# AM625SIP_FatBoi.net
KiCad netlist of a schematic drawn in Altium Designer
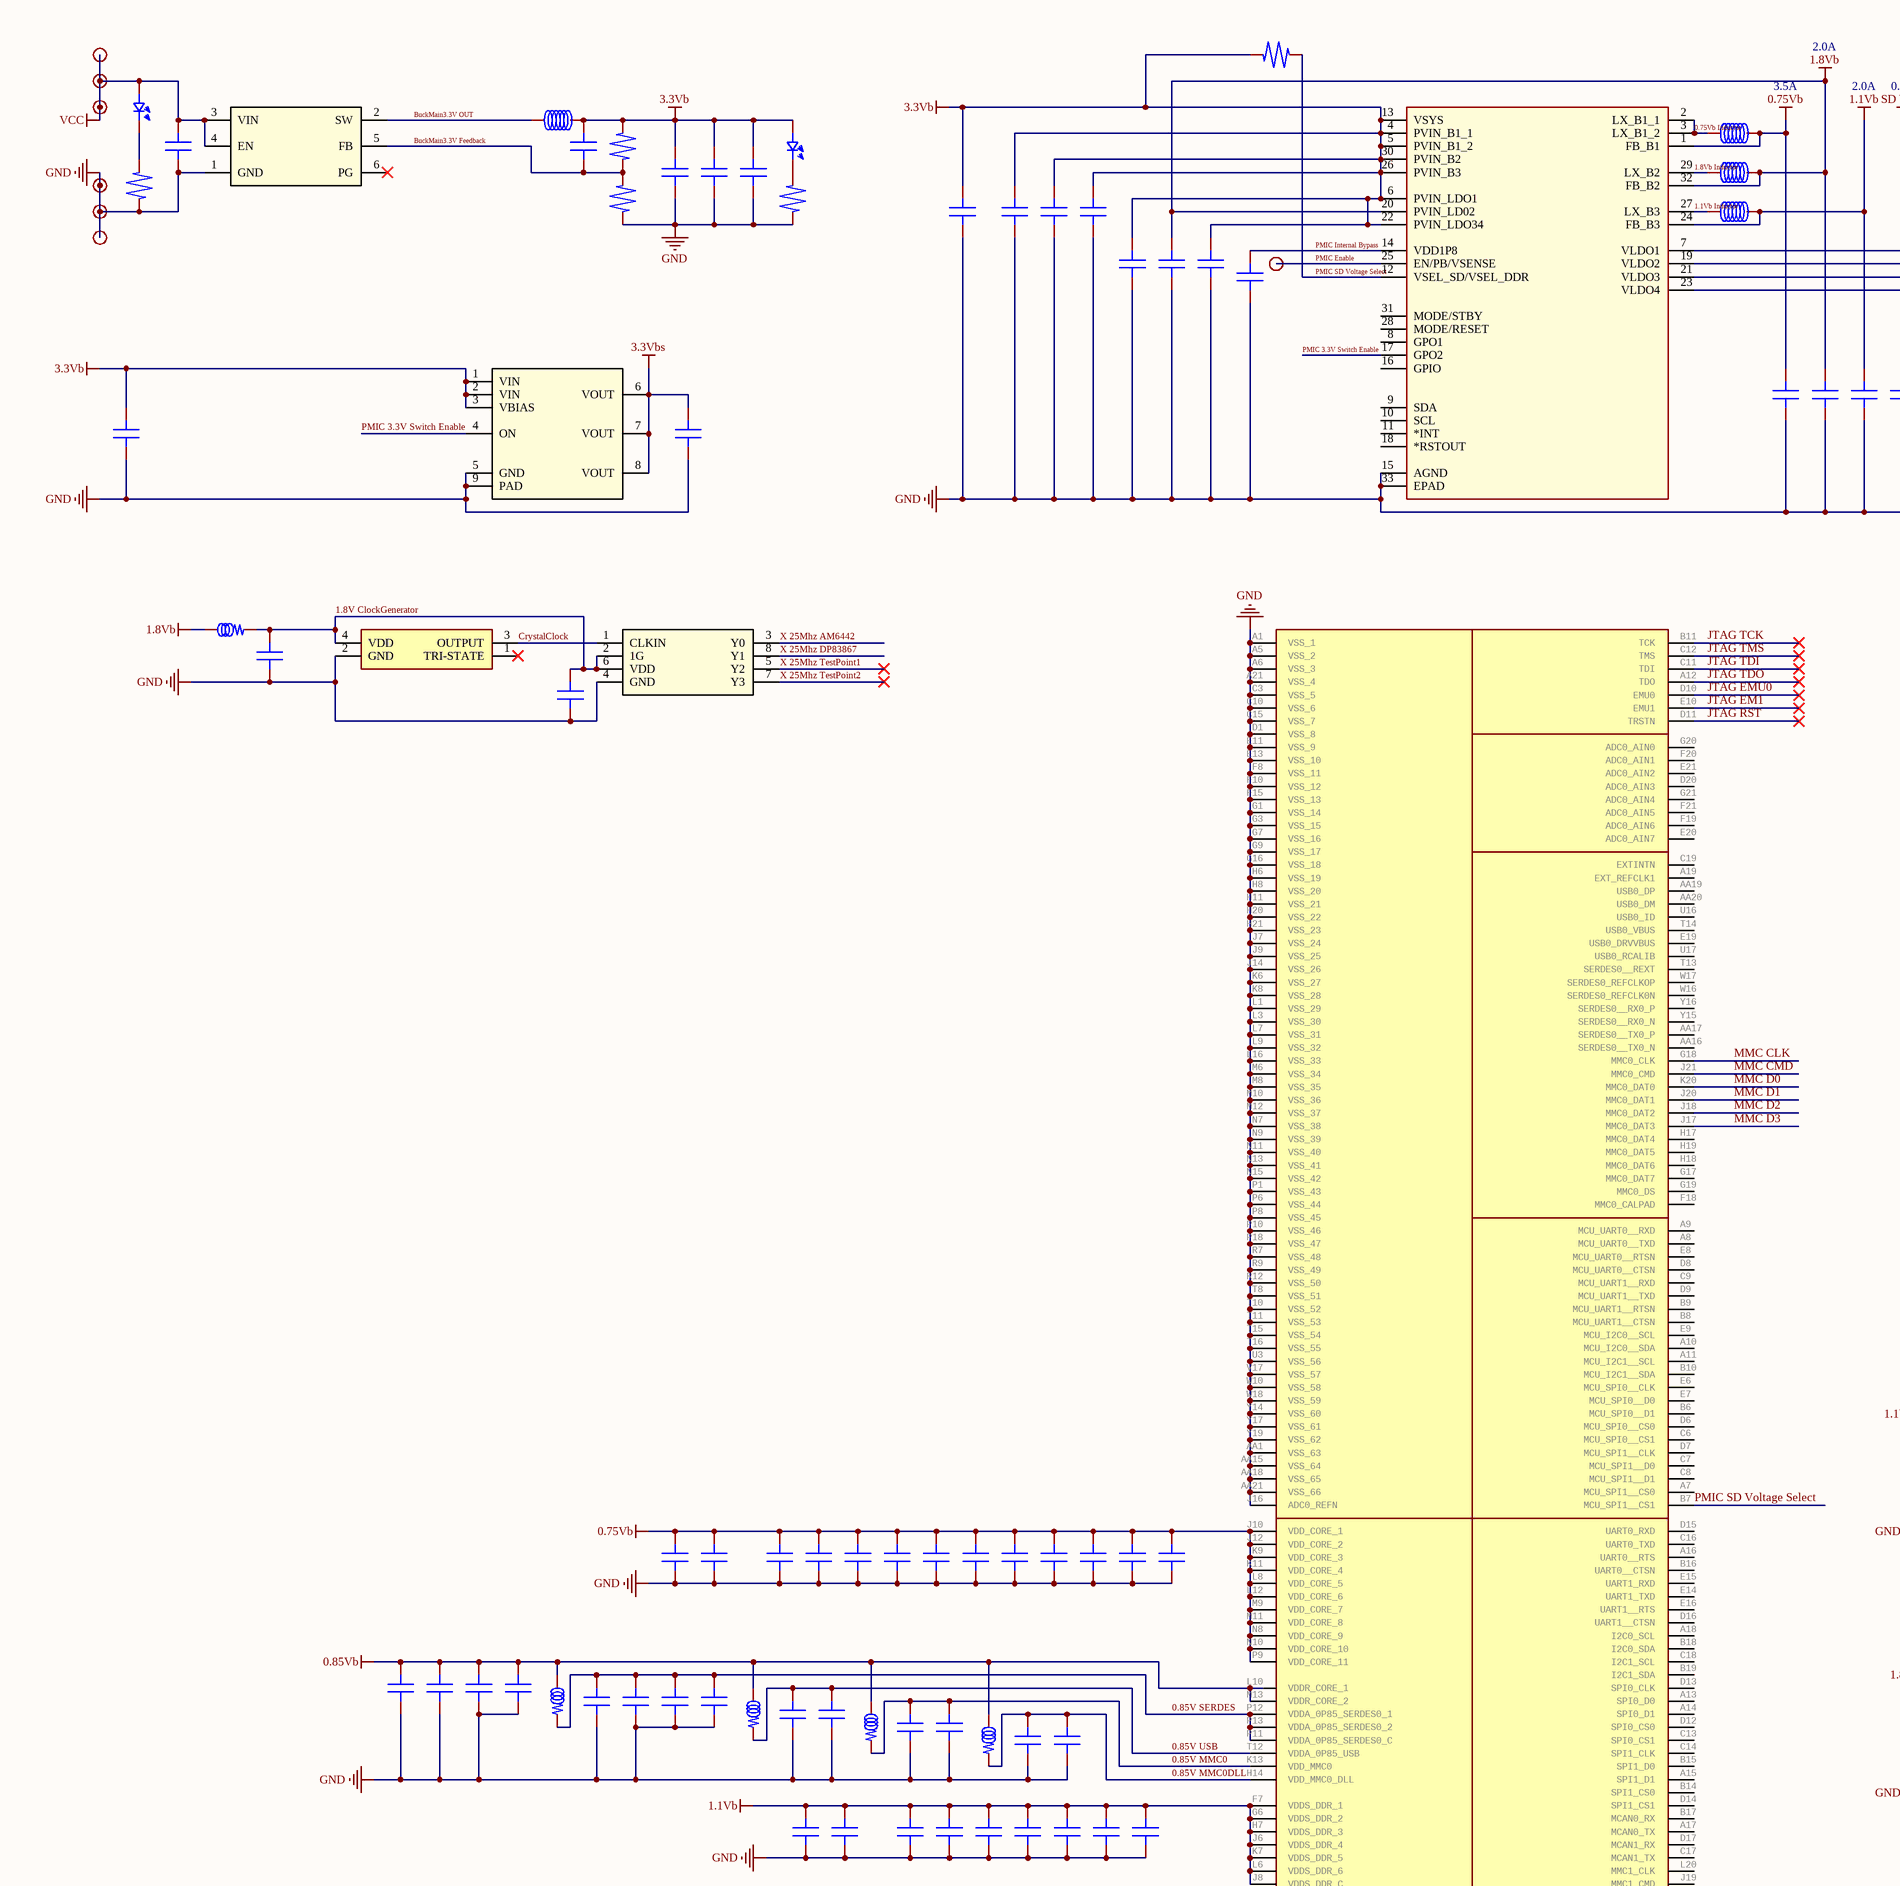
[diagram p0: AM625SIP FatBoi.SchDoc, top left]
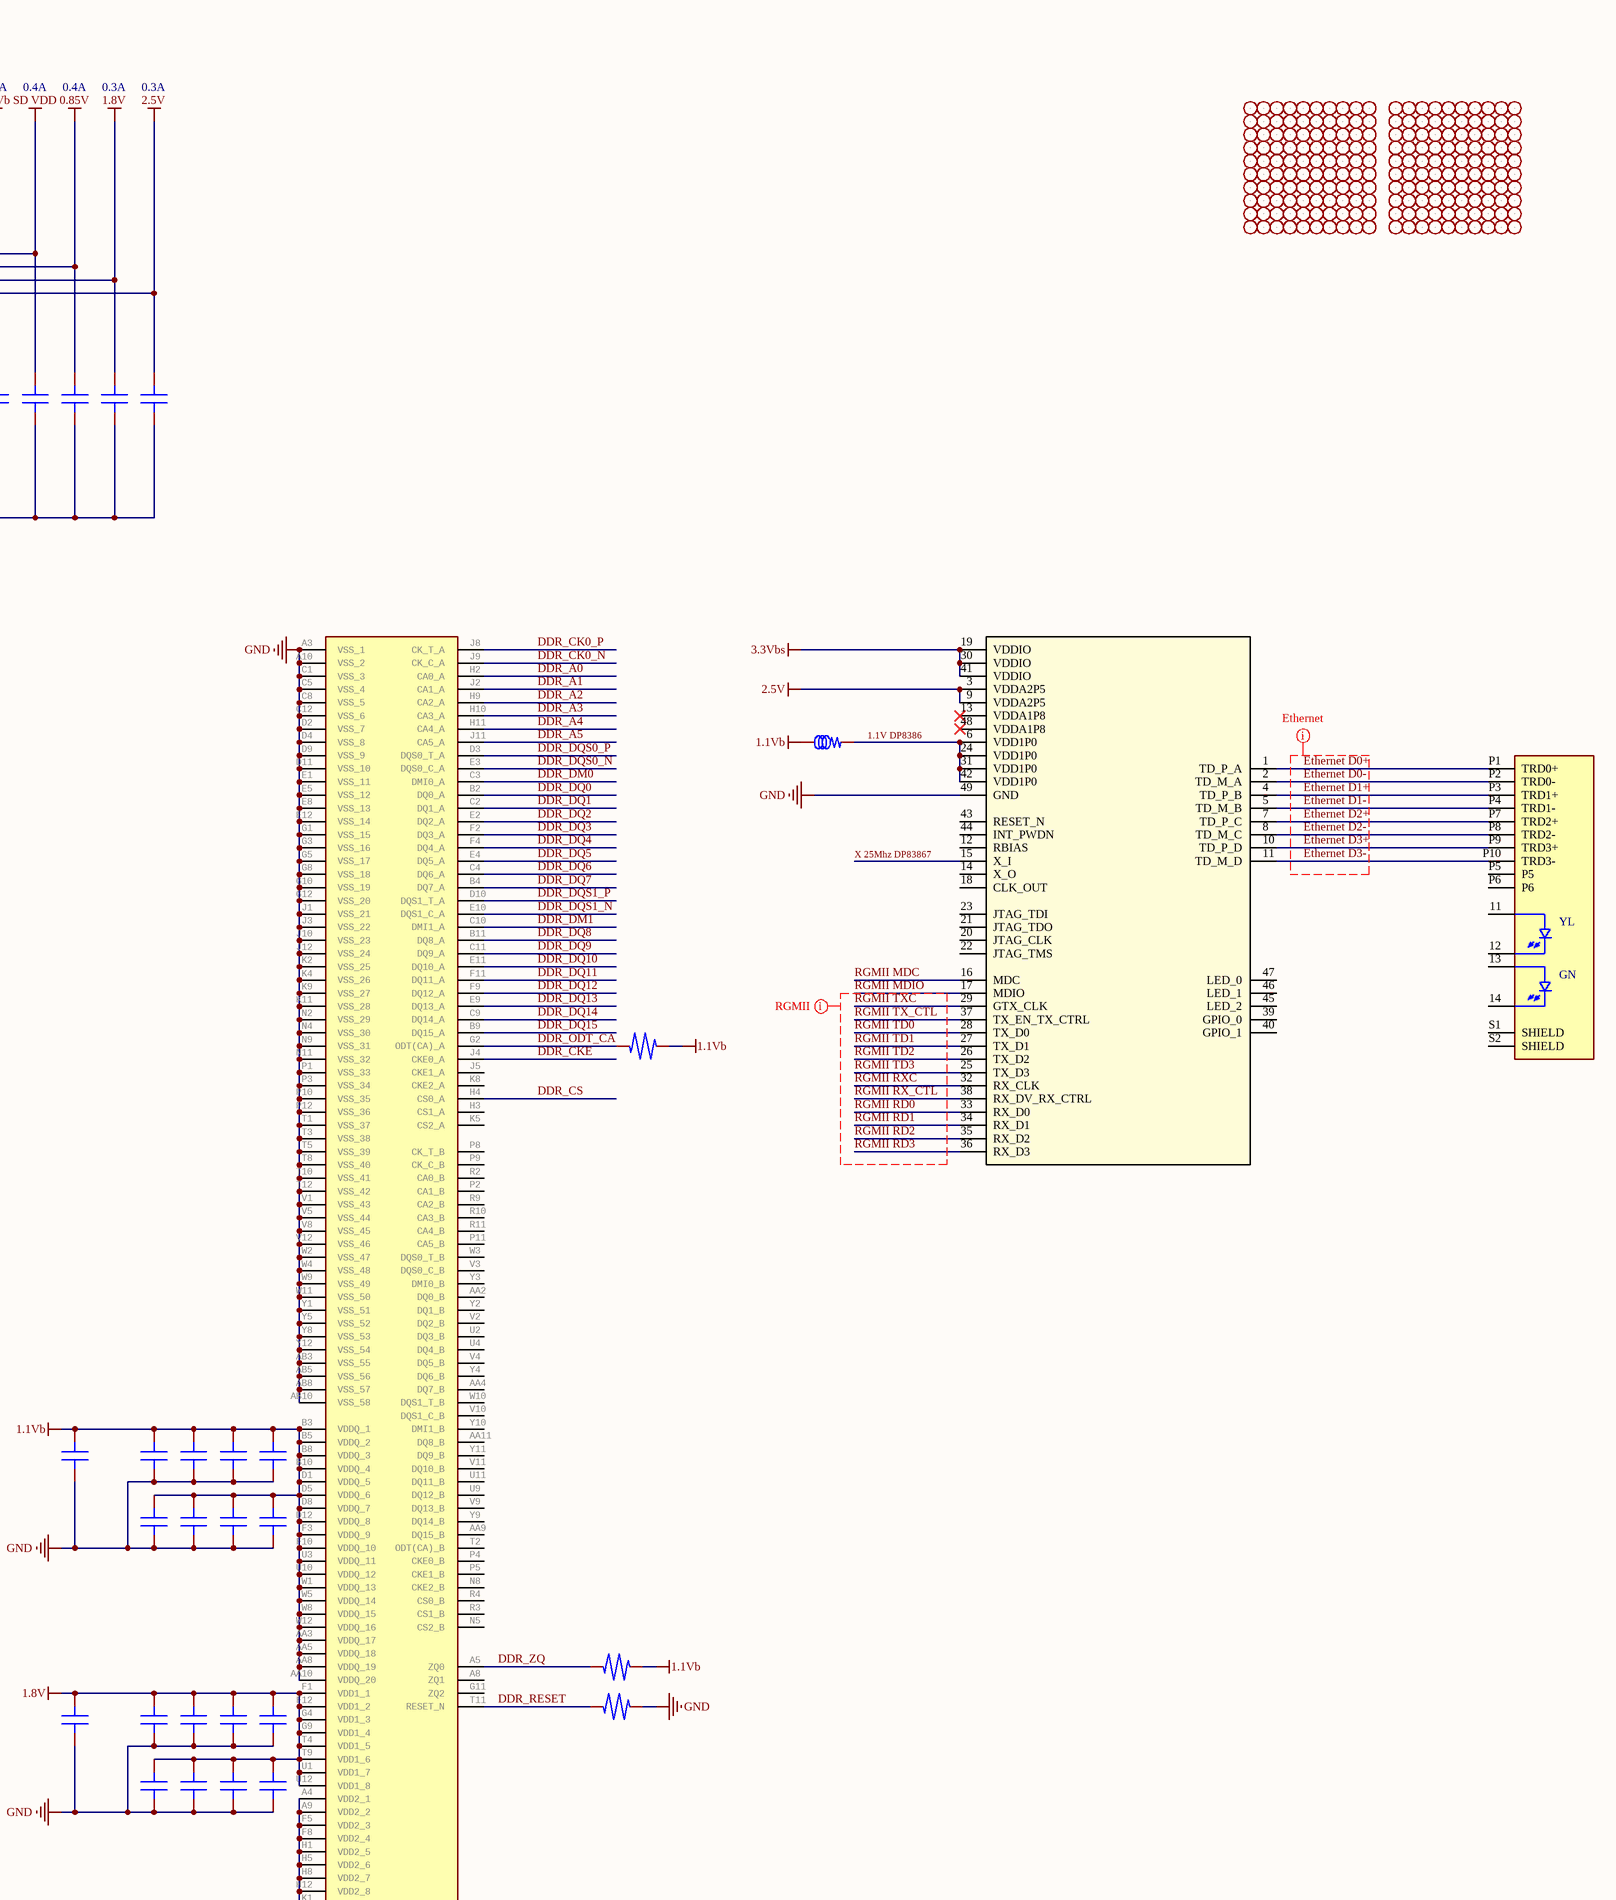
[diagram p1: AM625SIP FatBoi.SchDoc, top middle]
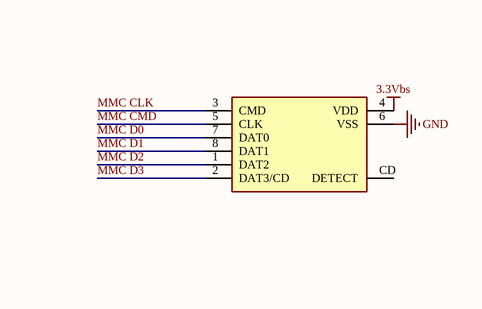
[diagram p2: AM625SIP FatBoi.SchDoc, top right]
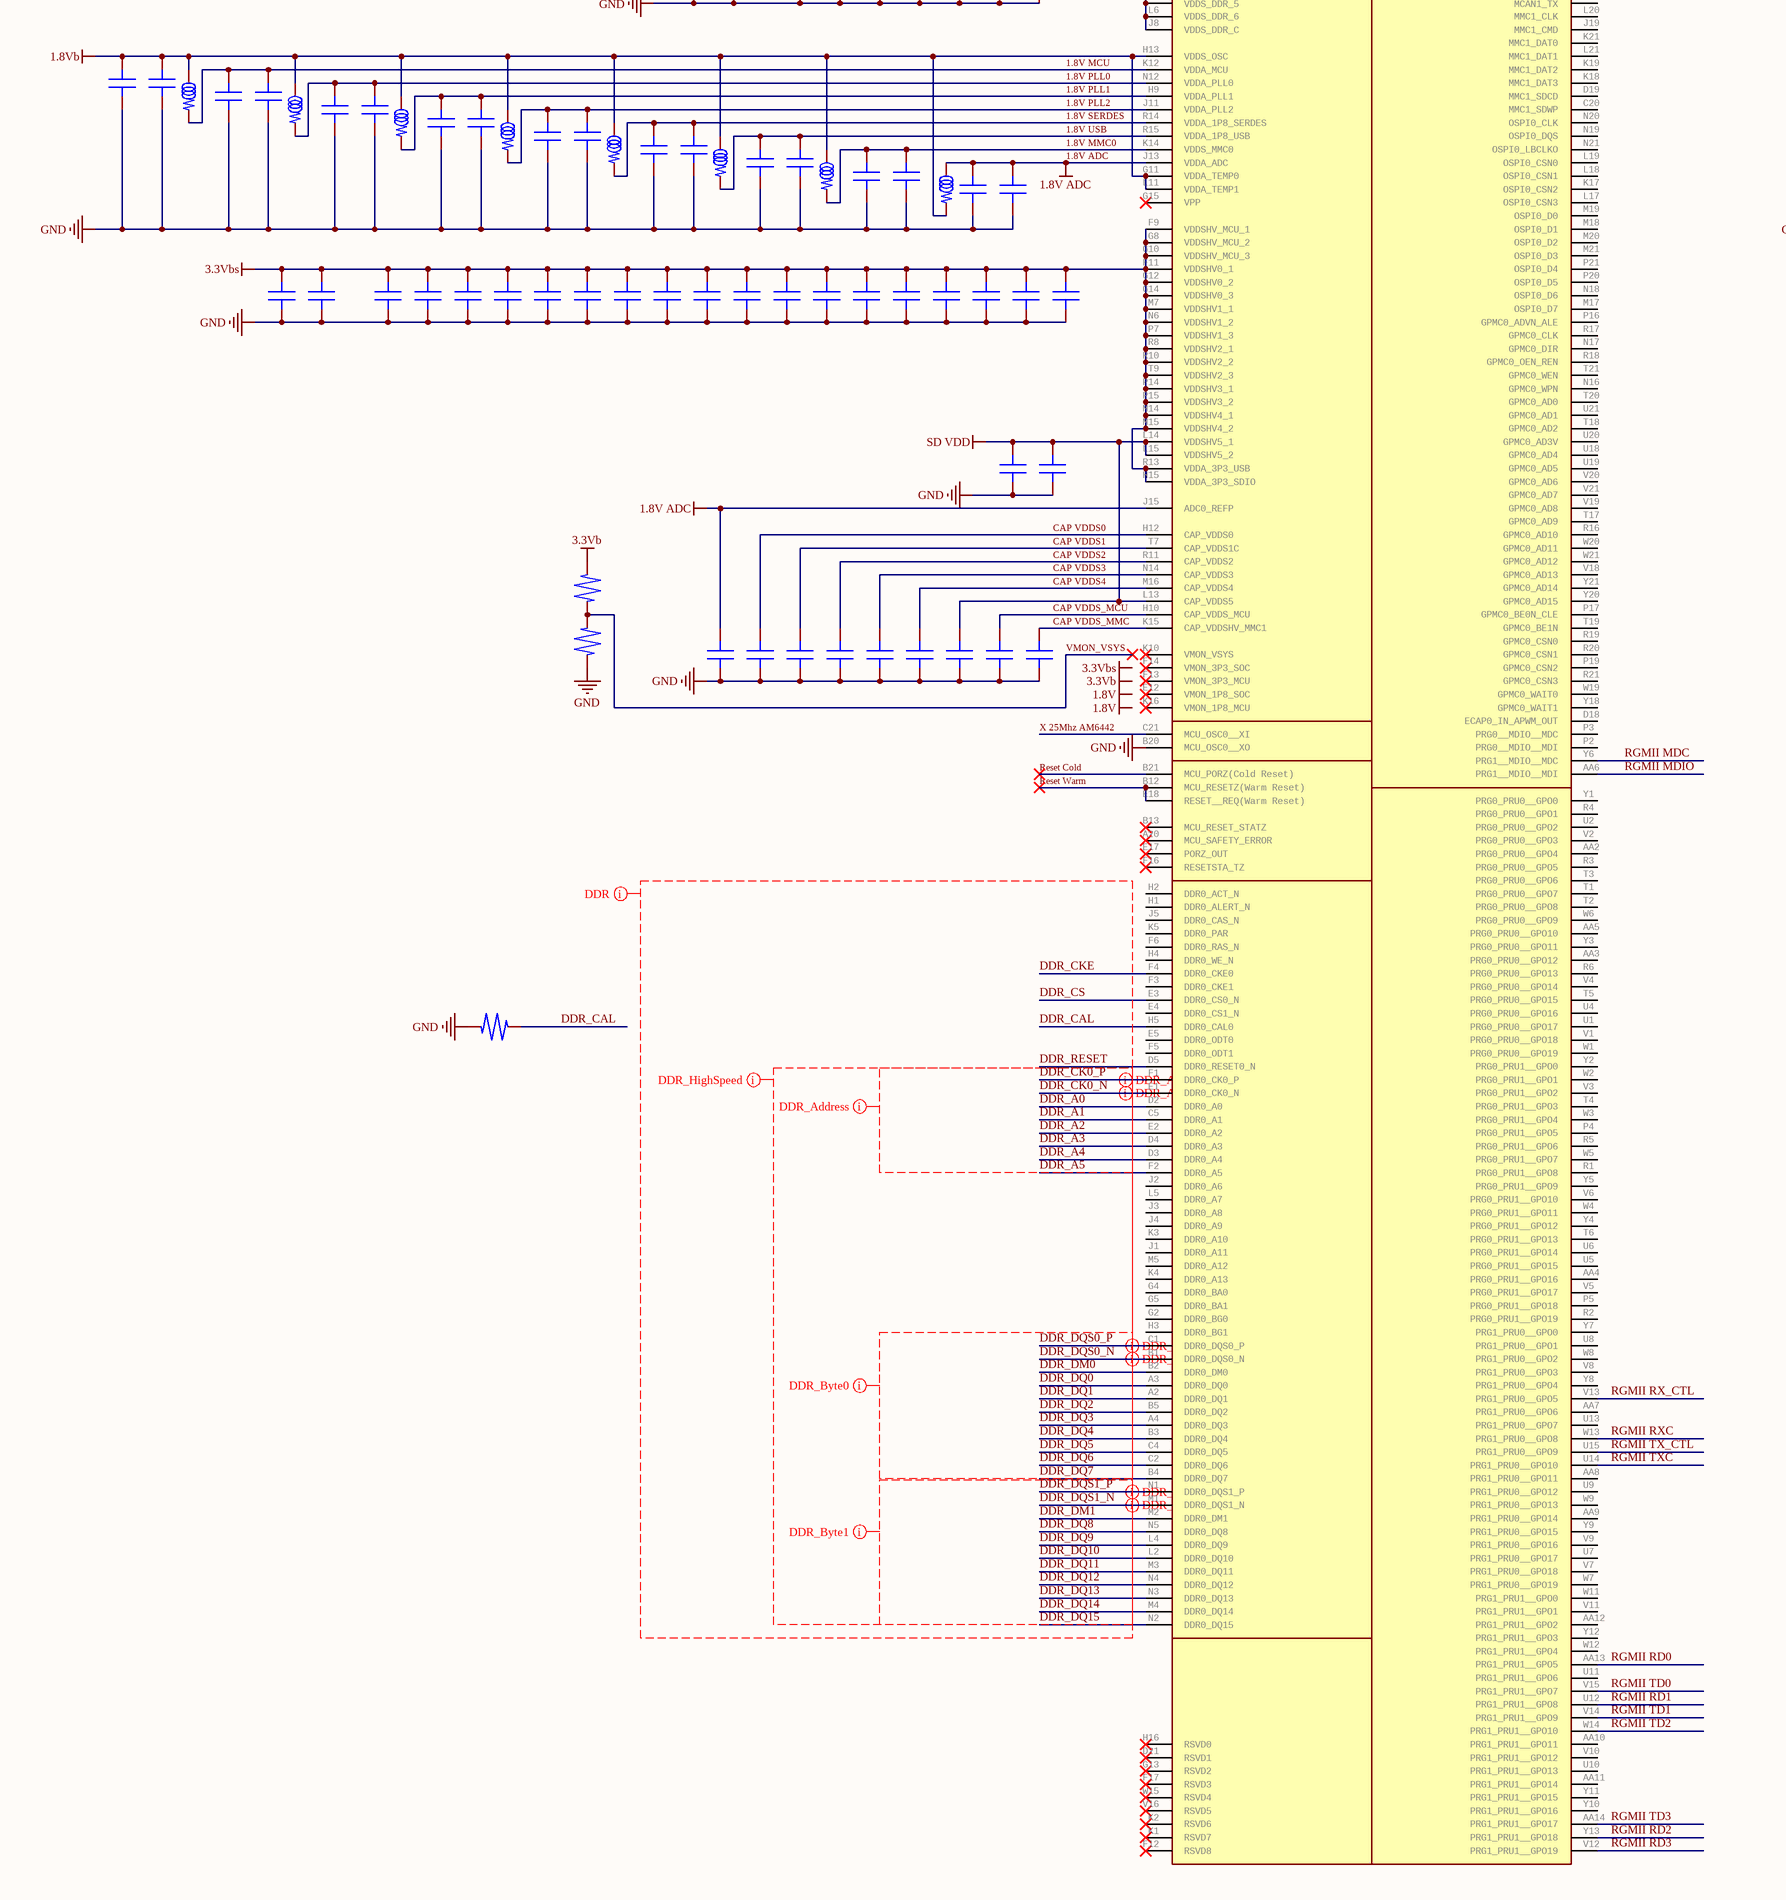
[diagram p3: AM625SIP FatBoi.SchDoc, bottom left]
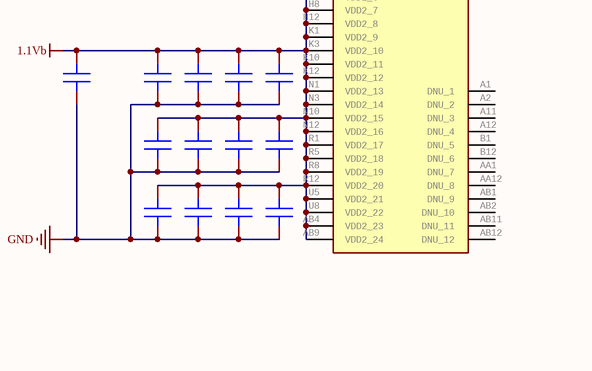
[diagram p4: AM625SIP FatBoi.SchDoc, bottom middle]

(export (version "E")
  (design (tool "Eeschema 10.0.6"))
  (components
    (comp (ref "AM6442")
      (value "ARM Cortex-A53, ARM Cortex-M5F, ARM Cortex-R5F Microprocessor IC Sitara 7 Core, 64-Bit 1GHz 441-FCBGA (17.2x17.2)   Source:  Datasheet")
      (footprint "AM6442")
      (fields
        (field (name "MANUFACTURER_PART_NUMBER") "AM6442BSDGHAALV")
        (field (name "LIBRARYNAME") "TOTUDU")
      )
      (libsource (lib "TOTUDU") (part "AM6442"))
    )
    (comp (ref "BergStrip 1")
      (value "BergStrip")
      (footprint "BergStrip 2.54mm")
      (libsource (lib "TOTUDU") (part "BergStrip"))
    )
    (comp (ref "BergStrip 2")
      (value "BergStrip")
      (footprint "BergStrip 2.54mm")
      (libsource (lib "TOTUDU") (part "BergStrip"))
    )
    (comp (ref "BergStrip 3")
      (value "BergStrip")
      (footprint "BergStrip 2.54mm")
      (libsource (lib "TOTUDU") (part "BergStrip"))
    )
    (comp (ref "BergStrip 4")
      (value "BergStrip")
      (footprint "BergStrip 2.54mm")
      (libsource (lib "TOTUDU") (part "BergStrip"))
    )
    (comp (ref "BergStrip 5")
      (value "BergStrip")
      (footprint "BergStrip 2.54mm")
      (libsource (lib "TOTUDU") (part "BergStrip"))
    )
    (comp (ref "BergStrip 5V_1")
      (value "BergStrip")
      (footprint "BergStrip 2.54mm")
      (libsource (lib "TOTUDU") (part "BergStrip"))
    )
    (comp (ref "BergStrip 5V_2")
      (value "BergStrip")
      (footprint "BergStrip 2.54mm")
      (libsource (lib "TOTUDU") (part "BergStrip"))
    )
    (comp (ref "BergStrip 5V_3")
      (value "BergStrip")
      (footprint "BergStrip 2.54mm")
      (libsource (lib "TOTUDU") (part "BergStrip"))
    )
    (comp (ref "BergStrip 6")
      (value "BergStrip")
      (footprint "BergStrip 2.54mm")
      (libsource (lib "TOTUDU") (part "BergStrip"))
    )
    (comp (ref "BergStrip 7")
      (value "BergStrip")
      (footprint "BergStrip 2.54mm")
      (libsource (lib "TOTUDU") (part "BergStrip"))
    )
    (comp (ref "BergStrip 8")
      (value "BergStrip")
      (footprint "BergStrip 2.54mm")
      (libsource (lib "TOTUDU") (part "BergStrip"))
    )
    (comp (ref "BergStrip 9")
      (value "BergStrip")
      (footprint "BergStrip 2.54mm")
      (libsource (lib "TOTUDU") (part "BergStrip"))
    )
    (comp (ref "BergStrip 10")
      (value "BergStrip")
      (footprint "BergStrip 2.54mm")
      (libsource (lib "TOTUDU") (part "BergStrip"))
    )
    (comp (ref "BergStrip 11")
      (value "BergStrip")
      (footprint "BergStrip 2.54mm")
      (libsource (lib "TOTUDU") (part "BergStrip"))
    )
    (comp (ref "BergStrip 12")
      (value "BergStrip")
      (footprint "BergStrip 2.54mm")
      (libsource (lib "TOTUDU") (part "BergStrip"))
    )
    (comp (ref "BergStrip 13")
      (value "BergStrip")
      (footprint "BergStrip 2.54mm")
      (libsource (lib "TOTUDU") (part "BergStrip"))
    )
    (comp (ref "BergStrip 14")
      (value "BergStrip")
      (footprint "BergStrip 2.54mm")
      (libsource (lib "TOTUDU") (part "BergStrip"))
    )
    (comp (ref "BergStrip 15")
      (value "BergStrip")
      (footprint "BergStrip 2.54mm")
      (libsource (lib "TOTUDU") (part "BergStrip"))
    )
    (comp (ref "BergStrip 16")
      (value "BergStrip")
      (footprint "BergStrip 2.54mm")
      (libsource (lib "TOTUDU") (part "BergStrip"))
    )
    (comp (ref "BergStrip 17")
      (value "BergStrip")
      (footprint "BergStrip 2.54mm")
      (libsource (lib "TOTUDU") (part "BergStrip"))
    )
    (comp (ref "BergStrip 18")
      (value "BergStrip")
      (footprint "BergStrip 2.54mm")
      (libsource (lib "TOTUDU") (part "BergStrip"))
    )
    (comp (ref "BergStrip 19")
      (value "BergStrip")
      (footprint "BergStrip 2.54mm")
      (libsource (lib "TOTUDU") (part "BergStrip"))
    )
    (comp (ref "BergStrip 20")
      (value "BergStrip")
      (footprint "BergStrip 2.54mm")
      (libsource (lib "TOTUDU") (part "BergStrip"))
    )
    (comp (ref "BergStrip 21")
      (value "BergStrip")
      (footprint "BergStrip 2.54mm")
      (libsource (lib "TOTUDU") (part "BergStrip"))
    )
    (comp (ref "BergStrip 22")
      (value "BergStrip")
      (footprint "BergStrip 2.54mm")
      (libsource (lib "TOTUDU") (part "BergStrip"))
    )
    (comp (ref "BergStrip 23")
      (value "BergStrip")
      (footprint "BergStrip 2.54mm")
      (libsource (lib "TOTUDU") (part "BergStrip"))
    )
    (comp (ref "BergStrip 24")
      (value "BergStrip")
      (footprint "BergStrip 2.54mm")
      (libsource (lib "TOTUDU") (part "BergStrip"))
    )
    (comp (ref "BergStrip 25")
      (value "BergStrip")
      (footprint "BergStrip 2.54mm")
      (libsource (lib "TOTUDU") (part "BergStrip"))
    )
    (comp (ref "BergStrip 26")
      (value "BergStrip")
      (footprint "BergStrip 2.54mm")
      (libsource (lib "TOTUDU") (part "BergStrip"))
    )
    (comp (ref "BergStrip 27")
      (value "BergStrip")
      (footprint "BergStrip 2.54mm")
      (libsource (lib "TOTUDU") (part "BergStrip"))
    )
    (comp (ref "BergStrip 28")
      (value "BergStrip")
      (footprint "BergStrip 2.54mm")
      (libsource (lib "TOTUDU") (part "BergStrip"))
    )
    (comp (ref "BergStrip 29")
      (value "BergStrip")
      (footprint "BergStrip 2.54mm")
      (libsource (lib "TOTUDU") (part "BergStrip"))
    )
    (comp (ref "BergStrip 30")
      (value "BergStrip")
      (footprint "BergStrip 2.54mm")
      (libsource (lib "TOTUDU") (part "BergStrip"))
    )
    (comp (ref "BergStrip 31")
      (value "BergStrip")
      (footprint "BergStrip 2.54mm")
      (libsource (lib "TOTUDU") (part "BergStrip"))
    )
    (comp (ref "BergStrip 32")
      (value "BergStrip")
      (footprint "BergStrip 2.54mm")
      (libsource (lib "TOTUDU") (part "BergStrip"))
    )
    (comp (ref "BergStrip 33")
      (value "BergStrip")
      (footprint "BergStrip 2.54mm")
      (libsource (lib "TOTUDU") (part "BergStrip"))
    )
    (comp (ref "BergStrip 34")
      (value "BergStrip")
      (footprint "BergStrip 2.54mm")
      (libsource (lib "TOTUDU") (part "BergStrip"))
    )
    (comp (ref "BergStrip 35")
      (value "BergStrip")
      (footprint "BergStrip 2.54mm")
      (libsource (lib "TOTUDU") (part "BergStrip"))
    )
    (comp (ref "BergStrip 36")
      (value "BergStrip")
      (footprint "BergStrip 2.54mm")
      (libsource (lib "TOTUDU") (part "BergStrip"))
    )
    (comp (ref "BergStrip 37")
      (value "BergStrip")
      (footprint "BergStrip 2.54mm")
      (libsource (lib "TOTUDU") (part "BergStrip"))
    )
    (comp (ref "BergStrip 38")
      (value "BergStrip")
      (footprint "BergStrip 2.54mm")
      (libsource (lib "TOTUDU") (part "BergStrip"))
    )
    (comp (ref "BergStrip 39")
      (value "BergStrip")
      (footprint "BergStrip 2.54mm")
      (libsource (lib "TOTUDU") (part "BergStrip"))
    )
    (comp (ref "BergStrip 40")
      (value "BergStrip")
      (footprint "BergStrip 2.54mm")
      (libsource (lib "TOTUDU") (part "BergStrip"))
    )
    (comp (ref "BergStrip 41")
      (value "BergStrip")
      (footprint "BergStrip 2.54mm")
      (libsource (lib "TOTUDU") (part "BergStrip"))
    )
    (comp (ref "BergStrip 42")
      (value "BergStrip")
      (footprint "BergStrip 2.54mm")
      (libsource (lib "TOTUDU") (part "BergStrip"))
    )
    (comp (ref "BergStrip 43")
      (value "BergStrip")
      (footprint "BergStrip 2.54mm")
      (libsource (lib "TOTUDU") (part "BergStrip"))
    )
    (comp (ref "BergStrip 44")
      (value "BergStrip")
      (footprint "BergStrip 2.54mm")
      (libsource (lib "TOTUDU") (part "BergStrip"))
    )
    (comp (ref "BergStrip 45")
      (value "BergStrip")
      (footprint "BergStrip 2.54mm")
      (libsource (lib "TOTUDU") (part "BergStrip"))
    )
    (comp (ref "BergStrip 46")
      (value "BergStrip")
      (footprint "BergStrip 2.54mm")
      (libsource (lib "TOTUDU") (part "BergStrip"))
    )
    (comp (ref "BergStrip 47")
      (value "BergStrip")
      (footprint "BergStrip 2.54mm")
      (libsource (lib "TOTUDU") (part "BergStrip"))
    )
    (comp (ref "BergStrip 48")
      (value "BergStrip")
      (footprint "BergStrip 2.54mm")
      (libsource (lib "TOTUDU") (part "BergStrip"))
    )
    (comp (ref "BergStrip 49")
      (value "BergStrip")
      (footprint "BergStrip 2.54mm")
      (libsource (lib "TOTUDU") (part "BergStrip"))
    )
    (comp (ref "BergStrip 50")
      (value "BergStrip")
      (footprint "BergStrip 2.54mm")
      (libsource (lib "TOTUDU") (part "BergStrip"))
    )
    (comp (ref "BergStrip 51")
      (value "BergStrip")
      (footprint "BergStrip 2.54mm")
      (libsource (lib "TOTUDU") (part "BergStrip"))
    )
    (comp (ref "BergStrip 52")
      (value "BergStrip")
      (footprint "BergStrip 2.54mm")
      (libsource (lib "TOTUDU") (part "BergStrip"))
    )
    (comp (ref "BergStrip 53")
      (value "BergStrip")
      (footprint "BergStrip 2.54mm")
      (libsource (lib "TOTUDU") (part "BergStrip"))
    )
    (comp (ref "BergStrip 54")
      (value "BergStrip")
      (footprint "BergStrip 2.54mm")
      (libsource (lib "TOTUDU") (part "BergStrip"))
    )
    (comp (ref "BergStrip 55")
      (value "BergStrip")
      (footprint "BergStrip 2.54mm")
      (libsource (lib "TOTUDU") (part "BergStrip"))
    )
    (comp (ref "BergStrip 56")
      (value "BergStrip")
      (footprint "BergStrip 2.54mm")
      (libsource (lib "TOTUDU") (part "BergStrip"))
    )
    (comp (ref "BergStrip 57")
      (value "BergStrip")
      (footprint "BergStrip 2.54mm")
      (libsource (lib "TOTUDU") (part "BergStrip"))
    )
    (comp (ref "BergStrip 58")
      (value "BergStrip")
      (footprint "BergStrip 2.54mm")
      (libsource (lib "TOTUDU") (part "BergStrip"))
    )
    (comp (ref "BergStrip 59")
      (value "BergStrip")
      (footprint "BergStrip 2.54mm")
      (libsource (lib "TOTUDU") (part "BergStrip"))
    )
    (comp (ref "BergStrip 60")
      (value "BergStrip")
      (footprint "BergStrip 2.54mm")
      (libsource (lib "TOTUDU") (part "BergStrip"))
    )
    (comp (ref "BergStrip 61")
      (value "BergStrip")
      (footprint "BergStrip 2.54mm")
      (libsource (lib "TOTUDU") (part "BergStrip"))
    )
    (comp (ref "BergStrip 62")
      (value "BergStrip")
      (footprint "BergStrip 2.54mm")
      (libsource (lib "TOTUDU") (part "BergStrip"))
    )
    (comp (ref "BergStrip 63")
      (value "BergStrip")
      (footprint "BergStrip 2.54mm")
      (libsource (lib "TOTUDU") (part "BergStrip"))
    )
    (comp (ref "BergStrip 64")
      (value "BergStrip")
      (footprint "BergStrip 2.54mm")
      (libsource (lib "TOTUDU") (part "BergStrip"))
    )
    (comp (ref "BergStrip 65")
      (value "BergStrip")
      (footprint "BergStrip 2.54mm")
      (libsource (lib "TOTUDU") (part "BergStrip"))
    )
    (comp (ref "BergStrip 66")
      (value "BergStrip")
      (footprint "BergStrip 2.54mm")
      (libsource (lib "TOTUDU") (part "BergStrip"))
    )
    (comp (ref "BergStrip 67")
      (value "BergStrip")
      (footprint "BergStrip 2.54mm")
      (libsource (lib "TOTUDU") (part "BergStrip"))
    )
    (comp (ref "BergStrip 68")
      (value "BergStrip")
      (footprint "BergStrip 2.54mm")
      (libsource (lib "TOTUDU") (part "BergStrip"))
    )
    (comp (ref "BergStrip 69")
      (value "BergStrip")
      (footprint "BergStrip 2.54mm")
      (libsource (lib "TOTUDU") (part "BergStrip"))
    )
    (comp (ref "BergStrip 70")
      (value "BergStrip")
      (footprint "BergStrip 2.54mm")
      (libsource (lib "TOTUDU") (part "BergStrip"))
    )
    (comp (ref "BergStrip 71")
      (value "BergStrip")
      (footprint "BergStrip 2.54mm")
      (libsource (lib "TOTUDU") (part "BergStrip"))
    )
    (comp (ref "BergStrip 72")
      (value "BergStrip")
      (footprint "BergStrip 2.54mm")
      (libsource (lib "TOTUDU") (part "BergStrip"))
    )
    (comp (ref "BergStrip 73")
      (value "BergStrip")
      (footprint "BergStrip 2.54mm")
      (libsource (lib "TOTUDU") (part "BergStrip"))
    )
    (comp (ref "BergStrip 74")
      (value "BergStrip")
      (footprint "BergStrip 2.54mm")
      (libsource (lib "TOTUDU") (part "BergStrip"))
    )
    (comp (ref "BergStrip 75")
      (value "BergStrip")
      (footprint "BergStrip 2.54mm")
      (libsource (lib "TOTUDU") (part "BergStrip"))
    )
    (comp (ref "BergStrip 76")
      (value "BergStrip")
      (footprint "BergStrip 2.54mm")
      (libsource (lib "TOTUDU") (part "BergStrip"))
    )
    (comp (ref "BergStrip 77")
      (value "BergStrip")
      (footprint "BergStrip 2.54mm")
      (libsource (lib "TOTUDU") (part "BergStrip"))
    )
    (comp (ref "BergStrip 78")
      (value "BergStrip")
      (footprint "BergStrip 2.54mm")
      (libsource (lib "TOTUDU") (part "BergStrip"))
    )
    (comp (ref "BergStrip 79")
      (value "BergStrip")
      (footprint "BergStrip 2.54mm")
      (libsource (lib "TOTUDU") (part "BergStrip"))
    )
    (comp (ref "BergStrip 80")
      (value "BergStrip")
      (footprint "BergStrip 2.54mm")
      (libsource (lib "TOTUDU") (part "BergStrip"))
    )
    (comp (ref "BergStrip 81")
      (value "BergStrip")
      (footprint "BergStrip 2.54mm")
      (libsource (lib "TOTUDU") (part "BergStrip"))
    )
    (comp (ref "BergStrip 82")
      (value "BergStrip")
      (footprint "BergStrip 2.54mm")
      (libsource (lib "TOTUDU") (part "BergStrip"))
    )
    (comp (ref "BergStrip 83")
      (value "BergStrip")
      (footprint "BergStrip 2.54mm")
      (libsource (lib "TOTUDU") (part "BergStrip"))
    )
    (comp (ref "BergStrip 84")
      (value "BergStrip")
      (footprint "BergStrip 2.54mm")
      (libsource (lib "TOTUDU") (part "BergStrip"))
    )
    (comp (ref "BergStrip 85")
      (value "BergStrip")
      (footprint "BergStrip 2.54mm")
      (libsource (lib "TOTUDU") (part "BergStrip"))
    )
    (comp (ref "BergStrip 86")
      (value "BergStrip")
      (footprint "BergStrip 2.54mm")
      (libsource (lib "TOTUDU") (part "BergStrip"))
    )
    (comp (ref "BergStrip 87")
      (value "BergStrip")
      (footprint "BergStrip 2.54mm")
      (libsource (lib "TOTUDU") (part "BergStrip"))
    )
    (comp (ref "BergStrip 88")
      (value "BergStrip")
      (footprint "BergStrip 2.54mm")
      (libsource (lib "TOTUDU") (part "BergStrip"))
    )
    (comp (ref "BergStrip 89")
      (value "BergStrip")
      (footprint "BergStrip 2.54mm")
      (libsource (lib "TOTUDU") (part "BergStrip"))
    )
    (comp (ref "BergStrip 90")
      (value "BergStrip")
      (footprint "BergStrip 2.54mm")
      (libsource (lib "TOTUDU") (part "BergStrip"))
    )
    (comp (ref "BergStrip 91")
      (value "BergStrip")
      (footprint "BergStrip 2.54mm")
      (libsource (lib "TOTUDU") (part "BergStrip"))
    )
    (comp (ref "BergStrip 92")
      (value "BergStrip")
      (footprint "BergStrip 2.54mm")
      (libsource (lib "TOTUDU") (part "BergStrip"))
    )
    (comp (ref "BergStrip 93")
      (value "BergStrip")
      (footprint "BergStrip 2.54mm")
      (libsource (lib "TOTUDU") (part "BergStrip"))
    )
    (comp (ref "BergStrip 94")
      (value "BergStrip")
      (footprint "BergStrip 2.54mm")
      (libsource (lib "TOTUDU") (part "BergStrip"))
    )
    (comp (ref "BergStrip 95")
      (value "BergStrip")
      (footprint "BergStrip 2.54mm")
      (libsource (lib "TOTUDU") (part "BergStrip"))
    )
    (comp (ref "BergStrip 96")
      (value "BergStrip")
      (footprint "BergStrip 2.54mm")
      (libsource (lib "TOTUDU") (part "BergStrip"))
    )
    (comp (ref "BergStrip 97")
      (value "BergStrip")
      (footprint "BergStrip 2.54mm")
      (libsource (lib "TOTUDU") (part "BergStrip"))
    )
    (comp (ref "BergStrip 98")
      (value "BergStrip")
      (footprint "BergStrip 2.54mm")
      (libsource (lib "TOTUDU") (part "BergStrip"))
    )
    (comp (ref "BergStrip 99")
      (value "BergStrip")
      (footprint "BergStrip 2.54mm")
      (libsource (lib "TOTUDU") (part "BergStrip"))
    )
    (comp (ref "BergStrip 100")
      (value "BergStrip")
      (footprint "BergStrip 2.54mm")
      (libsource (lib "TOTUDU") (part "BergStrip"))
    )
    (comp (ref "BergStrip 101")
      (value "BergStrip")
      (footprint "BergStrip 2.54mm")
      (libsource (lib "TOTUDU") (part "BergStrip"))
    )
    (comp (ref "BergStrip 102")
      (value "BergStrip")
      (footprint "BergStrip 2.54mm")
      (libsource (lib "TOTUDU") (part "BergStrip"))
    )
    (comp (ref "BergStrip 103")
      (value "BergStrip")
      (footprint "BergStrip 2.54mm")
      (libsource (lib "TOTUDU") (part "BergStrip"))
    )
    (comp (ref "BergStrip 104")
      (value "BergStrip")
      (footprint "BergStrip 2.54mm")
      (libsource (lib "TOTUDU") (part "BergStrip"))
    )
    (comp (ref "BergStrip 105")
      (value "BergStrip")
      (footprint "BergStrip 2.54mm")
      (libsource (lib "TOTUDU") (part "BergStrip"))
    )
    (comp (ref "BergStrip 106")
      (value "BergStrip")
      (footprint "BergStrip 2.54mm")
      (libsource (lib "TOTUDU") (part "BergStrip"))
    )
    (comp (ref "BergStrip 107")
      (value "BergStrip")
      (footprint "BergStrip 2.54mm")
      (libsource (lib "TOTUDU") (part "BergStrip"))
    )
    (comp (ref "BergStrip 108")
      (value "BergStrip")
      (footprint "BergStrip 2.54mm")
      (libsource (lib "TOTUDU") (part "BergStrip"))
    )
    (comp (ref "BergStrip 109")
      (value "BergStrip")
      (footprint "BergStrip 2.54mm")
      (libsource (lib "TOTUDU") (part "BergStrip"))
    )
    (comp (ref "BergStrip 110")
      (value "BergStrip")
      (footprint "BergStrip 2.54mm")
      (libsource (lib "TOTUDU") (part "BergStrip"))
    )
    (comp (ref "BergStrip 111")
      (value "BergStrip")
      (footprint "BergStrip 2.54mm")
      (libsource (lib "TOTUDU") (part "BergStrip"))
    )
    (comp (ref "BergStrip 112")
      (value "BergStrip")
      (footprint "BergStrip 2.54mm")
      (libsource (lib "TOTUDU") (part "BergStrip"))
    )
    (comp (ref "BergStrip 113")
      (value "BergStrip")
      (footprint "BergStrip 2.54mm")
      (libsource (lib "TOTUDU") (part "BergStrip"))
    )
    (comp (ref "BergStrip 114")
      (value "BergStrip")
      (footprint "BergStrip 2.54mm")
      (libsource (lib "TOTUDU") (part "BergStrip"))
    )
    (comp (ref "BergStrip 115")
      (value "BergStrip")
      (footprint "BergStrip 2.54mm")
      (libsource (lib "TOTUDU") (part "BergStrip"))
    )
    (comp (ref "BergStrip 116")
      (value "BergStrip")
      (footprint "BergStrip 2.54mm")
      (libsource (lib "TOTUDU") (part "BergStrip"))
    )
    (comp (ref "BergStrip 117")
      (value "BergStrip")
      (footprint "BergStrip 2.54mm")
      (libsource (lib "TOTUDU") (part "BergStrip"))
    )
    (comp (ref "BergStrip 118")
      (value "BergStrip")
      (footprint "BergStrip 2.54mm")
      (libsource (lib "TOTUDU") (part "BergStrip"))
    )
    (comp (ref "BergStrip 119")
      (value "BergStrip")
      (footprint "BergStrip 2.54mm")
      (libsource (lib "TOTUDU") (part "BergStrip"))
    )
    (comp (ref "BergStrip 120")
      (value "BergStrip")
      (footprint "BergStrip 2.54mm")
      (libsource (lib "TOTUDU") (part "BergStrip"))
    )
    (comp (ref "BergStrip 121")
      (value "BergStrip")
      (footprint "BergStrip 2.54mm")
      (libsource (lib "TOTUDU") (part "BergStrip"))
    )
    (comp (ref "BergStrip 122")
      (value "BergStrip")
      (footprint "BergStrip 2.54mm")
      (libsource (lib "TOTUDU") (part "BergStrip"))
    )
    (comp (ref "BergStrip 123")
      (value "BergStrip")
      (footprint "BergStrip 2.54mm")
      (libsource (lib "TOTUDU") (part "BergStrip"))
    )
    (comp (ref "BergStrip 124")
      (value "BergStrip")
      (footprint "BergStrip 2.54mm")
      (libsource (lib "TOTUDU") (part "BergStrip"))
    )
    (comp (ref "BergStrip 125")
      (value "BergStrip")
      (footprint "BergStrip 2.54mm")
      (libsource (lib "TOTUDU") (part "BergStrip"))
    )
    (comp (ref "BergStrip 126")
      (value "BergStrip")
      (footprint "BergStrip 2.54mm")
      (libsource (lib "TOTUDU") (part "BergStrip"))
    )
    (comp (ref "BergStrip 127")
      (value "BergStrip")
      (footprint "BergStrip 2.54mm")
      (libsource (lib "TOTUDU") (part "BergStrip"))
    )
    (comp (ref "BergStrip 128")
      (value "BergStrip")
      (footprint "BergStrip 2.54mm")
      (libsource (lib "TOTUDU") (part "BergStrip"))
    )
    (comp (ref "BergStrip 129")
      (value "BergStrip")
      (footprint "BergStrip 2.54mm")
      (libsource (lib "TOTUDU") (part "BergStrip"))
    )
    (comp (ref "BergStrip 130")
      (value "BergStrip")
      (footprint "BergStrip 2.54mm")
      (libsource (lib "TOTUDU") (part "BergStrip"))
    )
    (comp (ref "BergStrip 131")
      (value "BergStrip")
      (footprint "BergStrip 2.54mm")
      (libsource (lib "TOTUDU") (part "BergStrip"))
    )
    (comp (ref "BergStrip 132")
      (value "BergStrip")
      (footprint "BergStrip 2.54mm")
      (libsource (lib "TOTUDU") (part "BergStrip"))
    )
    (comp (ref "BergStrip 133")
      (value "BergStrip")
      (footprint "BergStrip 2.54mm")
      (libsource (lib "TOTUDU") (part "BergStrip"))
    )
    (comp (ref "BergStrip 134")
      (value "BergStrip")
      (footprint "BergStrip 2.54mm")
      (libsource (lib "TOTUDU") (part "BergStrip"))
    )
    (comp (ref "BergStrip 135")
      (value "BergStrip")
      (footprint "BergStrip 2.54mm")
      (libsource (lib "TOTUDU") (part "BergStrip"))
    )
    (comp (ref "BergStrip 136")
      (value "BergStrip")
      (footprint "BergStrip 2.54mm")
      (libsource (lib "TOTUDU") (part "BergStrip"))
    )
    (comp (ref "BergStrip 137")
      (value "BergStrip")
      (footprint "BergStrip 2.54mm")
      (libsource (lib "TOTUDU") (part "BergStrip"))
    )
    (comp (ref "BergStrip 138")
      (value "BergStrip")
      (footprint "BergStrip 2.54mm")
      (libsource (lib "TOTUDU") (part "BergStrip"))
    )
    (comp (ref "BergStrip 139")
      (value "BergStrip")
      (footprint "BergStrip 2.54mm")
      (libsource (lib "TOTUDU") (part "BergStrip"))
    )
    (comp (ref "BergStrip 140")
      (value "BergStrip")
      (footprint "BergStrip 2.54mm")
      (libsource (lib "TOTUDU") (part "BergStrip"))
    )
    (comp (ref "BergStrip 141")
      (value "BergStrip")
      (footprint "BergStrip 2.54mm")
      (libsource (lib "TOTUDU") (part "BergStrip"))
    )
    (comp (ref "BergStrip 142")
      (value "BergStrip")
      (footprint "BergStrip 2.54mm")
      (libsource (lib "TOTUDU") (part "BergStrip"))
    )
    (comp (ref "BergStrip 143")
      (value "BergStrip")
      (footprint "BergStrip 2.54mm")
      (libsource (lib "TOTUDU") (part "BergStrip"))
    )
    (comp (ref "BergStrip 144")
      (value "BergStrip")
      (footprint "BergStrip 2.54mm")
      (libsource (lib "TOTUDU") (part "BergStrip"))
    )
    (comp (ref "BergStrip 145")
      (value "BergStrip")
      (footprint "BergStrip 2.54mm")
      (libsource (lib "TOTUDU") (part "BergStrip"))
    )
    (comp (ref "BergStrip 146")
      (value "BergStrip")
      (footprint "BergStrip 2.54mm")
      (libsource (lib "TOTUDU") (part "BergStrip"))
    )
    (comp (ref "BergStrip 147")
      (value "BergStrip")
      (footprint "BergStrip 2.54mm")
      (libsource (lib "TOTUDU") (part "BergStrip"))
    )
    (comp (ref "BergStrip 148")
      (value "BergStrip")
      (footprint "BergStrip 2.54mm")
      (libsource (lib "TOTUDU") (part "BergStrip"))
    )
    (comp (ref "BergStrip 149")
      (value "BergStrip")
      (footprint "BergStrip 2.54mm")
      (libsource (lib "TOTUDU") (part "BergStrip"))
    )
    (comp (ref "BergStrip 150")
      (value "BergStrip")
      (footprint "BergStrip 2.54mm")
      (libsource (lib "TOTUDU") (part "BergStrip"))
    )
    (comp (ref "BergStrip 151")
      (value "BergStrip")
      (footprint "BergStrip 2.54mm")
      (libsource (lib "TOTUDU") (part "BergStrip"))
    )
    (comp (ref "BergStrip 152")
      (value "BergStrip")
      (footprint "BergStrip 2.54mm")
      (libsource (lib "TOTUDU") (part "BergStrip"))
    )
    (comp (ref "BergStrip 153")
      (value "BergStrip")
      (footprint "BergStrip 2.54mm")
      (libsource (lib "TOTUDU") (part "BergStrip"))
    )
    (comp (ref "BergStrip 154")
      (value "BergStrip")
      (footprint "BergStrip 2.54mm")
      (libsource (lib "TOTUDU") (part "BergStrip"))
    )
    (comp (ref "BergStrip 155")
      (value "BergStrip")
      (footprint "BergStrip 2.54mm")
      (libsource (lib "TOTUDU") (part "BergStrip"))
    )
    (comp (ref "BergStrip 156")
      (value "BergStrip")
      (footprint "BergStrip 2.54mm")
      (libsource (lib "TOTUDU") (part "BergStrip"))
    )
    (comp (ref "BergStrip 157")
      (value "BergStrip")
      (footprint "BergStrip 2.54mm")
      (libsource (lib "TOTUDU") (part "BergStrip"))
    )
    (comp (ref "BergStrip 158")
      (value "BergStrip")
      (footprint "BergStrip 2.54mm")
      (libsource (lib "TOTUDU") (part "BergStrip"))
    )
    (comp (ref "BergStrip 159")
      (value "BergStrip")
      (footprint "BergStrip 2.54mm")
      (libsource (lib "TOTUDU") (part "BergStrip"))
    )
    (comp (ref "BergStrip 160")
      (value "BergStrip")
      (footprint "BergStrip 2.54mm")
      (libsource (lib "TOTUDU") (part "BergStrip"))
    )
    (comp (ref "BergStrip 161")
      (value "BergStrip")
      (footprint "BergStrip 2.54mm")
      (libsource (lib "TOTUDU") (part "BergStrip"))
    )
    (comp (ref "BergStrip 162")
      (value "BergStrip")
      (footprint "BergStrip 2.54mm")
      (libsource (lib "TOTUDU") (part "BergStrip"))
    )
    (comp (ref "BergStrip 163")
      (value "BergStrip")
      (footprint "BergStrip 2.54mm")
      (libsource (lib "TOTUDU") (part "BergStrip"))
    )
    (comp (ref "BergStrip 164")
      (value "BergStrip")
      (footprint "BergStrip 2.54mm")
      (libsource (lib "TOTUDU") (part "BergStrip"))
    )
    (comp (ref "BergStrip 165")
      (value "BergStrip")
      (footprint "BergStrip 2.54mm")
      (libsource (lib "TOTUDU") (part "BergStrip"))
    )
    (comp (ref "BergStrip 166")
      (value "BergStrip")
      (footprint "BergStrip 2.54mm")
      (libsource (lib "TOTUDU") (part "BergStrip"))
    )
    (comp (ref "BergStrip 167")
      (value "BergStrip")
      (footprint "BergStrip 2.54mm")
      (libsource (lib "TOTUDU") (part "BergStrip"))
    )
    (comp (ref "BergStrip 168")
      (value "BergStrip")
      (footprint "BergStrip 2.54mm")
      (libsource (lib "TOTUDU") (part "BergStrip"))
    )
    (comp (ref "BergStrip 169")
      (value "BergStrip")
      (footprint "BergStrip 2.54mm")
      (libsource (lib "TOTUDU") (part "BergStrip"))
    )
    (comp (ref "BergStrip 170")
      (value "BergStrip")
      (footprint "BergStrip 2.54mm")
      (libsource (lib "TOTUDU") (part "BergStrip"))
    )
    (comp (ref "BergStrip 171")
      (value "BergStrip")
      (footprint "BergStrip 2.54mm")
      (libsource (lib "TOTUDU") (part "BergStrip"))
    )
    (comp (ref "BergStrip 172")
      (value "BergStrip")
      (footprint "BergStrip 2.54mm")
      (libsource (lib "TOTUDU") (part "BergStrip"))
    )
    (comp (ref "BergStrip 173")
      (value "BergStrip")
      (footprint "BergStrip 2.54mm")
      (libsource (lib "TOTUDU") (part "BergStrip"))
    )
    (comp (ref "BergStrip 174")
      (value "BergStrip")
      (footprint "BergStrip 2.54mm")
      (libsource (lib "TOTUDU") (part "BergStrip"))
    )
    (comp (ref "BergStrip 175")
      (value "BergStrip")
      (footprint "BergStrip 2.54mm")
      (libsource (lib "TOTUDU") (part "BergStrip"))
    )
    (comp (ref "BergStrip 176")
      (value "BergStrip")
      (footprint "BergStrip 2.54mm")
      (libsource (lib "TOTUDU") (part "BergStrip"))
    )
    (comp (ref "BergStrip 177")
      (value "BergStrip")
      (footprint "BergStrip 2.54mm")
      (libsource (lib "TOTUDU") (part "BergStrip"))
    )
    (comp (ref "BergStrip 178")
      (value "BergStrip")
      (footprint "BergStrip 2.54mm")
      (libsource (lib "TOTUDU") (part "BergStrip"))
    )
    (comp (ref "BergStrip 179")
      (value "BergStrip")
      (footprint "BergStrip 2.54mm")
      (libsource (lib "TOTUDU") (part "BergStrip"))
    )
    (comp (ref "BergStrip 180")
      (value "BergStrip")
      (footprint "BergStrip 2.54mm")
      (libsource (lib "TOTUDU") (part "BergStrip"))
    )
    (comp (ref "BergStrip 181")
      (value "BergStrip")
      (footprint "BergStrip 2.54mm")
      (libsource (lib "TOTUDU") (part "BergStrip"))
    )
    (comp (ref "BergStrip 182")
      (value "BergStrip")
      (footprint "BergStrip 2.54mm")
      (libsource (lib "TOTUDU") (part "BergStrip"))
    )
    (comp (ref "BergStrip 183")
      (value "BergStrip")
      (footprint "BergStrip 2.54mm")
      (libsource (lib "TOTUDU") (part "BergStrip"))
    )
    (comp (ref "BergStrip 184")
      (value "BergStrip")
      (footprint "BergStrip 2.54mm")
      (libsource (lib "TOTUDU") (part "BergStrip"))
    )
    (comp (ref "BergStrip 185")
      (value "BergStrip")
      (footprint "BergStrip 2.54mm")
      (libsource (lib "TOTUDU") (part "BergStrip"))
    )
    (comp (ref "BergStrip 186")
      (value "BergStrip")
      (footprint "BergStrip 2.54mm")
      (libsource (lib "TOTUDU") (part "BergStrip"))
    )
    (comp (ref "BergStrip 187")
      (value "BergStrip")
      (footprint "BergStrip 2.54mm")
      (libsource (lib "TOTUDU") (part "BergStrip"))
    )
    (comp (ref "BergStrip 188")
      (value "BergStrip")
      (footprint "BergStrip 2.54mm")
      (libsource (lib "TOTUDU") (part "BergStrip"))
    )
    (comp (ref "BergStrip 189")
      (value "BergStrip")
      (footprint "BergStrip 2.54mm")
      (libsource (lib "TOTUDU") (part "BergStrip"))
    )
    (comp (ref "BergStrip 190")
      (value "BergStrip")
      (footprint "BergStrip 2.54mm")
      (libsource (lib "TOTUDU") (part "BergStrip"))
    )
    (comp (ref "BergStrip 191")
      (value "BergStrip")
      (footprint "BergStrip 2.54mm")
      (libsource (lib "TOTUDU") (part "BergStrip"))
    )
    (comp (ref "BergStrip 192")
      (value "BergStrip")
      (footprint "BergStrip 2.54mm")
      (libsource (lib "TOTUDU") (part "BergStrip"))
    )
    (comp (ref "BergStrip 193")
      (value "BergStrip")
      (footprint "BergStrip 2.54mm")
      (libsource (lib "TOTUDU") (part "BergStrip"))
    )
    (comp (ref "BergStrip 194")
      (value "BergStrip")
      (footprint "BergStrip 2.54mm")
      (libsource (lib "TOTUDU") (part "BergStrip"))
    )
    (comp (ref "BergStrip 195")
      (value "BergStrip")
      (footprint "BergStrip 2.54mm")
      (libsource (lib "TOTUDU") (part "BergStrip"))
    )
    (comp (ref "BergStrip 196")
      (value "BergStrip")
      (footprint "BergStrip 2.54mm")
      (libsource (lib "TOTUDU") (part "BergStrip"))
    )
    (comp (ref "BergStrip 197")
      (value "BergStrip")
      (footprint "BergStrip 2.54mm")
      (libsource (lib "TOTUDU") (part "BergStrip"))
    )
    (comp (ref "BergStrip 198")
      (value "BergStrip")
      (footprint "BergStrip 2.54mm")
      (libsource (lib "TOTUDU") (part "BergStrip"))
    )
    (comp (ref "BergStrip 199")
      (value "BergStrip")
      (footprint "BergStrip 2.54mm")
      (libsource (lib "TOTUDU") (part "BergStrip"))
    )
    (comp (ref "BergStrip 200")
      (value "BergStrip")
      (footprint "BergStrip 2.54mm")
      (libsource (lib "TOTUDU") (part "BergStrip"))
    )
    (comp (ref "BergStrip GND_1")
      (value "BergStrip")
      (footprint "BergStrip 2.54mm")
      (libsource (lib "TOTUDU") (part "BergStrip"))
    )
    (comp (ref "BergStrip GND_2")
      (value "BergStrip")
      (footprint "BergStrip 2.54mm")
      (libsource (lib "TOTUDU") (part "BergStrip"))
    )
    (comp (ref "BergStrip GND_3")
      (value "BergStrip")
      (footprint "BergStrip 2.54mm")
      (libsource (lib "TOTUDU") (part "BergStrip"))
    )
    (comp (ref "BergStrip PMICEnable")
      (value "BergStrip")
      (footprint "BergStrip 2.54mm")
      (libsource (lib "TOTUDU") (part "BergStrip"))
    )
    (comp (ref "BuckMain")
      (value "Buck TPS62A06DRLR")
      (footprint "Buck TPS62A06DRLR")
      (libsource (lib "TOTUDU") (part "Buck TPS62A06DRLR"))
    )
    (comp (ref "C 0.75V 1uF")
      (value "1uF")
      (footprint "Capacitor 2012(0805)")
      (libsource (lib "TOTUDU") (part "Capacitor"))
    )
    (comp (ref "C 0.75V 47uF")
      (value "47uF")
      (footprint "Capacitor 2012(0805)")
      (libsource (lib "TOTUDU") (part "Capacitor"))
    )
    (comp (ref "C 0.75V Core1")
      (value "0.1uF")
      (footprint "Capacitor 1005(0402)")
      (libsource (lib "TOTUDU") (part "Capacitor"))
    )
    (comp (ref "C 0.75V Core2")
      (value "0.1uF")
      (footprint "Capacitor 1005(0402)")
      (libsource (lib "TOTUDU") (part "Capacitor"))
    )
    (comp (ref "C 0.75V Core3")
      (value "0.1uF")
      (footprint "Capacitor 1005(0402)")
      (libsource (lib "TOTUDU") (part "Capacitor"))
    )
    (comp (ref "C 0.75V Core4")
      (value "0.1uF")
      (footprint "Capacitor 1005(0402)")
      (libsource (lib "TOTUDU") (part "Capacitor"))
    )
    (comp (ref "C 0.75V Core5")
      (value "0.1uF")
      (footprint "Capacitor 1005(0402)")
      (libsource (lib "TOTUDU") (part "Capacitor"))
    )
    (comp (ref "C 0.75V Core6")
      (value "0.1uF")
      (footprint "Capacitor 1005(0402)")
      (libsource (lib "TOTUDU") (part "Capacitor"))
    )
    (comp (ref "C 0.75V Core7")
      (value "0.1uF")
      (footprint "Capacitor 1005(0402)")
      (libsource (lib "TOTUDU") (part "Capacitor"))
    )
    (comp (ref "C 0.75V Core8")
      (value "0.1uF")
      (footprint "Capacitor 1005(0402)")
      (libsource (lib "TOTUDU") (part "Capacitor"))
    )
    (comp (ref "C 0.75V Core9")
      (value "0.1uF")
      (footprint "Capacitor 1005(0402)")
      (libsource (lib "TOTUDU") (part "Capacitor"))
    )
    (comp (ref "C 0.75V Core10")
      (value "0.1uF")
      (footprint "Capacitor 1005(0402)")
      (libsource (lib "TOTUDU") (part "Capacitor"))
    )
    (comp (ref "C 0.75V Core11")
      (value "0.1uF")
      (footprint "Capacitor 1005(0402)")
      (libsource (lib "TOTUDU") (part "Capacitor"))
    )
    (comp (ref "C 0.85V 1uF")
      (value "1uF")
      (footprint "Capacitor 2012(0805)")
      (libsource (lib "TOTUDU") (part "Capacitor"))
    )
    (comp (ref "C 0.85V 4.7uF")
      (value "4.7uF")
      (footprint "Capacitor 2012(0805)")
      (libsource (lib "TOTUDU") (part "Capacitor"))
    )
    (comp (ref "C 0.85V Core1")
      (value "0.1uF")
      (footprint "Capacitor 1005(0402)")
      (libsource (lib "TOTUDU") (part "Capacitor"))
    )
    (comp (ref "C 0.85V Core2")
      (value "0.1uF")
      (footprint "Capacitor 1005(0402)")
      (libsource (lib "TOTUDU") (part "Capacitor"))
    )
    (comp (ref "C 0.85V MMC0")
      (value "0.01uF")
      (footprint "Capacitor 1005(0402)")
      (libsource (lib "TOTUDU") (part "Capacitor"))
    )
    (comp (ref "C 0.85V MMC0 0.1uF")
      (value "0.1uF")
      (footprint "Capacitor 2012(0805)")
      (libsource (lib "TOTUDU") (part "Capacitor"))
    )
    (comp (ref "C 0.85V MMC0DLL")
      (value "0.01uF")
      (footprint "Capacitor 1005(0402)")
      (libsource (lib "TOTUDU") (part "Capacitor"))
    )
    (comp (ref "C 0.85V MMC0DLL 0.1uF")
      (value "0.1uF")
      (footprint "Capacitor 2012(0805)")
      (libsource (lib "TOTUDU") (part "Capacitor"))
    )
    (comp (ref "C 0.85V SERDES 0.1uF")
      (value "0.1uF")
      (footprint "Capacitor 2012(0805)")
      (libsource (lib "TOTUDU") (part "Capacitor"))
    )
    (comp (ref "C 0.85V SERDES1")
      (value "0.01uF")
      (footprint "Capacitor 1005(0402)")
      (libsource (lib "TOTUDU") (part "Capacitor"))
    )
    (comp (ref "C 0.85V SERDES2")
      (value "0.01uF")
      (footprint "Capacitor 1005(0402)")
      (libsource (lib "TOTUDU") (part "Capacitor"))
    )
    (comp (ref "C 0.85V SERDES3")
      (value "0.01uF")
      (footprint "Capacitor 1005(0402)")
      (libsource (lib "TOTUDU") (part "Capacitor"))
    )
    (comp (ref "C 0.85V USB")
      (value "0.1uF")
      (footprint "Capacitor 1005(0402)")
      (libsource (lib "TOTUDU") (part "Capacitor"))
    )
    (comp (ref "C 0.85V USB 1uF")
      (value "1uF")
      (footprint "Capacitor 2012(0805)")
      (libsource (lib "TOTUDU") (part "Capacitor"))
    )
    (comp (ref "C 1.1V DDR 1uF")
      (value "1uF")
      (footprint "Capacitor 2012(0805)")
      (libsource (lib "TOTUDU") (part "Capacitor"))
    )
    (comp (ref "C 1.1V DDR 10uF")
      (value "10uF")
      (footprint "Capacitor 2012(0805)")
      (libsource (lib "TOTUDU") (part "Capacitor"))
    )
    (comp (ref "C 1.1V DDR VDD2 10uF")
      (value "10uF")
      (footprint "Capacitor 2012(0805)")
      (libsource (lib "TOTUDU") (part "Capacitor"))
    )
    (comp (ref "C 1.1V DDR VDDQ 10uF")
      (value "10uF")
      (footprint "Capacitor 2012(0805)")
      (libsource (lib "TOTUDU") (part "Capacitor"))
    )
    (comp (ref "C 1.1V DDR1")
      (value "0.1uF")
      (footprint "Capacitor 1005(0402)")
      (libsource (lib "TOTUDU") (part "Capacitor"))
    )
    (comp (ref "C 1.1V DDR2")
      (value "0.1uF")
      (footprint "Capacitor 1005(0402)")
      (libsource (lib "TOTUDU") (part "Capacitor"))
    )
    (comp (ref "C 1.1V DDR3")
      (value "0.1uF")
      (footprint "Capacitor 1005(0402)")
      (libsource (lib "TOTUDU") (part "Capacitor"))
    )
    (comp (ref "C 1.1V DDR4")
      (value "0.1uF")
      (footprint "Capacitor 1005(0402)")
      (libsource (lib "TOTUDU") (part "Capacitor"))
    )
    (comp (ref "C 1.1V DDR5")
      (value "0.1uF")
      (footprint "Capacitor 1005(0402)")
      (libsource (lib "TOTUDU") (part "Capacitor"))
    )
    (comp (ref "C 1.1V DDR6")
      (value "0.1uF")
      (footprint "Capacitor 1005(0402)")
      (libsource (lib "TOTUDU") (part "Capacitor"))
    )
    (comp (ref "C 1.1V DDR7")
      (value "0.1uF")
      (footprint "Capacitor 1005(0402)")
      (libsource (lib "TOTUDU") (part "Capacitor"))
    )
    (comp (ref "C 1.1V DDR8")
      (value "0.1uF")
      (footprint "Capacitor 1005(0402)")
      (libsource (lib "TOTUDU") (part "Capacitor"))
    )
    (comp (ref "C 1.1V DDR9")
      (value "0.1uF")
      (footprint "Capacitor 1005(0402)")
      (libsource (lib "TOTUDU") (part "Capacitor"))
    )
    (comp (ref "C 1.1V DDR10")
      (value "0.1uF")
      (footprint "Capacitor 1005(0402)")
      (libsource (lib "TOTUDU") (part "Capacitor"))
    )
    (comp (ref "C 1.1V DDR11")
      (value "0.1uF")
      (footprint "Capacitor 1005(0402)")
      (libsource (lib "TOTUDU") (part "Capacitor"))
    )
    (comp (ref "C 1.1V DDR12")
      (value "0.1uF")
      (footprint "Capacitor 1005(0402)")
      (libsource (lib "TOTUDU") (part "Capacitor"))
    )
    (comp (ref "C 1.1V DDR13")
      (value "0.1uF")
      (footprint "Capacitor 1005(0402)")
      (libsource (lib "TOTUDU") (part "Capacitor"))
    )
    (comp (ref "C 1.1V DDR14")
      (value "0.1uF")
      (footprint "Capacitor 1005(0402)")
      (libsource (lib "TOTUDU") (part "Capacitor"))
    )
    (comp (ref "C 1.1V DDR15")
      (value "0.1uF")
      (footprint "Capacitor 1005(0402)")
      (libsource (lib "TOTUDU") (part "Capacitor"))
    )
    (comp (ref "C 1.1V DDR16")
      (value "0.1uF")
      (footprint "Capacitor 1005(0402)")
      (libsource (lib "TOTUDU") (part "Capacitor"))
    )
    (comp (ref "C 1.1V DDR17")
      (value "0.1uF")
      (footprint "Capacitor 1005(0402)")
      (libsource (lib "TOTUDU") (part "Capacitor"))
    )
    (comp (ref "C 1.1V DDR18")
      (value "0.1uF")
      (footprint "Capacitor 1005(0402)")
      (libsource (lib "TOTUDU") (part "Capacitor"))
    )
    (comp (ref "C 1.1V DDR19")
      (value "0.1uF")
      (footprint "Capacitor 1005(0402)")
      (libsource (lib "TOTUDU") (part "Capacitor"))
    )
    (comp (ref "C 1.1V DDR20")
      (value "0.1uF")
      (footprint "Capacitor 1005(0402)")
      (libsource (lib "TOTUDU") (part "Capacitor"))
    )
    (comp (ref "C 1.1V DDR21")
      (value "0.1uF")
      (footprint "Capacitor 1005(0402)")
      (libsource (lib "TOTUDU") (part "Capacitor"))
    )
    (comp (ref "C 1.1V DDR22")
      (value "0.1uF")
      (footprint "Capacitor 1005(0402)")
      (libsource (lib "TOTUDU") (part "Capacitor"))
    )
    (comp (ref "C 1.1V DDR23")
      (value "0.1uF")
      (footprint "Capacitor 1005(0402)")
      (libsource (lib "TOTUDU") (part "Capacitor"))
    )
    (comp (ref "C 1.1V DDR24")
      (value "0.1uF")
      (footprint "Capacitor 1005(0402)")
      (libsource (lib "TOTUDU") (part "Capacitor"))
    )
    (comp (ref "C 1.1V DDR25")
      (value "0.1uF")
      (footprint "Capacitor 1005(0402)")
      (libsource (lib "TOTUDU") (part "Capacitor"))
    )
    (comp (ref "C 1.1V DDR26")
      (value "0.1uF")
      (footprint "Capacitor 1005(0402)")
      (libsource (lib "TOTUDU") (part "Capacitor"))
    )
    (comp (ref "C 1.1V DDR27")
      (value "0.1uF")
      (footprint "Capacitor 1005(0402)")
      (libsource (lib "TOTUDU") (part "Capacitor"))
    )
    (comp (ref "C 1.8V ADC")
      (value "0.1uF")
      (footprint "Capacitor 1005(0402)")
      (libsource (lib "TOTUDU") (part "Capacitor"))
    )
    (comp (ref "C 1.8V ADC 1uF")
      (value "1uF")
      (footprint "Capacitor 2012(0805)")
      (libsource (lib "TOTUDU") (part "Capacitor"))
    )
    (comp (ref "C 1.8V ADCREF")
      (value "1uF")
      (footprint "Capacitor 1005(0402)")
      (libsource (lib "TOTUDU") (part "Capacitor"))
    )
    (comp (ref "C 1.8V ClockBuffer")
      (value "1uF")
      (footprint "Capacitor 2012(0805)")
      (libsource (lib "TOTUDU") (part "Capacitor"))
    )
    (comp (ref "C 1.8V Crystal")
      (value "1uF")
      (footprint "Capacitor 2012(0805)")
      (libsource (lib "TOTUDU") (part "Capacitor"))
    )
    (comp (ref "C 1.8V DDR VDD1 10uF")
      (value "10uF")
      (footprint "Capacitor 2012(0805)")
      (libsource (lib "TOTUDU") (part "Capacitor"))
    )
    (comp (ref "C 1.8V DDR1")
      (value "0.1uF")
      (footprint "Capacitor 1005(0402)")
      (libsource (lib "TOTUDU") (part "Capacitor"))
    )
    (comp (ref "C 1.8V DDR2")
      (value "0.1uF")
      (footprint "Capacitor 1005(0402)")
      (libsource (lib "TOTUDU") (part "Capacitor"))
    )
    (comp (ref "C 1.8V DDR3")
      (value "0.1uF")
      (footprint "Capacitor 1005(0402)")
      (libsource (lib "TOTUDU") (part "Capacitor"))
    )
    (comp (ref "C 1.8V DDR4")
      (value "0.1uF")
      (footprint "Capacitor 1005(0402)")
      (libsource (lib "TOTUDU") (part "Capacitor"))
    )
    (comp (ref "C 1.8V DDR5")
      (value "0.1uF")
      (footprint "Capacitor 1005(0402)")
      (libsource (lib "TOTUDU") (part "Capacitor"))
    )
    (comp (ref "C 1.8V DDR6")
      (value "0.1uF")
      (footprint "Capacitor 1005(0402)")
      (libsource (lib "TOTUDU") (part "Capacitor"))
    )
    (comp (ref "C 1.8V DDR7")
      (value "0.1uF")
      (footprint "Capacitor 1005(0402)")
      (libsource (lib "TOTUDU") (part "Capacitor"))
    )
    (comp (ref "C 1.8V DDR8")
      (value "0.1uF")
      (footprint "Capacitor 1005(0402)")
      (libsource (lib "TOTUDU") (part "Capacitor"))
    )
    (comp (ref "C 1.8V MCU")
      (value "0.1uF")
      (footprint "Capacitor 1005(0402)")
      (libsource (lib "TOTUDU") (part "Capacitor"))
    )
    (comp (ref "C 1.8V MCU 1uF")
      (value "1uF")
      (footprint "Capacitor 2012(0805)")
      (libsource (lib "TOTUDU") (part "Capacitor"))
    )
    (comp (ref "C 1.8V MMC0")
      (value "0.1uF")
      (footprint "Capacitor 1005(0402)")
      (libsource (lib "TOTUDU") (part "Capacitor"))
    )
    (comp (ref "C 1.8V MMC0 1uF")
      (value "1uF")
      (footprint "Capacitor 2012(0805)")
      (libsource (lib "TOTUDU") (part "Capacitor"))
    )
    (comp (ref "C 1.8V OSC")
      (value "0.1uF")
      (footprint "Capacitor 1005(0402)")
      (libsource (lib "TOTUDU") (part "Capacitor"))
    )
    (comp (ref "C 1.8V OSC 1uF")
      (value "1uF")
      (footprint "Capacitor 2012(0805)")
      (libsource (lib "TOTUDU") (part "Capacitor"))
    )
    (comp (ref "C 1.8V PLL0")
      (value "0.1uF")
      (footprint "Capacitor 1005(0402)")
      (libsource (lib "TOTUDU") (part "Capacitor"))
    )
    (comp (ref "C 1.8V PLL0 1uF")
      (value "1uF")
      (footprint "Capacitor 2012(0805)")
      (libsource (lib "TOTUDU") (part "Capacitor"))
    )
    (comp (ref "C 1.8V PLL1")
      (value "0.1uF")
      (footprint "Capacitor 1005(0402)")
      (libsource (lib "TOTUDU") (part "Capacitor"))
    )
    (comp (ref "C 1.8V PLL1 1uF")
      (value "1uF")
      (footprint "Capacitor 2012(0805)")
      (libsource (lib "TOTUDU") (part "Capacitor"))
    )
    (comp (ref "C 1.8V PLL2")
      (value "0.1uF")
      (footprint "Capacitor 1005(0402)")
      (libsource (lib "TOTUDU") (part "Capacitor"))
    )
    (comp (ref "C 1.8V PLL2 1uF")
      (value "1uF")
      (footprint "Capacitor 2012(0805)")
      (libsource (lib "TOTUDU") (part "Capacitor"))
    )
    (comp (ref "C 1.8V SERDES")
      (value "0.1uF")
      (footprint "Capacitor 1005(0402)")
      (libsource (lib "TOTUDU") (part "Capacitor"))
    )
    (comp (ref "C 1.8V SERDES 1uF")
      (value "1uF")
      (footprint "Capacitor 2012(0805)")
      (libsource (lib "TOTUDU") (part "Capacitor"))
    )
    (comp (ref "C 1.8V USB")
      (value "0.1uF")
      (footprint "Capacitor 1005(0402)")
      (libsource (lib "TOTUDU") (part "Capacitor"))
    )
    (comp (ref "C 1.8V USB 1uF")
      (value "1uF")
      (footprint "Capacitor 2012(0805)")
      (libsource (lib "TOTUDU") (part "Capacitor"))
    )
    (comp (ref "C 3.3V 1uF")
      (value "1uF")
      (footprint "Capacitor 2012(0805)")
      (libsource (lib "TOTUDU") (part "Capacitor"))
    )
    (comp (ref "C 3.3V 4.7uF")
      (value "4.7uF")
      (footprint "Capacitor 2012(0805)")
      (libsource (lib "TOTUDU") (part "Capacitor"))
    )
    (comp (ref "C 3.3V MCU1")
      (value "0.1uF")
      (footprint "Capacitor 1005(0402)")
      (libsource (lib "TOTUDU") (part "Capacitor"))
    )
    (comp (ref "C 3.3V MCU2")
      (value "0.1uF")
      (footprint "Capacitor 1005(0402)")
      (libsource (lib "TOTUDU") (part "Capacitor"))
    )
    (comp (ref "C 3.3V MCU3")
      (value "0.1uF")
      (footprint "Capacitor 1005(0402)")
      (libsource (lib "TOTUDU") (part "Capacitor"))
    )
    (comp (ref "C 3.3V SDIO")
      (value "0.1uF")
      (footprint "Capacitor 1005(0402)")
      (libsource (lib "TOTUDU") (part "Capacitor"))
    )
    (comp (ref "C 3.3V SHV01")
      (value "0.1uF")
      (footprint "Capacitor 1005(0402)")
      (libsource (lib "TOTUDU") (part "Capacitor"))
    )
    (comp (ref "C 3.3V SHV02")
      (value "0.1uF")
      (footprint "Capacitor 1005(0402)")
      (libsource (lib "TOTUDU") (part "Capacitor"))
    )
    (comp (ref "C 3.3V SHV03")
      (value "0.1uF")
      (footprint "Capacitor 1005(0402)")
      (libsource (lib "TOTUDU") (part "Capacitor"))
    )
    (comp (ref "C 3.3V SHV11")
      (value "0.1uF")
      (footprint "Capacitor 1005(0402)")
      (libsource (lib "TOTUDU") (part "Capacitor"))
    )
    (comp (ref "C 3.3V SHV12")
      (value "0.1uF")
      (footprint "Capacitor 1005(0402)")
      (libsource (lib "TOTUDU") (part "Capacitor"))
    )
    (comp (ref "C 3.3V SHV13")
      (value "0.1uF")
      (footprint "Capacitor 1005(0402)")
      (libsource (lib "TOTUDU") (part "Capacitor"))
    )
    (comp (ref "C 3.3V SHV21")
      (value "0.1uF")
      (footprint "Capacitor 1005(0402)")
      (libsource (lib "TOTUDU") (part "Capacitor"))
    )
    (comp (ref "C 3.3V SHV22")
      (value "0.1uF")
      (footprint "Capacitor 1005(0402)")
      (libsource (lib "TOTUDU") (part "Capacitor"))
    )
    (comp (ref "C 3.3V SHV23")
      (value "0.1uF")
      (footprint "Capacitor 1005(0402)")
      (libsource (lib "TOTUDU") (part "Capacitor"))
    )
    (comp (ref "C 3.3V SHV31")
      (value "0.1uF")
      (footprint "Capacitor 1005(0402)")
      (libsource (lib "TOTUDU") (part "Capacitor"))
    )
    (comp (ref "C 3.3V SHV32")
      (value "0.1uF")
      (footprint "Capacitor 1005(0402)")
      (libsource (lib "TOTUDU") (part "Capacitor"))
    )
    (comp (ref "C 3.3V SHV41")
      (value "0.1uF")
      (footprint "Capacitor 1005(0402)")
      (libsource (lib "TOTUDU") (part "Capacitor"))
    )
    (comp (ref "C 3.3V SHV42")
      (value "0.1uF")
      (footprint "Capacitor 1005(0402)")
      (libsource (lib "TOTUDU") (part "Capacitor"))
    )
    (comp (ref "C 3.3V SHV51")
      (value "0.1uF")
      (footprint "Capacitor 1005(0402)")
      (libsource (lib "TOTUDU") (part "Capacitor"))
    )
    (comp (ref "C 3.3V SHV52")
      (value "0.1uF")
      (footprint "Capacitor 1005(0402)")
      (libsource (lib "TOTUDU") (part "Capacitor"))
    )
    (comp (ref "C 3.3V USB")
      (value "0.1uF")
      (footprint "Capacitor 1005(0402)")
      (libsource (lib "TOTUDU") (part "Capacitor"))
    )
    (comp (ref "C AM6442 CAP VDDS0")
      (value "1uF")
      (footprint "Capacitor 1005(0402)")
      (libsource (lib "TOTUDU") (part "Capacitor"))
    )
    (comp (ref "C AM6442 CAP VDDS1")
      (value "1uF")
      (footprint "Capacitor 1005(0402)")
      (libsource (lib "TOTUDU") (part "Capacitor"))
    )
    (comp (ref "C AM6442 CAP VDDS2")
      (value "1uF")
      (footprint "Capacitor 1005(0402)")
      (libsource (lib "TOTUDU") (part "Capacitor"))
    )
    (comp (ref "C AM6442 CAP VDDS3")
      (value "1uF")
      (footprint "Capacitor 1005(0402)")
      (libsource (lib "TOTUDU") (part "Capacitor"))
    )
    (comp (ref "C AM6442 CAP VDDS4")
      (value "1uF")
      (footprint "Capacitor 1005(0402)")
      (libsource (lib "TOTUDU") (part "Capacitor"))
    )
    (comp (ref "C AM6442 CAP VDDS5")
      (value "1uF")
      (footprint "Capacitor 1005(0402)")
      (libsource (lib "TOTUDU") (part "Capacitor"))
    )
    (comp (ref "C AM6442 CAP VDDS_MCU")
      (value "1uF")
      (footprint "Capacitor 1005(0402)")
      (libsource (lib "TOTUDU") (part "Capacitor"))
    )
    (comp (ref "C AM6442 CAP VDDS_MMC")
      (value "1uF")
      (footprint "Capacitor 1005(0402)")
      (libsource (lib "TOTUDU") (part "Capacitor"))
    )
    (comp (ref "C BuckMain Feedback")
      (value "120pF")
      (footprint "Capacitor 2012(0805)")
      (libsource (lib "TOTUDU") (part "Capacitor"))
    )
    (comp (ref "C BuckMain VIN")
      (value "22uF")
      (footprint "Capacitor 2012(0805)")
      (libsource (lib "TOTUDU") (part "Capacitor"))
    )
    (comp (ref "C BuckMain VOUT1")
      (value "22uF")
      (footprint "Capacitor 2012(0805)")
      (libsource (lib "TOTUDU") (part "Capacitor"))
    )
    (comp (ref "C BuckMain VOUT2")
      (value "22uF")
      (footprint "Capacitor 2012(0805)")
      (libsource (lib "TOTUDU") (part "Capacitor"))
    )
    (comp (ref "C BuckMain VOUT3")
      (value "22uF")
      (footprint "Capacitor 2012(0805)")
      (libsource (lib "TOTUDU") (part "Capacitor"))
    )
    (comp (ref "C PMIC 0.75V")
      (value "47uF")
      (footprint "Capacitor 2012(0805)")
      (libsource (lib "TOTUDU") (part "Capacitor"))
    )
    (comp (ref "C PMIC 0.85V")
      (value "2.2uF")
      (footprint "Capacitor 2012(0805)")
      (libsource (lib "TOTUDU") (part "Capacitor"))
    )
    (comp (ref "C PMIC 1.1V")
      (value "47uF")
      (footprint "Capacitor 2012(0805)")
      (libsource (lib "TOTUDU") (part "Capacitor"))
    )
    (comp (ref "C PMIC 1.8V")
      (value "47uF")
      (footprint "Capacitor 2012(0805)")
      (libsource (lib "TOTUDU") (part "Capacitor"))
    )
    (comp (ref "C PMIC 1.8V*")
      (value "2.2uF")
      (footprint "Capacitor 2012(0805)")
      (libsource (lib "TOTUDU") (part "Capacitor"))
    )
    (comp (ref "C PMIC 2.5V")
      (value "2.2uF")
      (footprint "Capacitor 2012(0805)")
      (libsource (lib "TOTUDU") (part "Capacitor"))
    )
    (comp (ref "C PMIC InternalBypass")
      (value "2.2uF")
      (footprint "Capacitor 2012(0805)")
      (libsource (lib "TOTUDU") (part "Capacitor"))
    )
    (comp (ref "C PMIC SD_VDD")
      (value "2.2uF")
      (footprint "Capacitor 2012(0805)")
      (libsource (lib "TOTUDU") (part "Capacitor"))
    )
    (comp (ref "C PMIC VIN B1")
      (value "4.7uF")
      (footprint "Capacitor 2012(0805)")
      (libsource (lib "TOTUDU") (part "Capacitor"))
    )
    (comp (ref "C PMIC VIN B2")
      (value "4.7uF")
      (footprint "Capacitor 2012(0805)")
      (libsource (lib "TOTUDU") (part "Capacitor"))
    )
    (comp (ref "C PMIC VIN B3")
      (value "4.7uF")
      (footprint "Capacitor 2012(0805)")
      (libsource (lib "TOTUDU") (part "Capacitor"))
    )
    (comp (ref "C PMIC VIN LDO1")
      (value "2.2uF")
      (footprint "Capacitor 2012(0805)")
      (libsource (lib "TOTUDU") (part "Capacitor"))
    )
    (comp (ref "C PMIC VIN LDO2")
      (value "2.2uF")
      (footprint "Capacitor 2012(0805)")
      (libsource (lib "TOTUDU") (part "Capacitor"))
    )
    (comp (ref "C PMIC VIN LDO34")
      (value "4.7uF")
      (footprint "Capacitor 2012(0805)")
      (libsource (lib "TOTUDU") (part "Capacitor"))
    )
    (comp (ref "C PMIC VSYS")
      (value "4.7uF")
      (footprint "Capacitor 2012(0805)")
      (libsource (lib "TOTUDU") (part "Capacitor"))
    )
    (comp (ref "C Switch3.3V VIN")
      (value "10uF")
      (footprint "Capacitor 2012(0805)")
      (libsource (lib "TOTUDU") (part "Capacitor"))
    )
    (comp (ref "C Switch3.3V VOUT")
      (value "1uF")
      (footprint "Capacitor 2012(0805)")
      (libsource (lib "TOTUDU") (part "Capacitor"))
    )
    (comp (ref "ClockBuffer")
      (value "Clock Buffer")
      (footprint "ClockBuffer LMK1C1104")
      (libsource (lib "TOTUDU") (part "Clock Buffer"))
    )
    (comp (ref "CONSD")
      (value "DM3AT-SF-PEJM5_40_")
      (footprint "MicroSD Connector MEM2085")
      (fields
        (field (name "MOUSER PART NUMBER") "798-DM3AT-SF-PEJM540")
        (field (name "MANUFACTURER_PART_NUMBER") "DM3AT-SF-PEJM5(40)")
      )
      (libsource (lib "TOTUDU") (part "Connector MicroSD"))
    )
    (comp (ref "DP83867IRRGZR")
      (value "DP83867IRRGZR")
      (footprint "DP83867IRRGZR")
      (fields
        (field (name "ALTERNATE_PARTNUMBER") "DP83867IRRGZT")
        (field (name "MANUFACTURER") "Texas Instruments")
      )
      (libsource (lib "TOTUDU") (part "DP83867IRRGZR"))
    )
    (comp (ref "F 0.85V MMC0")
      (value "Ferrite")
      (footprint "Ferrite 2012(0805)")
      (libsource (lib "TOTUDU") (part "Ferrite"))
    )
    (comp (ref "F 0.85V MMC0DLL")
      (value "Ferrite")
      (footprint "Ferrite 2012(0805)")
      (libsource (lib "TOTUDU") (part "Ferrite"))
    )
    (comp (ref "F 0.85V SERDES")
      (value "Ferrite")
      (footprint "Ferrite 2012(0805)")
      (libsource (lib "TOTUDU") (part "Ferrite"))
    )
    (comp (ref "F 0.85V USB")
      (value "Ferrite")
      (footprint "Ferrite 2012(0805)")
      (libsource (lib "TOTUDU") (part "Ferrite"))
    )
    (comp (ref "F 1.1VV DP8386")
      (value "Ferrite")
      (footprint "Ferrite 2012(0805)")
      (libsource (lib "TOTUDU") (part "Ferrite"))
    )
    (comp (ref "F 1.8V ADC")
      (value "Ferrite")
      (footprint "Ferrite 2012(0805)")
      (libsource (lib "TOTUDU") (part "Ferrite"))
    )
    (comp (ref "F 1.8V Crystal")
      (value "Ferrite")
      (footprint "Ferrite 2012(0805)")
      (libsource (lib "TOTUDU") (part "Ferrite"))
    )
    (comp (ref "F 1.8V MCU")
      (value "Ferrite")
      (footprint "Ferrite 2012(0805)")
      (libsource (lib "TOTUDU") (part "Ferrite"))
    )
    (comp (ref "F 1.8V MMC0")
      (value "Ferrite")
      (footprint "Ferrite 2012(0805)")
      (libsource (lib "TOTUDU") (part "Ferrite"))
    )
    (comp (ref "F 1.8V PLL0")
      (value "Ferrite")
      (footprint "Ferrite 2012(0805)")
      (libsource (lib "TOTUDU") (part "Ferrite"))
    )
    (comp (ref "F 1.8V PLL1")
      (value "Ferrite")
      (footprint "Ferrite 2012(0805)")
      (libsource (lib "TOTUDU") (part "Ferrite"))
    )
    (comp (ref "F 1.8V PLL2")
      (value "Ferrite")
      (footprint "Ferrite 2012(0805)")
      (libsource (lib "TOTUDU") (part "Ferrite"))
    )
    (comp (ref "F 1.8V SERDES")
      (value "Ferrite")
      (footprint "Ferrite 2012(0805)")
      (libsource (lib "TOTUDU") (part "Ferrite"))
    )
    (comp (ref "F 1.8V USB")
      (value "Ferrite")
      (footprint "Ferrite 2012(0805)")
      (libsource (lib "TOTUDU") (part "Ferrite"))
    )
    (comp (ref "L BuckMain")
      (value "0.22uH")
      (footprint "Inductor 5.2x5.2")
      (libsource (lib "TOTUDU") (part "Inductor"))
    )
    (comp (ref "L PMIC Buck1")
      (value "0.47uH")
      (footprint "Inductor 2016(0806)")
      (libsource (lib "TOTUDU") (part "Inductor"))
    )
    (comp (ref "L PMIC Buck2")
      (value "0.47uH")
      (footprint "Inductor 2016(0806)")
      (libsource (lib "TOTUDU") (part "Inductor"))
    )
    (comp (ref "L PMIC Buck3")
      (value "0.47uH")
      (footprint "Inductor 2016(0806)")
      (libsource (lib "TOTUDU") (part "Inductor"))
    )
    (comp (ref "LED 3.3Vb")
      (value "Ferrite")
      (footprint "LED 2012(0805)")
      (libsource (lib "TOTUDU") (part "LED"))
    )
    (comp (ref "LED VCC")
      (value "Ferrite")
      (footprint "LED 2012(0805)")
      (libsource (lib "TOTUDU") (part "LED"))
    )
    (comp (ref "LPDDR4")
      (value "Die Density: 16Gbits  Organization  x 16 bits: 128M words x 16 bits x 8 banks  2 pieces of 16Gb (x16) in one package (For 32Gb case)  Row Address: R0 ~ R16  Column Address: C0 ~ C9  Package  200-ball FBGA  Power supply  VDD1 = 1.8V (1.70V to 1.95V) ,  VDD2, VDDCA and VDDQ = 1.1V (1.06V to 1.17V)  Data rate:  3733Mbps max. Backward compatible  Eight internal banks per channel for concurrent operation  Burst lengths (BL): 16, 32 and on-the-fly - On the fly mode is enabled by   Source:  Datasheet")
      (footprint "LPDDR4")
      (fields
        (field (name "MANUFACTURER_PART_NUMBER") "D1611PM3BDGUI-U")
        (field (name "LIBRARYNAME") "TOTUDU")
      )
      (libsource (lib "TOTUDU") (part "LPDDR4 D1611PM3BDGUI-U"))
    )
    (comp (ref "MagJack0")
      (value "MagJack 8P9C")
      (footprint "MagJack 8P9C")
      (description "CRJ009-ML4-TH")
      (fields (field (name "MF") "{'manufacturer': u'CUI'}"))
      (libsource (lib "TOTUDU") (part "MagJack 8P9C"))
    )
    (comp (ref "PMIC")
      (value "PMIC TPS6522053")
      (footprint "PMIC TPS6522053")
      (libsource (lib "TOTUDU") (part "PMIC TPS6522053"))
    )
    (comp (ref "R 3.3Vb LED")
      (value "Resistor")
      (footprint "Resistor 2012(0805)")
      (libsource (lib "TOTUDU") (part "Resistor"))
    )
    (comp (ref "R BuckMain Divider1")
      (value "Resistor")
      (footprint "Resistor 2012(0805)")
      (libsource (lib "TOTUDU") (part "Resistor"))
    )
    (comp (ref "R BuckMain Divider3")
      (value "Resistor")
      (footprint "Resistor 2012(0805)")
      (libsource (lib "TOTUDU") (part "Resistor"))
    )
    (comp (ref "R DDR CAL")
      (value "Resistor")
      (footprint "Resistor 2012(0805)")
      (libsource (lib "TOTUDU") (part "Resistor"))
    )
    (comp (ref "R DDR ODTCA")
      (value "Resistor")
      (footprint "Resistor 2012(0805)")
      (libsource (lib "TOTUDU") (part "Resistor"))
    )
    (comp (ref "R DDR RESET")
      (value "Resistor")
      (footprint "Resistor 2012(0805)")
      (libsource (lib "TOTUDU") (part "Resistor"))
    )
    (comp (ref "R DDR ZQ")
      (value "Resistor")
      (footprint "Resistor 2012(0805)")
      (libsource (lib "TOTUDU") (part "Resistor"))
    )
    (comp (ref "R PMIC SDPullup")
      (value "Resistor")
      (footprint "Resistor 2012(0805)")
      (libsource (lib "TOTUDU") (part "Resistor"))
    )
    (comp (ref "R VCC LED")
      (value "Resistor")
      (footprint "Resistor 2012(0805)")
      (libsource (lib "TOTUDU") (part "Resistor"))
    )
    (comp (ref "R VMON 1")
      (value "Resistor")
      (footprint "Resistor 2012(0805)")
      (libsource (lib "TOTUDU") (part "Resistor"))
    )
    (comp (ref "R VMON 2")
      (value "Resistor")
      (footprint "Resistor 2012(0805)")
      (libsource (lib "TOTUDU") (part "Resistor"))
    )
    (comp (ref "Switch3.3V")
      (value "Switch TPS22959DNYR")
      (footprint "Switch TPS22959DNYR")
      (fields (field (name "PARTNUMBER") "TPS22959DNY") (field (name "MANUFACTURER") "Texas Instruments"))
      (libsource (lib "TOTUDU") (part "Switch TPS22959DNYR"))
    )
    (comp (ref "X")
      (value "Crystal 4pin")
      (footprint "Crystal 2.5x2mm")
      (fields
        (field (name "MOUSER PART NUMBER") "520-2520MV-250-CN-T")
        (field (name "MANUFACTURER_PART_NUMBER") "ECS-2520MV-250-CN-TR")
      )
      (libsource (lib "TOTUDU") (part "Crystal 4pin"))
    )
  )
  (nets
    (net (code "1") (name "/0.75Vb Inductor") (class "Default")
      (node (ref "L PMIC Buck1") (pin "1") (pinfunction "1_1") (pintype "passive"))
      (node (ref "PMIC") (pin "2") (pinfunction "LX_B1_1_2") (pintype "passive"))
      (node (ref "PMIC") (pin "3") (pinfunction "LX_B1_2_3") (pintype "passive"))
    )
    (net (code "2") (name "/0.85V MMC0") (class "Default")
      (node (ref "AM6442") (pin "K13") (pinfunction "VDD_MMC0_K13") (pintype "passive"))
      (node (ref "C 0.85V MMC0") (pin "2") (pinfunction "2_2") (pintype "passive"))
      (node (ref "C 0.85V MMC0 0.1uF") (pin "2") (pinfunction "2_2") (pintype "passive"))
      (node (ref "F 0.85V MMC0") (pin "2") (pinfunction "2_2") (pintype "passive"))
    )
    (net (code "3") (name "/0.85V MMC0DLL") (class "Default")
      (node (ref "AM6442") (pin "H14") (pinfunction "VDD_MMC0_DLL_H14") (pintype "passive"))
      (node (ref "C 0.85V MMC0DLL") (pin "2") (pinfunction "2_2") (pintype "passive"))
      (node (ref "C 0.85V MMC0DLL 0.1uF") (pin "2") (pinfunction "2_2") (pintype "passive"))
      (node (ref "F 0.85V MMC0DLL") (pin "2") (pinfunction "2_2") (pintype "passive"))
    )
    (net (code "4") (name "/0.85V SERDES") (class "Default")
      (node (ref "AM6442") (pin "P11") (pinfunction "VDDA_0P85_SERDES0_C_P11") (pintype "passive"))
      (node (ref "AM6442") (pin "P12") (pinfunction "VDDA_0P85_SERDES0_1_P12") (pintype "passive"))
      (node (ref "AM6442") (pin "P13") (pinfunction "VDDA_0P85_SERDES0_2_P13") (pintype "passive"))
      (node (ref "C 0.85V SERDES 0.1uF") (pin "2") (pinfunction "2_2") (pintype "passive"))
      (node (ref "C 0.85V SERDES1") (pin "2") (pinfunction "2_2") (pintype "passive"))
      (node (ref "C 0.85V SERDES2") (pin "2") (pinfunction "2_2") (pintype "passive"))
      (node (ref "C 0.85V SERDES3") (pin "2") (pinfunction "2_2") (pintype "passive"))
      (node (ref "F 0.85V SERDES") (pin "2") (pinfunction "2_2") (pintype "passive"))
    )
    (net (code "5") (name "/0.85V USB") (class "Default")
      (node (ref "AM6442") (pin "T12") (pinfunction "VDDA_0P85_USB_T12") (pintype "passive"))
      (node (ref "C 0.85V USB") (pin "2") (pinfunction "2_2") (pintype "passive"))
      (node (ref "C 0.85V USB 1uF") (pin "2") (pinfunction "2_2") (pintype "passive"))
      (node (ref "F 0.85V USB") (pin "2") (pinfunction "2_2") (pintype "passive"))
    )
    (net (code "6") (name "/1.1V DP8386") (class "Default")
      (node (ref "DP83867IRRGZR") (pin "24") (pinfunction "VDD1P0_24") (pintype "passive"))
      (node (ref "DP83867IRRGZR") (pin "31") (pinfunction "VDD1P0_31") (pintype "passive"))
      (node (ref "DP83867IRRGZR") (pin "42") (pinfunction "VDD1P0_42") (pintype "passive"))
      (node (ref "DP83867IRRGZR") (pin "6") (pinfunction "VDD1P0_6") (pintype "passive"))
      (node (ref "F 1.1VV DP8386") (pin "2") (pinfunction "2_2") (pintype "passive"))
    )
    (net (code "7") (name "/1.1Vb Inductor") (class "Default")
      (node (ref "L PMIC Buck3") (pin "1") (pinfunction "1_1") (pintype "passive"))
      (node (ref "PMIC") (pin "27") (pinfunction "LX_B3_27") (pintype "passive"))
    )
    (net (code "8") (name "/1.8V ClockGenerator") (class "Default")
      (node (ref "C 1.8V ClockBuffer") (pin "2") (pinfunction "2_2") (pintype "passive"))
      (node (ref "C 1.8V Crystal") (pin "2") (pinfunction "2_2") (pintype "passive"))
      (node (ref "ClockBuffer") (pin "2") (pinfunction "1G_2") (pintype "passive"))
      (node (ref "ClockBuffer") (pin "6") (pinfunction "VDD_6") (pintype "passive"))
      (node (ref "F 1.8V Crystal") (pin "2") (pinfunction "2_2") (pintype "passive"))
      (node (ref "X") (pin "4") (pinfunction "VDD_4") (pintype "passive"))
    )
    (net (code "9") (name "/1.8V MCU") (class "Default")
      (node (ref "AM6442") (pin "K12") (pinfunction "VDDA_MCU_K12") (pintype "passive"))
      (node (ref "C 1.8V MCU") (pin "2") (pinfunction "2_2") (pintype "passive"))
      (node (ref "C 1.8V MCU 1uF") (pin "2") (pinfunction "2_2") (pintype "passive"))
      (node (ref "F 1.8V MCU") (pin "2") (pinfunction "2_2") (pintype "passive"))
    )
    (net (code "10") (name "/1.8V MMC0") (class "Default")
      (node (ref "AM6442") (pin "K14") (pinfunction "VDDS_MMC0_K14") (pintype "passive"))
      (node (ref "C 1.8V MMC0") (pin "2") (pinfunction "2_2") (pintype "passive"))
      (node (ref "C 1.8V MMC0 1uF") (pin "2") (pinfunction "2_2") (pintype "passive"))
      (node (ref "F 1.8V MMC0") (pin "2") (pinfunction "2_2") (pintype "passive"))
    )
    (net (code "11") (name "/1.8V PLL0") (class "Default")
      (node (ref "AM6442") (pin "N12") (pinfunction "VDDA_PLL0_N12") (pintype "passive"))
      (node (ref "C 1.8V PLL0") (pin "2") (pinfunction "2_2") (pintype "passive"))
      (node (ref "C 1.8V PLL0 1uF") (pin "2") (pinfunction "2_2") (pintype "passive"))
      (node (ref "F 1.8V PLL0") (pin "2") (pinfunction "2_2") (pintype "passive"))
    )
    (net (code "12") (name "/1.8V PLL1") (class "Default")
      (node (ref "AM6442") (pin "H9") (pinfunction "VDDA_PLL1_H9") (pintype "passive"))
      (node (ref "C 1.8V PLL1") (pin "2") (pinfunction "2_2") (pintype "passive"))
      (node (ref "C 1.8V PLL1 1uF") (pin "2") (pinfunction "2_2") (pintype "passive"))
      (node (ref "F 1.8V PLL1") (pin "2") (pinfunction "2_2") (pintype "passive"))
    )
    (net (code "13") (name "/1.8V PLL2") (class "Default")
      (node (ref "AM6442") (pin "J11") (pinfunction "VDDA_PLL2_J11") (pintype "passive"))
      (node (ref "C 1.8V PLL2") (pin "2") (pinfunction "2_2") (pintype "passive"))
      (node (ref "C 1.8V PLL2 1uF") (pin "2") (pinfunction "2_2") (pintype "passive"))
      (node (ref "F 1.8V PLL2") (pin "2") (pinfunction "2_2") (pintype "passive"))
    )
    (net (code "14") (name "/1.8V SERDES") (class "Default")
      (node (ref "AM6442") (pin "R14") (pinfunction "VDDA_1P8_SERDES_R14") (pintype "passive"))
      (node (ref "C 1.8V SERDES") (pin "2") (pinfunction "2_2") (pintype "passive"))
      (node (ref "C 1.8V SERDES 1uF") (pin "2") (pinfunction "2_2") (pintype "passive"))
      (node (ref "F 1.8V SERDES") (pin "2") (pinfunction "2_2") (pintype "passive"))
    )
    (net (code "15") (name "/1.8V USB") (class "Default")
      (node (ref "AM6442") (pin "R15") (pinfunction "VDDA_1P8_USB_R15") (pintype "passive"))
      (node (ref "C 1.8V USB") (pin "2") (pinfunction "2_2") (pintype "passive"))
      (node (ref "C 1.8V USB 1uF") (pin "2") (pinfunction "2_2") (pintype "passive"))
      (node (ref "F 1.8V USB") (pin "2") (pinfunction "2_2") (pintype "passive"))
    )
    (net (code "16") (name "/1.8Vb Inductor") (class "Default")
      (node (ref "L PMIC Buck2") (pin "1") (pinfunction "1_1") (pintype "passive"))
      (node (ref "PMIC") (pin "29") (pinfunction "LX_B2_29") (pintype "passive"))
    )
    (net (code "17") (name "/BuckMain3.3V Feedback") (class "Default")
      (node (ref "BuckMain") (pin "5") (pinfunction "FB_5") (pintype "passive"))
      (node (ref "C BuckMain Feedback") (pin "2") (pinfunction "2_2") (pintype "passive"))
      (node (ref "R BuckMain Divider1") (pin "1") (pinfunction "1_1") (pintype "passive"))
      (node (ref "R BuckMain Divider3") (pin "1") (pinfunction "1_1") (pintype "passive"))
    )
    (net (code "18") (name "/BuckMain3.3V OUT") (class "Default")
      (node (ref "BuckMain") (pin "2") (pinfunction "SW_2") (pintype "passive"))
      (node (ref "L BuckMain") (pin "1") (pinfunction "1_1") (pintype "passive"))
    )
    (net (code "19") (name "/CAP VDDS0") (class "Default")
      (node (ref "AM6442") (pin "H12") (pinfunction "CAP_VDDS0_H12") (pintype "passive"))
      (node (ref "C AM6442 CAP VDDS0") (pin "1") (pinfunction "1_1") (pintype "passive"))
    )
    (net (code "20") (name "/CAP VDDS1") (class "Default")
      (node (ref "AM6442") (pin "T7") (pinfunction "CAP_VDDS1C_T7") (pintype "passive"))
      (node (ref "C AM6442 CAP VDDS1") (pin "1") (pinfunction "1_1") (pintype "passive"))
    )
    (net (code "21") (name "/CAP VDDS2") (class "Default")
      (node (ref "AM6442") (pin "R11") (pinfunction "CAP_VDDS2_R11") (pintype "passive"))
      (node (ref "C AM6442 CAP VDDS2") (pin "1") (pinfunction "1_1") (pintype "passive"))
    )
    (net (code "22") (name "/CAP VDDS3") (class "Default")
      (node (ref "AM6442") (pin "N14") (pinfunction "CAP_VDDS3_N14") (pintype "passive"))
      (node (ref "C AM6442 CAP VDDS3") (pin "1") (pinfunction "1_1") (pintype "passive"))
    )
    (net (code "23") (name "/CAP VDDS4") (class "Default")
      (node (ref "AM6442") (pin "M16") (pinfunction "CAP_VDDS4_M16") (pintype "passive"))
      (node (ref "C AM6442 CAP VDDS4") (pin "1") (pinfunction "1_1") (pintype "passive"))
    )
    (net (code "24") (name "/CAP VDDS_MCU") (class "Default")
      (node (ref "AM6442") (pin "H10") (pinfunction "CAP_VDDS_MCU_H10") (pintype "passive"))
      (node (ref "C AM6442 CAP VDDS_MCU") (pin "1") (pinfunction "1_1") (pintype "passive"))
    )
    (net (code "25") (name "/CAP VDDS_MMC") (class "Default")
      (node (ref "AM6442") (pin "K15") (pinfunction "CAP_VDDSHV_MMC1_K15") (pintype "passive"))
      (node (ref "C AM6442 CAP VDDS_MMC") (pin "1") (pinfunction "1_1") (pintype "passive"))
    )
    (net (code "26") (name "/CrystalClock") (class "Default")
      (node (ref "ClockBuffer") (pin "1") (pinfunction "CLKIN_1") (pintype "passive"))
      (node (ref "X") (pin "3") (pinfunction "OUTPUT_3") (pintype "passive"))
    )
    (net (code "27") (name "/DDR_A0") (class "Default")
      (node (ref "AM6442") (pin "D2") (pinfunction "DDR0_A0_D2") (pintype "passive"))
      (node (ref "LPDDR4") (pin "H2") (pinfunction "CA0_A_H2") (pintype "passive"))
    )
    (net (code "28") (name "/DDR_A1") (class "Default")
      (node (ref "AM6442") (pin "C5") (pinfunction "DDR0_A1_C5") (pintype "passive"))
      (node (ref "LPDDR4") (pin "J2") (pinfunction "CA1_A_J2") (pintype "passive"))
    )
    (net (code "29") (name "/DDR_A2") (class "Default")
      (node (ref "AM6442") (pin "E2") (pinfunction "DDR0_A2_E2") (pintype "passive"))
      (node (ref "LPDDR4") (pin "H9") (pinfunction "CA2_A_H9") (pintype "passive"))
    )
    (net (code "30") (name "/DDR_A3") (class "Default")
      (node (ref "AM6442") (pin "D4") (pinfunction "DDR0_A3_D4") (pintype "passive"))
      (node (ref "LPDDR4") (pin "H10") (pinfunction "CA3_A_H10") (pintype "passive"))
    )
    (net (code "31") (name "/DDR_A4") (class "Default")
      (node (ref "AM6442") (pin "D3") (pinfunction "DDR0_A4_D3") (pintype "passive"))
      (node (ref "LPDDR4") (pin "H11") (pinfunction "CA4_A_H11") (pintype "passive"))
    )
    (net (code "32") (name "/DDR_A5") (class "Default")
      (node (ref "AM6442") (pin "F2") (pinfunction "DDR0_A5_F2") (pintype "passive"))
      (node (ref "LPDDR4") (pin "J11") (pinfunction "CA5_A_J11") (pintype "passive"))
    )
    (net (code "33") (name "/DDR_CAL") (class "Default")
      (node (ref "AM6442") (pin "H5") (pinfunction "DDR0_CAL0_H5") (pintype "passive"))
      (node (ref "R DDR CAL") (pin "2") (pinfunction "2_2") (pintype "passive"))
    )
    (net (code "34") (name "/DDR_CK0_N") (class "Default")
      (node (ref "AM6442") (pin "E1") (pinfunction "DDR0_CK0_N_E1") (pintype "passive"))
      (node (ref "LPDDR4") (pin "J9") (pinfunction "CK_C_A_J9") (pintype "passive"))
    )
    (net (code "35") (name "/DDR_CK0_P") (class "Default")
      (node (ref "AM6442") (pin "F1") (pinfunction "DDR0_CK0_P_F1") (pintype "passive"))
      (node (ref "LPDDR4") (pin "J8") (pinfunction "CK_T_A_J8") (pintype "passive"))
    )
    (net (code "36") (name "/DDR_CKE") (class "Default")
      (node (ref "AM6442") (pin "F4") (pinfunction "DDR0_CKE0_F4") (pintype "passive"))
      (node (ref "LPDDR4") (pin "J4") (pinfunction "CKE0_A_J4") (pintype "passive"))
    )
    (net (code "37") (name "/DDR_CS") (class "Default")
      (node (ref "AM6442") (pin "E3") (pinfunction "DDR0_CS0_N_E3") (pintype "passive"))
      (node (ref "LPDDR4") (pin "H4") (pinfunction "CS0_A_H4") (pintype "passive"))
    )
    (net (code "38") (name "/DDR_DM0") (class "Default")
      (node (ref "AM6442") (pin "B2") (pinfunction "DDR0_DM0_B2") (pintype "passive"))
      (node (ref "LPDDR4") (pin "C3") (pinfunction "DMI0_A_C3") (pintype "passive"))
    )
    (net (code "39") (name "/DDR_DM1") (class "Default")
      (node (ref "AM6442") (pin "M2") (pinfunction "DDR0_DM1_M2") (pintype "passive"))
      (node (ref "LPDDR4") (pin "C10") (pinfunction "DMI1_A_C10") (pintype "passive"))
    )
    (net (code "40") (name "/DDR_DQ0") (class "Default")
      (node (ref "AM6442") (pin "A3") (pinfunction "DDR0_DQ0_A3") (pintype "passive"))
      (node (ref "LPDDR4") (pin "B2") (pinfunction "DQ0_A_B2") (pintype "passive"))
    )
    (net (code "41") (name "/DDR_DQ1") (class "Default")
      (node (ref "AM6442") (pin "A2") (pinfunction "DDR0_DQ1_A2") (pintype "passive"))
      (node (ref "LPDDR4") (pin "C2") (pinfunction "DQ1_A_C2") (pintype "passive"))
    )
    (net (code "42") (name "/DDR_DQ2") (class "Default")
      (node (ref "AM6442") (pin "B5") (pinfunction "DDR0_DQ2_B5") (pintype "passive"))
      (node (ref "LPDDR4") (pin "E2") (pinfunction "DQ2_A_E2") (pintype "passive"))
    )
    (net (code "43") (name "/DDR_DQ3") (class "Default")
      (node (ref "AM6442") (pin "A4") (pinfunction "DDR0_DQ3_A4") (pintype "passive"))
      (node (ref "LPDDR4") (pin "F2") (pinfunction "DQ3_A_F2") (pintype "passive"))
    )
    (net (code "44") (name "/DDR_DQ4") (class "Default")
      (node (ref "AM6442") (pin "B3") (pinfunction "DDR0_DQ4_B3") (pintype "passive"))
      (node (ref "LPDDR4") (pin "F4") (pinfunction "DQ4_A_F4") (pintype "passive"))
    )
    (net (code "45") (name "/DDR_DQ5") (class "Default")
      (node (ref "AM6442") (pin "C4") (pinfunction "DDR0_DQ5_C4") (pintype "passive"))
      (node (ref "LPDDR4") (pin "E4") (pinfunction "DQ5_A_E4") (pintype "passive"))
    )
    (net (code "46") (name "/DDR_DQ6") (class "Default")
      (node (ref "AM6442") (pin "C2") (pinfunction "DDR0_DQ6_C2") (pintype "passive"))
      (node (ref "LPDDR4") (pin "C4") (pinfunction "DQ6_A_C4") (pintype "passive"))
    )
    (net (code "47") (name "/DDR_DQ7") (class "Default")
      (node (ref "AM6442") (pin "B4") (pinfunction "DDR0_DQ7_B4") (pintype "passive"))
      (node (ref "LPDDR4") (pin "B4") (pinfunction "DQ7_A_B4") (pintype "passive"))
    )
    (net (code "48") (name "/DDR_DQ8") (class "Default")
      (node (ref "AM6442") (pin "N5") (pinfunction "DDR0_DQ8_N5") (pintype "passive"))
      (node (ref "LPDDR4") (pin "B11") (pinfunction "DQ8_A_B11") (pintype "passive"))
    )
    (net (code "49") (name "/DDR_DQ9") (class "Default")
      (node (ref "AM6442") (pin "L4") (pinfunction "DDR0_DQ9_L4") (pintype "passive"))
      (node (ref "LPDDR4") (pin "C11") (pinfunction "DQ9_A_C11") (pintype "passive"))
    )
    (net (code "50") (name "/DDR_DQ10") (class "Default")
      (node (ref "AM6442") (pin "L2") (pinfunction "DDR0_DQ10_L2") (pintype "passive"))
      (node (ref "LPDDR4") (pin "E11") (pinfunction "DQ10_A_E11") (pintype "passive"))
    )
    (net (code "51") (name "/DDR_DQ11") (class "Default")
      (node (ref "AM6442") (pin "M3") (pinfunction "DDR0_DQ11_M3") (pintype "passive"))
      (node (ref "LPDDR4") (pin "F11") (pinfunction "DQ11_A_F11") (pintype "passive"))
    )
    (net (code "52") (name "/DDR_DQ12") (class "Default")
      (node (ref "AM6442") (pin "N4") (pinfunction "DDR0_DQ12_N4") (pintype "passive"))
      (node (ref "LPDDR4") (pin "F9") (pinfunction "DQ12_A_F9") (pintype "passive"))
    )
    (net (code "53") (name "/DDR_DQ13") (class "Default")
      (node (ref "AM6442") (pin "N3") (pinfunction "DDR0_DQ13_N3") (pintype "passive"))
      (node (ref "LPDDR4") (pin "E9") (pinfunction "DQ13_A_E9") (pintype "passive"))
    )
    (net (code "54") (name "/DDR_DQ14") (class "Default")
      (node (ref "AM6442") (pin "M4") (pinfunction "DDR0_DQ14_M4") (pintype "passive"))
      (node (ref "LPDDR4") (pin "C9") (pinfunction "DQ14_A_C9") (pintype "passive"))
    )
    (net (code "55") (name "/DDR_DQ15") (class "Default")
      (node (ref "AM6442") (pin "N2") (pinfunction "DDR0_DQ15_N2") (pintype "passive"))
      (node (ref "LPDDR4") (pin "B9") (pinfunction "DQ15_A_B9") (pintype "passive"))
    )
    (net (code "56") (name "/DDR_DQS0_N") (class "Default")
      (node (ref "AM6442") (pin "B1") (pinfunction "DDR0_DQS0_N_B1") (pintype "passive"))
      (node (ref "LPDDR4") (pin "E3") (pinfunction "DQS0_C_A_E3") (pintype "passive"))
    )
    (net (code "57") (name "/DDR_DQS0_P") (class "Default")
      (node (ref "AM6442") (pin "C1") (pinfunction "DDR0_DQS0_P_C1") (pintype "passive"))
      (node (ref "LPDDR4") (pin "D3") (pinfunction "DQS0_T_A_D3") (pintype "passive"))
    )
    (net (code "58") (name "/DDR_DQS1_N") (class "Default")
      (node (ref "AM6442") (pin "M1") (pinfunction "DDR0_DQS1_N_M1") (pintype "passive"))
      (node (ref "LPDDR4") (pin "E10") (pinfunction "DQS1_C_A_E10") (pintype "passive"))
    )
    (net (code "59") (name "/DDR_DQS1_P") (class "Default")
      (node (ref "AM6442") (pin "N1") (pinfunction "DDR0_DQS1_P_N1") (pintype "passive"))
      (node (ref "LPDDR4") (pin "D10") (pinfunction "DQS1_T_A_D10") (pintype "passive"))
    )
    (net (code "60") (name "/DDR_ODT_CA") (class "Default")
      (node (ref "LPDDR4") (pin "G2") (pinfunction "ODT(CA)_A_G2") (pintype "passive"))
      (node (ref "R DDR ODTCA") (pin "1") (pinfunction "1_1") (pintype "passive"))
    )
    (net (code "61") (name "/DDR_RESET") (class "Default")
      (node (ref "AM6442") (pin "D5") (pinfunction "DDR0_RESET0_N_D5") (pintype "passive"))
      (node (ref "LPDDR4") (pin "T11") (pinfunction "RESET_N_T11") (pintype "passive"))
      (node (ref "R DDR RESET") (pin "1") (pinfunction "1_1") (pintype "passive"))
    )
    (net (code "62") (name "/DDR_ZQ") (class "Default")
      (node (ref "LPDDR4") (pin "A5") (pinfunction "ZQ0_A5") (pintype "passive"))
      (node (ref "R DDR ZQ") (pin "1") (pinfunction "1_1") (pintype "passive"))
    )
    (net (code "63") (name "/Ethernet D0+") (class "Default")
      (node (ref "DP83867IRRGZR") (pin "1") (pinfunction "TD_P_A_1") (pintype "passive"))
      (node (ref "MagJack0") (pin "P1") (pinfunction "TRD0+_P1") (pintype "passive"))
    )
    (net (code "64") (name "/Ethernet D0-") (class "Default")
      (node (ref "DP83867IRRGZR") (pin "2") (pinfunction "TD_M_A_2") (pintype "passive"))
      (node (ref "MagJack0") (pin "P2") (pinfunction "TRD0-_P2") (pintype "passive"))
    )
    (net (code "65") (name "/Ethernet D1+") (class "Default")
      (node (ref "DP83867IRRGZR") (pin "4") (pinfunction "TD_P_B_4") (pintype "passive"))
      (node (ref "MagJack0") (pin "P3") (pinfunction "TRD1+_P3") (pintype "passive"))
    )
    (net (code "66") (name "/Ethernet D1-") (class "Default")
      (node (ref "DP83867IRRGZR") (pin "5") (pinfunction "TD_M_B_5") (pintype "passive"))
      (node (ref "MagJack0") (pin "P4") (pinfunction "TRD1-_P4") (pintype "passive"))
    )
    (net (code "67") (name "/Ethernet D2+") (class "Default")
      (node (ref "DP83867IRRGZR") (pin "7") (pinfunction "TD_P_C_7") (pintype "passive"))
      (node (ref "MagJack0") (pin "P7") (pinfunction "TRD2+_P7") (pintype "passive"))
    )
    (net (code "68") (name "/Ethernet D2-") (class "Default")
      (node (ref "DP83867IRRGZR") (pin "8") (pinfunction "TD_M_C_8") (pintype "passive"))
      (node (ref "MagJack0") (pin "P8") (pinfunction "TRD2-_P8") (pintype "passive"))
    )
    (net (code "69") (name "/Ethernet D3+") (class "Default")
      (node (ref "DP83867IRRGZR") (pin "10") (pinfunction "TD_P_D_10") (pintype "passive"))
      (node (ref "MagJack0") (pin "P9") (pinfunction "TRD3+_P9") (pintype "passive"))
    )
    (net (code "70") (name "/Ethernet D3-") (class "Default")
      (node (ref "DP83867IRRGZR") (pin "11") (pinfunction "TD_M_D_11") (pintype "passive"))
      (node (ref "MagJack0") (pin "P10") (pinfunction "TRD3-_P10") (pintype "passive"))
    )
    (net (code "71") (name "/JTAG EM1") (class "Default")
      (node (ref "AM6442") (pin "E10") (pinfunction "EMU1_E10") (pintype "passive+no_connect"))
    )
    (net (code "72") (name "/JTAG EMU0") (class "Default")
      (node (ref "AM6442") (pin "D10") (pinfunction "EMU0_D10") (pintype "passive+no_connect"))
    )
    (net (code "73") (name "/JTAG RST") (class "Default")
      (node (ref "AM6442") (pin "D11") (pinfunction "TRSTN_D11") (pintype "passive+no_connect"))
    )
    (net (code "74") (name "/JTAG TCK") (class "Default")
      (node (ref "AM6442") (pin "B11") (pinfunction "TCK_B11") (pintype "passive+no_connect"))
    )
    (net (code "75") (name "/JTAG TDI") (class "Default")
      (node (ref "AM6442") (pin "C11") (pinfunction "TDI_C11") (pintype "passive+no_connect"))
    )
    (net (code "76") (name "/JTAG TDO") (class "Default")
      (node (ref "AM6442") (pin "A12") (pinfunction "TDO_A12") (pintype "passive+no_connect"))
    )
    (net (code "77") (name "/JTAG TMS") (class "Default")
      (node (ref "AM6442") (pin "C12") (pinfunction "TMS_C12") (pintype "passive+no_connect"))
    )
    (net (code "78") (name "/MMC CLK") (class "Default")
      (node (ref "AM6442") (pin "G18") (pinfunction "MMC0_CLK_G18") (pintype "passive"))
      (node (ref "CONSD") (pin "3") (pinfunction "CMD_3") (pintype "passive"))
    )
    (net (code "79") (name "/MMC CMD") (class "Default")
      (node (ref "AM6442") (pin "J21") (pinfunction "MMC0_CMD_J21") (pintype "passive"))
      (node (ref "CONSD") (pin "5") (pinfunction "CLK_5") (pintype "passive"))
    )
    (net (code "80") (name "/MMC D0") (class "Default")
      (node (ref "AM6442") (pin "K20") (pinfunction "MMC0_DAT0_K20") (pintype "passive"))
      (node (ref "CONSD") (pin "7") (pinfunction "DAT0_7") (pintype "passive"))
    )
    (net (code "81") (name "/MMC D1") (class "Default")
      (node (ref "AM6442") (pin "J20") (pinfunction "MMC0_DAT1_J20") (pintype "passive"))
      (node (ref "CONSD") (pin "8") (pinfunction "DAT1_8") (pintype "passive"))
    )
    (net (code "82") (name "/MMC D2") (class "Default")
      (node (ref "AM6442") (pin "J18") (pinfunction "MMC0_DAT2_J18") (pintype "passive"))
      (node (ref "CONSD") (pin "1") (pinfunction "DAT2_1") (pintype "passive"))
    )
    (net (code "83") (name "/MMC D3") (class "Default")
      (node (ref "AM6442") (pin "J17") (pinfunction "MMC0_DAT3_J17") (pintype "passive"))
      (node (ref "CONSD") (pin "2") (pinfunction "DAT3/CD_2") (pintype "passive"))
    )
    (net (code "84") (name "/PMIC 3.3V Switch Enable") (class "Default")
      (node (ref "PMIC") (pin "17") (pinfunction "GPO2_17") (pintype "passive"))
      (node (ref "Switch3.3V") (pin "4") (pinfunction "ON_4") (pintype "passive"))
    )
    (net (code "85") (name "/PMIC Enable") (class "Default")
      (node (ref "BergStrip PMICEnable") (pin "1") (pinfunction "Pin_1") (pintype "passive"))
      (node (ref "PMIC") (pin "25") (pinfunction "EN/PB/VSENSE_25") (pintype "passive"))
    )
    (net (code "86") (name "/PMIC Internal Bypass") (class "Default")
      (node (ref "C PMIC InternalBypass") (pin "2") (pinfunction "2_2") (pintype "passive"))
      (node (ref "PMIC") (pin "14") (pinfunction "VDD1P8_14") (pintype "passive"))
    )
    (net (code "87") (name "/PMIC SD Voltage Select") (class "Default")
      (node (ref "AM6442") (pin "B7") (pinfunction "MCU_SPI1__CS1_B7") (pintype "passive"))
      (node (ref "PMIC") (pin "12") (pinfunction "VSEL_SD/VSEL_DDR_12") (pintype "passive"))
      (node (ref "R PMIC SDPullup") (pin "1") (pinfunction "1_1") (pintype "passive"))
    )
    (net (code "88") (name "/RGMII MDC") (class "Default")
      (node (ref "AM6442") (pin "Y6") (pinfunction "PRG1__MDIO__MDC_Y6") (pintype "passive"))
      (node (ref "DP83867IRRGZR") (pin "16") (pinfunction "MDC_16") (pintype "passive"))
    )
    (net (code "89") (name "/RGMII MDIO") (class "Default")
      (node (ref "AM6442") (pin "AA6") (pinfunction "PRG1__MDIO__MDI_AA6") (pintype "passive"))
      (node (ref "DP83867IRRGZR") (pin "17") (pinfunction "MDIO_17") (pintype "passive"))
    )
    (net (code "90") (name "/RGMII RD0") (class "Default")
      (node (ref "AM6442") (pin "AA13") (pinfunction "PRG1_PRU1__GPO5_AA13") (pintype "passive"))
      (node (ref "DP83867IRRGZR") (pin "33") (pinfunction "RX_D0_33") (pintype "passive"))
    )
    (net (code "91") (name "/RGMII RD1") (class "Default")
      (node (ref "AM6442") (pin "U12") (pinfunction "PRG1_PRU1__GPO8_U12") (pintype "passive"))
      (node (ref "DP83867IRRGZR") (pin "34") (pinfunction "RX_D1_34") (pintype "passive"))
    )
    (net (code "92") (name "/RGMII RD2") (class "Default")
      (node (ref "AM6442") (pin "Y13") (pinfunction "PRG1_PRU1__GPO18_Y13") (pintype "passive"))
      (node (ref "DP83867IRRGZR") (pin "35") (pinfunction "RX_D2_35") (pintype "passive"))
    )
    (net (code "93") (name "/RGMII RD3") (class "Default")
      (node (ref "AM6442") (pin "V12") (pinfunction "PRG1_PRU1__GPO19_V12") (pintype "passive"))
      (node (ref "DP83867IRRGZR") (pin "36") (pinfunction "RX_D3_36") (pintype "passive"))
    )
    (net (code "94") (name "/RGMII RXC") (class "Default")
      (node (ref "AM6442") (pin "W13") (pinfunction "PRG1_PRU0__GPO8_W13") (pintype "passive"))
      (node (ref "DP83867IRRGZR") (pin "32") (pinfunction "RX_CLK_32") (pintype "passive"))
    )
    (net (code "95") (name "/RGMII RX_CTL") (class "Default")
      (node (ref "AM6442") (pin "V13") (pinfunction "PRG1_PRU0__GPO5_V13") (pintype "passive"))
      (node (ref "DP83867IRRGZR") (pin "38") (pinfunction "RX_DV_RX_CTRL_38") (pintype "passive"))
    )
    (net (code "96") (name "/RGMII TD0") (class "Default")
      (node (ref "AM6442") (pin "V15") (pinfunction "PRG1_PRU1__GPO7_V15") (pintype "passive"))
      (node (ref "DP83867IRRGZR") (pin "28") (pinfunction "TX_D0_28") (pintype "passive"))
    )
    (net (code "97") (name "/RGMII TD1") (class "Default")
      (node (ref "AM6442") (pin "V14") (pinfunction "PRG1_PRU1__GPO9_V14") (pintype "passive"))
      (node (ref "DP83867IRRGZR") (pin "27") (pinfunction "TX_D1_27") (pintype "passive"))
    )
    (net (code "98") (name "/RGMII TD2") (class "Default")
      (node (ref "AM6442") (pin "W14") (pinfunction "PRG1_PRU1__GPO10_W14") (pintype "passive"))
      (node (ref "DP83867IRRGZR") (pin "26") (pinfunction "TX_D2_26") (pintype "passive"))
    )
    (net (code "99") (name "/RGMII TD3") (class "Default")
      (node (ref "AM6442") (pin "AA14") (pinfunction "PRG1_PRU1__GPO17_AA14") (pintype "passive"))
      (node (ref "DP83867IRRGZR") (pin "25") (pinfunction "TX_D3_25") (pintype "passive"))
    )
    (net (code "100") (name "/RGMII TXC") (class "Default")
      (node (ref "AM6442") (pin "U14") (pinfunction "PRG1_PRU0__GPO10_U14") (pintype "passive"))
      (node (ref "DP83867IRRGZR") (pin "29") (pinfunction "GTX_CLK_29") (pintype "passive"))
    )
    (net (code "101") (name "/RGMII TX_CTL") (class "Default")
      (node (ref "AM6442") (pin "U15") (pinfunction "PRG1_PRU0__GPO9_U15") (pintype "passive"))
      (node (ref "DP83867IRRGZR") (pin "37") (pinfunction "TX_EN_TX_CTRL_37") (pintype "passive"))
    )
    (net (code "102") (name "/Reset Cold") (class "Default")
      (node (ref "AM6442") (pin "B21") (pinfunction "MCU_PORZ(Cold_Reset)_B21") (pintype "passive+no_connect"))
    )
    (net (code "103") (name "/Reset Warm") (class "Default")
      (node (ref "AM6442") (pin "B12") (pinfunction "MCU_RESETZ(Warm_Reset)_B12") (pintype "passive"))
      (node (ref "AM6442") (pin "E18") (pinfunction "RESET__REQ(Warm_Reset)_E18") (pintype "passive"))
    )
    (net (code "104") (name "/VMON_VSYS") (class "Default")
      (node (ref "R VMON 1") (pin "1") (pinfunction "1_1") (pintype "passive"))
      (node (ref "R VMON 2") (pin "2") (pinfunction "2_2") (pintype "passive"))
    )
    (net (code "105") (name "/X 25Mhz AM6442") (class "Default")
      (node (ref "AM6442") (pin "C21") (pinfunction "MCU_OSC0__XI_C21") (pintype "passive"))
      (node (ref "ClockBuffer") (pin "3") (pinfunction "Y0_3") (pintype "passive"))
    )
    (net (code "106") (name "/X 25Mhz DP83867") (class "Default")
      (node (ref "ClockBuffer") (pin "8") (pinfunction "Y1_8") (pintype "passive"))
      (node (ref "DP83867IRRGZR") (pin "15") (pinfunction "X_I_15") (pintype "passive"))
    )
    (net (code "107") (name "/X 25Mhz TestPoint1") (class "Default")
      (node (ref "ClockBuffer") (pin "5") (pinfunction "Y2_5") (pintype "passive+no_connect"))
    )
    (net (code "108") (name "/X 25Mhz TestPoint2") (class "Default")
      (node (ref "ClockBuffer") (pin "7") (pinfunction "Y3_7") (pintype "passive+no_connect"))
    )
    (net (code "109") (name "0.75Vb") (class "Default")
      (node (ref "AM6442") (pin "J10") (pinfunction "VDD_CORE_1_J10") (pintype "passive"))
      (node (ref "AM6442") (pin "J12") (pinfunction "VDD_CORE_2_J12") (pintype "passive"))
      (node (ref "AM6442") (pin "K11") (pinfunction "VDD_CORE_4_K11") (pintype "passive"))
      (node (ref "AM6442") (pin "K9") (pinfunction "VDD_CORE_3_K9") (pintype "passive"))
      (node (ref "AM6442") (pin "L12") (pinfunction "VDD_CORE_6_L12") (pintype "passive"))
      (node (ref "AM6442") (pin "L8") (pinfunction "VDD_CORE_5_L8") (pintype "passive"))
      (node (ref "AM6442") (pin "M11") (pinfunction "VDD_CORE_8_M11") (pintype "passive"))
      (node (ref "AM6442") (pin "M9") (pinfunction "VDD_CORE_7_M9") (pintype "passive"))
      (node (ref "AM6442") (pin "N10") (pinfunction "VDD_CORE_10_N10") (pintype "passive"))
      (node (ref "AM6442") (pin "N8") (pinfunction "VDD_CORE_9_N8") (pintype "passive"))
      (node (ref "AM6442") (pin "P9") (pinfunction "VDD_CORE_11_P9") (pintype "passive"))
      (node (ref "C 0.75V 1uF") (pin "1") (pinfunction "1_1") (pintype "passive"))
      (node (ref "C 0.75V 47uF") (pin "1") (pinfunction "1_1") (pintype "passive"))
      (node (ref "C 0.75V Core1") (pin "1") (pinfunction "1_1") (pintype "passive"))
      (node (ref "C 0.75V Core10") (pin "1") (pinfunction "1_1") (pintype "passive"))
      (node (ref "C 0.75V Core11") (pin "1") (pinfunction "1_1") (pintype "passive"))
      (node (ref "C 0.75V Core2") (pin "1") (pinfunction "1_1") (pintype "passive"))
      (node (ref "C 0.75V Core3") (pin "1") (pinfunction "1_1") (pintype "passive"))
      (node (ref "C 0.75V Core4") (pin "1") (pinfunction "1_1") (pintype "passive"))
      (node (ref "C 0.75V Core5") (pin "1") (pinfunction "1_1") (pintype "passive"))
      (node (ref "C 0.75V Core6") (pin "1") (pinfunction "1_1") (pintype "passive"))
      (node (ref "C 0.75V Core7") (pin "1") (pinfunction "1_1") (pintype "passive"))
      (node (ref "C 0.75V Core8") (pin "1") (pinfunction "1_1") (pintype "passive"))
      (node (ref "C 0.75V Core9") (pin "1") (pinfunction "1_1") (pintype "passive"))
      (node (ref "C PMIC 0.75V") (pin "2") (pinfunction "2_2") (pintype "passive"))
      (node (ref "L PMIC Buck1") (pin "2") (pinfunction "2_2") (pintype "passive"))
      (node (ref "PMIC") (pin "1") (pinfunction "FB_B1_1") (pintype "passive"))
    )
    (net (code "110") (name "0.85V") (class "Default")
      (node (ref "C PMIC 0.85V") (pin "2") (pinfunction "2_2") (pintype "passive"))
      (node (ref "PMIC") (pin "19") (pinfunction "VLDO2_19") (pintype "passive"))
    )
    (net (code "111") (name "0.85Vb") (class "Default")
      (node (ref "AM6442") (pin "L10") (pinfunction "VDDR_CORE_1_L10") (pintype "passive"))
      (node (ref "AM6442") (pin "M13") (pinfunction "VDDR_CORE_2_M13") (pintype "passive"))
      (node (ref "C 0.85V 1uF") (pin "1") (pinfunction "1_1") (pintype "passive"))
      (node (ref "C 0.85V 4.7uF") (pin "1") (pinfunction "1_1") (pintype "passive"))
      (node (ref "C 0.85V Core1") (pin "2") (pinfunction "2_2") (pintype "passive"))
      (node (ref "C 0.85V Core2") (pin "2") (pinfunction "2_2") (pintype "passive"))
      (node (ref "F 0.85V MMC0") (pin "1") (pinfunction "1_1") (pintype "passive"))
      (node (ref "F 0.85V MMC0DLL") (pin "1") (pinfunction "1_1") (pintype "passive"))
      (node (ref "F 0.85V SERDES") (pin "1") (pinfunction "1_1") (pintype "passive"))
      (node (ref "F 0.85V USB") (pin "1") (pinfunction "1_1") (pintype "passive"))
    )
    (net (code "112") (name "1.1Vb") (class "Default")
      (node (ref "AM6442") (pin "F7") (pinfunction "VDDS_DDR_1_F7") (pintype "passive"))
      (node (ref "AM6442") (pin "G6") (pinfunction "VDDS_DDR_2_G6") (pintype "passive"))
      (node (ref "AM6442") (pin "H7") (pinfunction "VDDS_DDR_3_H7") (pintype "passive"))
      (node (ref "AM6442") (pin "J6") (pinfunction "VDDS_DDR_4_J6") (pintype "passive"))
      (node (ref "AM6442") (pin "J8") (pinfunction "VDDS_DDR_C_J8") (pintype "passive"))
      (node (ref "AM6442") (pin "K7") (pinfunction "VDDS_DDR_5_K7") (pintype "passive"))
      (node (ref "AM6442") (pin "L6") (pinfunction "VDDS_DDR_6_L6") (pintype "passive"))
      (node (ref "C 1.1V DDR 10uF") (pin "1") (pinfunction "1_1") (pintype "passive"))
      (node (ref "C 1.1V DDR 1uF") (pin "1") (pinfunction "1_1") (pintype "passive"))
      (node (ref "C 1.1V DDR VDD2 10uF") (pin "1") (pinfunction "1_1") (pintype "passive"))
      (node (ref "C 1.1V DDR VDDQ 10uF") (pin "1") (pinfunction "1_1") (pintype "passive"))
      (node (ref "C 1.1V DDR1") (pin "1") (pinfunction "1_1") (pintype "passive"))
      (node (ref "C 1.1V DDR10") (pin "1") (pinfunction "1_1") (pintype "passive"))
      (node (ref "C 1.1V DDR11") (pin "1") (pinfunction "1_1") (pintype "passive"))
      (node (ref "C 1.1V DDR12") (pin "1") (pinfunction "1_1") (pintype "passive"))
      (node (ref "C 1.1V DDR13") (pin "1") (pinfunction "1_1") (pintype "passive"))
      (node (ref "C 1.1V DDR14") (pin "1") (pinfunction "1_1") (pintype "passive"))
      (node (ref "C 1.1V DDR15") (pin "1") (pinfunction "1_1") (pintype "passive"))
      (node (ref "C 1.1V DDR16") (pin "1") (pinfunction "1_1") (pintype "passive"))
      (node (ref "C 1.1V DDR17") (pin "1") (pinfunction "1_1") (pintype "passive"))
      (node (ref "C 1.1V DDR18") (pin "1") (pinfunction "1_1") (pintype "passive"))
      (node (ref "C 1.1V DDR19") (pin "1") (pinfunction "1_1") (pintype "passive"))
      (node (ref "C 1.1V DDR2") (pin "1") (pinfunction "1_1") (pintype "passive"))
      (node (ref "C 1.1V DDR20") (pin "1") (pinfunction "1_1") (pintype "passive"))
      (node (ref "C 1.1V DDR21") (pin "1") (pinfunction "1_1") (pintype "passive"))
      (node (ref "C 1.1V DDR22") (pin "1") (pinfunction "1_1") (pintype "passive"))
      (node (ref "C 1.1V DDR23") (pin "1") (pinfunction "1_1") (pintype "passive"))
      (node (ref "C 1.1V DDR24") (pin "1") (pinfunction "1_1") (pintype "passive"))
      (node (ref "C 1.1V DDR25") (pin "1") (pinfunction "1_1") (pintype "passive"))
      (node (ref "C 1.1V DDR26") (pin "1") (pinfunction "1_1") (pintype "passive"))
      (node (ref "C 1.1V DDR27") (pin "1") (pinfunction "1_1") (pintype "passive"))
      (node (ref "C 1.1V DDR3") (pin "1") (pinfunction "1_1") (pintype "passive"))
      (node (ref "C 1.1V DDR4") (pin "1") (pinfunction "1_1") (pintype "passive"))
      (node (ref "C 1.1V DDR5") (pin "1") (pinfunction "1_1") (pintype "passive"))
      (node (ref "C 1.1V DDR6") (pin "1") (pinfunction "1_1") (pintype "passive"))
      (node (ref "C 1.1V DDR7") (pin "1") (pinfunction "1_1") (pintype "passive"))
      (node (ref "C 1.1V DDR8") (pin "1") (pinfunction "1_1") (pintype "passive"))
      (node (ref "C 1.1V DDR9") (pin "1") (pinfunction "1_1") (pintype "passive"))
      (node (ref "C PMIC 1.1V") (pin "2") (pinfunction "2_2") (pintype "passive"))
      (node (ref "F 1.1VV DP8386") (pin "1") (pinfunction "1_1") (pintype "passive"))
      (node (ref "L PMIC Buck3") (pin "2") (pinfunction "2_2") (pintype "passive"))
      (node (ref "LPDDR4") (pin "A4") (pinfunction "VDD2_1_A4") (pintype "passive"))
      (node (ref "LPDDR4") (pin "A9") (pinfunction "VDD2_2_A9") (pintype "passive"))
      (node (ref "LPDDR4") (pin "AA10") (pinfunction "VDDQ_20_AA10") (pintype "passive"))
      (node (ref "LPDDR4") (pin "AA3") (pinfunction "VDDQ_17_AA3") (pintype "passive"))
      (node (ref "LPDDR4") (pin "AA5") (pinfunction "VDDQ_18_AA5") (pintype "passive"))
      (node (ref "LPDDR4") (pin "AA8") (pinfunction "VDDQ_19_AA8") (pintype "passive"))
      (node (ref "LPDDR4") (pin "AB4") (pinfunction "VDD2_23_AB4") (pintype "passive"))
      (node (ref "LPDDR4") (pin "AB9") (pinfunction "VDD2_24_AB9") (pintype "passive"))
      (node (ref "LPDDR4") (pin "B10") (pinfunction "VDDQ_4_B10") (pintype "passive"))
      (node (ref "LPDDR4") (pin "B3") (pinfunction "VDDQ_1_B3") (pintype "passive"))
      (node (ref "LPDDR4") (pin "B5") (pinfunction "VDDQ_2_B5") (pintype "passive"))
      (node (ref "LPDDR4") (pin "B8") (pinfunction "VDDQ_3_B8") (pintype "passive"))
      (node (ref "LPDDR4") (pin "D1") (pinfunction "VDDQ_5_D1") (pintype "passive"))
      (node (ref "LPDDR4") (pin "D12") (pinfunction "VDDQ_8_D12") (pintype "passive"))
      (node (ref "LPDDR4") (pin "D5") (pinfunction "VDDQ_6_D5") (pintype "passive"))
      (node (ref "LPDDR4") (pin "D8") (pinfunction "VDDQ_7_D8") (pintype "passive"))
      (node (ref "LPDDR4") (pin "F10") (pinfunction "VDDQ_10_F10") (pintype "passive"))
      (node (ref "LPDDR4") (pin "F3") (pinfunction "VDDQ_9_F3") (pintype "passive"))
      (node (ref "LPDDR4") (pin "F5") (pinfunction "VDD2_3_F5") (pintype "passive"))
      (node (ref "LPDDR4") (pin "F8") (pinfunction "VDD2_4_F8") (pintype "passive"))
      (node (ref "LPDDR4") (pin "H1") (pinfunction "VDD2_5_H1") (pintype "passive"))
      (node (ref "LPDDR4") (pin "H12") (pinfunction "VDD2_8_H12") (pintype "passive"))
      (node (ref "LPDDR4") (pin "H5") (pinfunction "VDD2_6_H5") (pintype "passive"))
      (node (ref "LPDDR4") (pin "H8") (pinfunction "VDD2_7_H8") (pintype "passive"))
      (node (ref "LPDDR4") (pin "K1") (pinfunction "VDD2_9_K1") (pintype "passive"))
      (node (ref "LPDDR4") (pin "K10") (pinfunction "VDD2_11_K10") (pintype "passive"))
      (node (ref "LPDDR4") (pin "K12") (pinfunction "VDD2_12_K12") (pintype "passive"))
      (node (ref "LPDDR4") (pin "K3") (pinfunction "VDD2_10_K3") (pintype "passive"))
      (node (ref "LPDDR4") (pin "N1") (pinfunction "VDD2_13_N1") (pintype "passive"))
      (node (ref "LPDDR4") (pin "N10") (pinfunction "VDD2_15_N10") (pintype "passive"))
      (node (ref "LPDDR4") (pin "N12") (pinfunction "VDD2_16_N12") (pintype "passive"))
      (node (ref "LPDDR4") (pin "N3") (pinfunction "VDD2_14_N3") (pintype "passive"))
      (node (ref "LPDDR4") (pin "R1") (pinfunction "VDD2_17_R1") (pintype "passive"))
      (node (ref "LPDDR4") (pin "R12") (pinfunction "VDD2_20_R12") (pintype "passive"))
      (node (ref "LPDDR4") (pin "R5") (pinfunction "VDD2_18_R5") (pintype "passive"))
      (node (ref "LPDDR4") (pin "R8") (pinfunction "VDD2_19_R8") (pintype "passive"))
      (node (ref "LPDDR4") (pin "U10") (pinfunction "VDDQ_12_U10") (pintype "passive"))
      (node (ref "LPDDR4") (pin "U3") (pinfunction "VDDQ_11_U3") (pintype "passive"))
      (node (ref "LPDDR4") (pin "U5") (pinfunction "VDD2_21_U5") (pintype "passive"))
      (node (ref "LPDDR4") (pin "U8") (pinfunction "VDD2_22_U8") (pintype "passive"))
      (node (ref "LPDDR4") (pin "W1") (pinfunction "VDDQ_13_W1") (pintype "passive"))
      (node (ref "LPDDR4") (pin "W12") (pinfunction "VDDQ_16_W12") (pintype "passive"))
      (node (ref "LPDDR4") (pin "W5") (pinfunction "VDDQ_14_W5") (pintype "passive"))
      (node (ref "LPDDR4") (pin "W8") (pinfunction "VDDQ_15_W8") (pintype "passive"))
      (node (ref "PMIC") (pin "24") (pinfunction "FB_B3_24") (pintype "passive"))
      (node (ref "R DDR ODTCA") (pin "2") (pinfunction "2_2") (pintype "passive"))
      (node (ref "R DDR ZQ") (pin "2") (pinfunction "2_2") (pintype "passive"))
    )
    (net (code "113") (name "1.8V") (class "Default")
      (node (ref "C 1.8V DDR VDD1 10uF") (pin "1") (pinfunction "1_1") (pintype "passive"))
      (node (ref "C 1.8V DDR1") (pin "1") (pinfunction "1_1") (pintype "passive"))
      (node (ref "C 1.8V DDR2") (pin "1") (pinfunction "1_1") (pintype "passive"))
      (node (ref "C 1.8V DDR3") (pin "1") (pinfunction "1_1") (pintype "passive"))
      (node (ref "C 1.8V DDR4") (pin "1") (pinfunction "1_1") (pintype "passive"))
      (node (ref "C 1.8V DDR5") (pin "1") (pinfunction "1_1") (pintype "passive"))
      (node (ref "C 1.8V DDR6") (pin "1") (pinfunction "1_1") (pintype "passive"))
      (node (ref "C 1.8V DDR7") (pin "1") (pinfunction "1_1") (pintype "passive"))
      (node (ref "C 1.8V DDR8") (pin "1") (pinfunction "1_1") (pintype "passive"))
      (node (ref "C PMIC 1.8V*") (pin "2") (pinfunction "2_2") (pintype "passive"))
      (node (ref "LPDDR4") (pin "F1") (pinfunction "VDD1_1_F1") (pintype "passive"))
      (node (ref "LPDDR4") (pin "F12") (pinfunction "VDD1_2_F12") (pintype "passive"))
      (node (ref "LPDDR4") (pin "G4") (pinfunction "VDD1_3_G4") (pintype "passive"))
      (node (ref "LPDDR4") (pin "G9") (pinfunction "VDD1_4_G9") (pintype "passive"))
      (node (ref "LPDDR4") (pin "T4") (pinfunction "VDD1_5_T4") (pintype "passive"))
      (node (ref "LPDDR4") (pin "T9") (pinfunction "VDD1_6_T9") (pintype "passive"))
      (node (ref "LPDDR4") (pin "U1") (pinfunction "VDD1_7_U1") (pintype "passive"))
      (node (ref "LPDDR4") (pin "U12") (pinfunction "VDD1_8_U12") (pintype "passive"))
      (node (ref "PMIC") (pin "21") (pinfunction "VLDO3_21") (pintype "passive"))
    )
    (net (code "114") (name "1.8V ADC") (class "Default")
      (node (ref "AM6442") (pin "J13") (pinfunction "VDDA_ADC_J13") (pintype "passive"))
      (node (ref "AM6442") (pin "J15") (pinfunction "ADC0_REFP_J15") (pintype "passive"))
      (node (ref "C 1.8V ADC") (pin "2") (pinfunction "2_2") (pintype "passive"))
      (node (ref "C 1.8V ADC 1uF") (pin "2") (pinfunction "2_2") (pintype "passive"))
      (node (ref "C 1.8V ADCREF") (pin "2") (pinfunction "2_2") (pintype "passive"))
      (node (ref "F 1.8V ADC") (pin "1") (pinfunction "1_1") (pintype "passive"))
    )
    (net (code "115") (name "1.8Vb") (class "Default")
      (node (ref "AM6442") (pin "G11") (pinfunction "VDDA_TEMP0_G11") (pintype "passive"))
      (node (ref "AM6442") (pin "H13") (pinfunction "VDDS_OSC_H13") (pintype "passive"))
      (node (ref "AM6442") (pin "L11") (pinfunction "VDDA_TEMP1_L11") (pintype "passive"))
      (node (ref "C 1.8V OSC") (pin "2") (pinfunction "2_2") (pintype "passive"))
      (node (ref "C 1.8V OSC 1uF") (pin "2") (pinfunction "2_2") (pintype "passive"))
      (node (ref "C PMIC 1.8V") (pin "2") (pinfunction "2_2") (pintype "passive"))
      (node (ref "C PMIC VIN LDO2") (pin "2") (pinfunction "2_2") (pintype "passive"))
      (node (ref "F 1.8V ADC") (pin "2") (pinfunction "2_2") (pintype "passive"))
      (node (ref "F 1.8V Crystal") (pin "1") (pinfunction "1_1") (pintype "passive"))
      (node (ref "F 1.8V MCU") (pin "1") (pinfunction "1_1") (pintype "passive"))
      (node (ref "F 1.8V MMC0") (pin "1") (pinfunction "1_1") (pintype "passive"))
      (node (ref "F 1.8V PLL0") (pin "1") (pinfunction "1_1") (pintype "passive"))
      (node (ref "F 1.8V PLL1") (pin "1") (pinfunction "1_1") (pintype "passive"))
      (node (ref "F 1.8V PLL2") (pin "1") (pinfunction "1_1") (pintype "passive"))
      (node (ref "F 1.8V SERDES") (pin "1") (pinfunction "1_1") (pintype "passive"))
      (node (ref "F 1.8V USB") (pin "1") (pinfunction "1_1") (pintype "passive"))
      (node (ref "L PMIC Buck2") (pin "2") (pinfunction "2_2") (pintype "passive"))
      (node (ref "PMIC") (pin "20") (pinfunction "PVIN_LD02_20") (pintype "passive"))
      (node (ref "PMIC") (pin "32") (pinfunction "FB_B2_32") (pintype "passive"))
    )
    (net (code "116") (name "2.5V") (class "Default")
      (node (ref "C PMIC 2.5V") (pin "2") (pinfunction "2_2") (pintype "passive"))
      (node (ref "DP83867IRRGZR") (pin "3") (pinfunction "VDDA2P5_3") (pintype "passive"))
      (node (ref "DP83867IRRGZR") (pin "9") (pinfunction "VDDA2P5_9") (pintype "passive"))
      (node (ref "PMIC") (pin "23") (pinfunction "VLDO4_23") (pintype "passive"))
    )
    (net (code "117") (name "3.3Vb") (class "Default")
      (node (ref "C BuckMain Feedback") (pin "1") (pinfunction "1_1") (pintype "passive"))
      (node (ref "C BuckMain VOUT1") (pin "2") (pinfunction "2_2") (pintype "passive"))
      (node (ref "C BuckMain VOUT2") (pin "2") (pinfunction "2_2") (pintype "passive"))
      (node (ref "C BuckMain VOUT3") (pin "2") (pinfunction "2_2") (pintype "passive"))
      (node (ref "C PMIC VIN B1") (pin "2") (pinfunction "2_2") (pintype "passive"))
      (node (ref "C PMIC VIN B2") (pin "2") (pinfunction "2_2") (pintype "passive"))
      (node (ref "C PMIC VIN B3") (pin "2") (pinfunction "2_2") (pintype "passive"))
      (node (ref "C PMIC VIN LDO1") (pin "2") (pinfunction "2_2") (pintype "passive"))
      (node (ref "C PMIC VIN LDO34") (pin "2") (pinfunction "2_2") (pintype "passive"))
      (node (ref "C PMIC VSYS") (pin "2") (pinfunction "2_2") (pintype "passive"))
      (node (ref "C Switch3.3V VIN") (pin "2") (pinfunction "2_2") (pintype "passive"))
      (node (ref "L BuckMain") (pin "2") (pinfunction "2_2") (pintype "passive"))
      (node (ref "LED 3.3Vb") (pin "1") (pinfunction "1_1") (pintype "passive"))
      (node (ref "PMIC") (pin "13") (pinfunction "VSYS_13") (pintype "passive"))
      (node (ref "PMIC") (pin "22") (pinfunction "PVIN_LDO34_22") (pintype "passive"))
      (node (ref "PMIC") (pin "26") (pinfunction "PVIN_B3_26") (pintype "passive"))
      (node (ref "PMIC") (pin "30") (pinfunction "PVIN_B2_30") (pintype "passive"))
      (node (ref "PMIC") (pin "4") (pinfunction "PVIN_B1_1_4") (pintype "passive"))
      (node (ref "PMIC") (pin "5") (pinfunction "PVIN_B1_2_5") (pintype "passive"))
      (node (ref "PMIC") (pin "6") (pinfunction "PVIN_LDO1_6") (pintype "passive"))
      (node (ref "R BuckMain Divider1") (pin "2") (pinfunction "2_2") (pintype "passive"))
      (node (ref "R PMIC SDPullup") (pin "2") (pinfunction "2_2") (pintype "passive"))
      (node (ref "R VMON 1") (pin "2") (pinfunction "2_2") (pintype "passive"))
      (node (ref "Switch3.3V") (pin "1") (pinfunction "VIN_1") (pintype "power_in"))
      (node (ref "Switch3.3V") (pin "2") (pinfunction "VIN_2") (pintype "power_in"))
      (node (ref "Switch3.3V") (pin "3") (pinfunction "VBIAS_3") (pintype "power_in"))
    )
    (net (code "118") (name "3.3Vbs") (class "Default")
      (node (ref "AM6442") (pin "F11") (pinfunction "VDDSHV0_1_F11") (pintype "passive"))
      (node (ref "AM6442") (pin "F9") (pinfunction "VDDSHV_MCU_1_F9") (pintype "passive"))
      (node (ref "AM6442") (pin "G10") (pinfunction "VDDSHV_MCU_3_G10") (pintype "passive"))
      (node (ref "AM6442") (pin "G12") (pinfunction "VDDSHV0_2_G12") (pintype "passive"))
      (node (ref "AM6442") (pin "G14") (pinfunction "VDDSHV0_3_G14") (pintype "passive"))
      (node (ref "AM6442") (pin "G8") (pinfunction "VDDSHV_MCU_2_G8") (pintype "passive"))
      (node (ref "AM6442") (pin "H15") (pinfunction "VDDA_3P3_SDIO_H15") (pintype "passive"))
      (node (ref "AM6442") (pin "M14") (pinfunction "VDDSHV4_1_M14") (pintype "passive"))
      (node (ref "AM6442") (pin "M15") (pinfunction "VDDSHV4_2_M15") (pintype "passive"))
      (node (ref "AM6442") (pin "M7") (pinfunction "VDDSHV1_1_M7") (pintype "passive"))
      (node (ref "AM6442") (pin "N6") (pinfunction "VDDSHV1_2_N6") (pintype "passive"))
      (node (ref "AM6442") (pin "P14") (pinfunction "VDDSHV3_1_P14") (pintype "passive"))
      (node (ref "AM6442") (pin "P15") (pinfunction "VDDSHV3_2_P15") (pintype "passive"))
      (node (ref "AM6442") (pin "P7") (pinfunction "VDDSHV1_3_P7") (pintype "passive"))
      (node (ref "AM6442") (pin "R10") (pinfunction "VDDSHV2_2_R10") (pintype "passive"))
      (node (ref "AM6442") (pin "R13") (pinfunction "VDDA_3P3_USB_R13") (pintype "passive"))
      (node (ref "AM6442") (pin "R8") (pinfunction "VDDSHV2_1_R8") (pintype "passive"))
      (node (ref "AM6442") (pin "T9") (pinfunction "VDDSHV2_3_T9") (pintype "passive"))
      (node (ref "C 3.3V 1uF") (pin "1") (pinfunction "1_1") (pintype "passive"))
      (node (ref "C 3.3V 4.7uF") (pin "1") (pinfunction "1_1") (pintype "passive"))
      (node (ref "C 3.3V MCU1") (pin "1") (pinfunction "1_1") (pintype "passive"))
      (node (ref "C 3.3V MCU2") (pin "1") (pinfunction "1_1") (pintype "passive"))
      (node (ref "C 3.3V MCU3") (pin "1") (pinfunction "1_1") (pintype "passive"))
      (node (ref "C 3.3V SDIO") (pin "1") (pinfunction "1_1") (pintype "passive"))
      (node (ref "C 3.3V SHV01") (pin "1") (pinfunction "1_1") (pintype "passive"))
      (node (ref "C 3.3V SHV02") (pin "1") (pinfunction "1_1") (pintype "passive"))
      (node (ref "C 3.3V SHV03") (pin "1") (pinfunction "1_1") (pintype "passive"))
      (node (ref "C 3.3V SHV11") (pin "1") (pinfunction "1_1") (pintype "passive"))
      (node (ref "C 3.3V SHV12") (pin "1") (pinfunction "1_1") (pintype "passive"))
      (node (ref "C 3.3V SHV13") (pin "1") (pinfunction "1_1") (pintype "passive"))
      (node (ref "C 3.3V SHV21") (pin "1") (pinfunction "1_1") (pintype "passive"))
      (node (ref "C 3.3V SHV22") (pin "1") (pinfunction "1_1") (pintype "passive"))
      (node (ref "C 3.3V SHV23") (pin "1") (pinfunction "1_1") (pintype "passive"))
      (node (ref "C 3.3V SHV31") (pin "1") (pinfunction "1_1") (pintype "passive"))
      (node (ref "C 3.3V SHV32") (pin "1") (pinfunction "1_1") (pintype "passive"))
      (node (ref "C 3.3V SHV41") (pin "1") (pinfunction "1_1") (pintype "passive"))
      (node (ref "C 3.3V SHV42") (pin "1") (pinfunction "1_1") (pintype "passive"))
      (node (ref "C 3.3V USB") (pin "1") (pinfunction "1_1") (pintype "passive"))
      (node (ref "C Switch3.3V VOUT") (pin "2") (pinfunction "2_2") (pintype "passive"))
      (node (ref "CONSD") (pin "4") (pinfunction "VDD_4") (pintype "passive"))
      (node (ref "DP83867IRRGZR") (pin "19") (pinfunction "VDDIO_19") (pintype "passive"))
      (node (ref "DP83867IRRGZR") (pin "30") (pinfunction "VDDIO_30") (pintype "passive"))
      (node (ref "DP83867IRRGZR") (pin "41") (pinfunction "VDDIO_41") (pintype "passive"))
      (node (ref "Switch3.3V") (pin "6") (pinfunction "VOUT_6") (pintype "power_in"))
      (node (ref "Switch3.3V") (pin "7") (pinfunction "VOUT_7") (pintype "power_in"))
      (node (ref "Switch3.3V") (pin "8") (pinfunction "VOUT_8") (pintype "power_in"))
    )
    (net (code "119") (name "GND") (class "Default")
      (node (ref "AM6442") (pin "A1") (pinfunction "VSS_1_A1") (pintype "passive"))
      (node (ref "AM6442") (pin "A21") (pinfunction "VSS_4_A21") (pintype "passive"))
      (node (ref "AM6442") (pin "A5") (pinfunction "VSS_2_A5") (pintype "passive"))
      (node (ref "AM6442") (pin "A6") (pinfunction "VSS_3_A6") (pintype "passive"))
      (node (ref "AM6442") (pin "AA1") (pinfunction "VSS_63_AA1") (pintype "passive"))
      (node (ref "AM6442") (pin "AA15") (pinfunction "VSS_64_AA15") (pintype "passive"))
      (node (ref "AM6442") (pin "AA18") (pinfunction "VSS_65_AA18") (pintype "passive"))
      (node (ref "AM6442") (pin "AA21") (pinfunction "VSS_66_AA21") (pintype "passive"))
      (node (ref "AM6442") (pin "B20") (pinfunction "MCU_OSC0__XO_B20") (pintype "passive"))
      (node (ref "AM6442") (pin "C10") (pinfunction "VSS_6_C10") (pintype "passive"))
      (node (ref "AM6442") (pin "C15") (pinfunction "VSS_7_C15") (pintype "passive"))
      (node (ref "AM6442") (pin "C3") (pinfunction "VSS_5_C3") (pintype "passive"))
      (node (ref "AM6442") (pin "D1") (pinfunction "VSS_8_D1") (pintype "passive"))
      (node (ref "AM6442") (pin "E11") (pinfunction "VSS_9_E11") (pintype "passive"))
      (node (ref "AM6442") (pin "E13") (pinfunction "VSS_10_E13") (pintype "passive"))
      (node (ref "AM6442") (pin "F10") (pinfunction "VSS_12_F10") (pintype "passive"))
      (node (ref "AM6442") (pin "F15") (pinfunction "VSS_13_F15") (pintype "passive"))
      (node (ref "AM6442") (pin "F8") (pinfunction "VSS_11_F8") (pintype "passive"))
      (node (ref "AM6442") (pin "G1") (pinfunction "VSS_14_G1") (pintype "passive"))
      (node (ref "AM6442") (pin "G16") (pinfunction "VSS_18_G16") (pintype "passive"))
      (node (ref "AM6442") (pin "G3") (pinfunction "VSS_15_G3") (pintype "passive"))
      (node (ref "AM6442") (pin "G7") (pinfunction "VSS_16_G7") (pintype "passive"))
      (node (ref "AM6442") (pin "G9") (pinfunction "VSS_17_G9") (pintype "passive"))
      (node (ref "AM6442") (pin "H11") (pinfunction "VSS_21_H11") (pintype "passive"))
      (node (ref "AM6442") (pin "H20") (pinfunction "VSS_22_H20") (pintype "passive"))
      (node (ref "AM6442") (pin "H21") (pinfunction "VSS_23_H21") (pintype "passive"))
      (node (ref "AM6442") (pin "H6") (pinfunction "VSS_19_H6") (pintype "passive"))
      (node (ref "AM6442") (pin "H8") (pinfunction "VSS_20_H8") (pintype "passive"))
      (node (ref "AM6442") (pin "J14") (pinfunction "VSS_26_J14") (pintype "passive"))
      (node (ref "AM6442") (pin "J16") (pinfunction "ADC0_REFN_J16") (pintype "passive"))
      (node (ref "AM6442") (pin "J7") (pinfunction "VSS_24_J7") (pintype "passive"))
      (node (ref "AM6442") (pin "J9") (pinfunction "VSS_25_J9") (pintype "passive"))
      (node (ref "AM6442") (pin "K6") (pinfunction "VSS_27_K6") (pintype "passive"))
      (node (ref "AM6442") (pin "K8") (pinfunction "VSS_28_K8") (pintype "passive"))
      (node (ref "AM6442") (pin "L1") (pinfunction "VSS_29_L1") (pintype "passive"))
      (node (ref "AM6442") (pin "L16") (pinfunction "VSS_33_L16") (pintype "passive"))
      (node (ref "AM6442") (pin "L3") (pinfunction "VSS_30_L3") (pintype "passive"))
      (node (ref "AM6442") (pin "L7") (pinfunction "VSS_31_L7") (pintype "passive"))
      (node (ref "AM6442") (pin "L9") (pinfunction "VSS_32_L9") (pintype "passive"))
      (node (ref "AM6442") (pin "M10") (pinfunction "VSS_36_M10") (pintype "passive"))
      (node (ref "AM6442") (pin "M12") (pinfunction "VSS_37_M12") (pintype "passive"))
      (node (ref "AM6442") (pin "M6") (pinfunction "VSS_34_M6") (pintype "passive"))
      (node (ref "AM6442") (pin "M8") (pinfunction "VSS_35_M8") (pintype "passive"))
      (node (ref "AM6442") (pin "N11") (pinfunction "VSS_40_N11") (pintype "passive"))
      (node (ref "AM6442") (pin "N13") (pinfunction "VSS_41_N13") (pintype "passive"))
      (node (ref "AM6442") (pin "N15") (pinfunction "VSS_42_N15") (pintype "passive"))
      (node (ref "AM6442") (pin "N7") (pinfunction "VSS_38_N7") (pintype "passive"))
      (node (ref "AM6442") (pin "N9") (pinfunction "VSS_39_N9") (pintype "passive"))
      (node (ref "AM6442") (pin "P1") (pinfunction "VSS_43_P1") (pintype "passive"))
      (node (ref "AM6442") (pin "P10") (pinfunction "VSS_46_P10") (pintype "passive"))
      (node (ref "AM6442") (pin "P18") (pinfunction "VSS_47_P18") (pintype "passive"))
      (node (ref "AM6442") (pin "P6") (pinfunction "VSS_44_P6") (pintype "passive"))
      (node (ref "AM6442") (pin "P8") (pinfunction "VSS_45_P8") (pintype "passive"))
      (node (ref "AM6442") (pin "R12") (pinfunction "VSS_50_R12") (pintype "passive"))
      (node (ref "AM6442") (pin "R7") (pinfunction "VSS_48_R7") (pintype "passive"))
      (node (ref "AM6442") (pin "R9") (pinfunction "VSS_49_R9") (pintype "passive"))
      (node (ref "AM6442") (pin "T10") (pinfunction "VSS_52_T10") (pintype "passive"))
      (node (ref "AM6442") (pin "T11") (pinfunction "VSS_53_T11") (pintype "passive"))
      (node (ref "AM6442") (pin "T15") (pinfunction "VSS_54_T15") (pintype "passive"))
      (node (ref "AM6442") (pin "T16") (pinfunction "VSS_55_T16") (pintype "passive"))
      (node (ref "AM6442") (pin "T8") (pinfunction "VSS_51_T8") (pintype "passive"))
      (node (ref "AM6442") (pin "U3") (pinfunction "VSS_56_U3") (pintype "passive"))
      (node (ref "AM6442") (pin "V17") (pinfunction "VSS_57_V17") (pintype "passive"))
      (node (ref "AM6442") (pin "W10") (pinfunction "VSS_58_W10") (pintype "passive"))
      (node (ref "AM6442") (pin "W18") (pinfunction "VSS_59_W18") (pintype "passive"))
      (node (ref "AM6442") (pin "Y14") (pinfunction "VSS_60_Y14") (pintype "passive"))
      (node (ref "AM6442") (pin "Y17") (pinfunction "VSS_61_Y17") (pintype "passive"))
      (node (ref "AM6442") (pin "Y19") (pinfunction "VSS_62_Y19") (pintype "passive"))
      (node (ref "BergStrip GND_1") (pin "1") (pinfunction "Pin_1") (pintype "passive"))
      (node (ref "BergStrip GND_2") (pin "1") (pinfunction "Pin_1") (pintype "passive"))
      (node (ref "BergStrip GND_3") (pin "1") (pinfunction "Pin_1") (pintype "passive"))
      (node (ref "BuckMain") (pin "1") (pinfunction "GND_1") (pintype "passive"))
      (node (ref "C 0.75V 1uF") (pin "2") (pinfunction "2_2") (pintype "passive"))
      (node (ref "C 0.75V 47uF") (pin "2") (pinfunction "2_2") (pintype "passive"))
      (node (ref "C 0.75V Core1") (pin "2") (pinfunction "2_2") (pintype "passive"))
      (node (ref "C 0.75V Core10") (pin "2") (pinfunction "2_2") (pintype "passive"))
      (node (ref "C 0.75V Core11") (pin "2") (pinfunction "2_2") (pintype "passive"))
      (node (ref "C 0.75V Core2") (pin "2") (pinfunction "2_2") (pintype "passive"))
      (node (ref "C 0.75V Core3") (pin "2") (pinfunction "2_2") (pintype "passive"))
      (node (ref "C 0.75V Core4") (pin "2") (pinfunction "2_2") (pintype "passive"))
      (node (ref "C 0.75V Core5") (pin "2") (pinfunction "2_2") (pintype "passive"))
      (node (ref "C 0.75V Core6") (pin "2") (pinfunction "2_2") (pintype "passive"))
      (node (ref "C 0.75V Core7") (pin "2") (pinfunction "2_2") (pintype "passive"))
      (node (ref "C 0.75V Core8") (pin "2") (pinfunction "2_2") (pintype "passive"))
      (node (ref "C 0.75V Core9") (pin "2") (pinfunction "2_2") (pintype "passive"))
      (node (ref "C 0.85V 1uF") (pin "2") (pinfunction "2_2") (pintype "passive"))
      (node (ref "C 0.85V 4.7uF") (pin "2") (pinfunction "2_2") (pintype "passive"))
      (node (ref "C 0.85V Core1") (pin "1") (pinfunction "1_1") (pintype "passive"))
      (node (ref "C 0.85V Core2") (pin "1") (pinfunction "1_1") (pintype "passive"))
      (node (ref "C 0.85V MMC0") (pin "1") (pinfunction "1_1") (pintype "passive"))
      (node (ref "C 0.85V MMC0 0.1uF") (pin "1") (pinfunction "1_1") (pintype "passive"))
      (node (ref "C 0.85V MMC0DLL") (pin "1") (pinfunction "1_1") (pintype "passive"))
      (node (ref "C 0.85V MMC0DLL 0.1uF") (pin "1") (pinfunction "1_1") (pintype "passive"))
      (node (ref "C 0.85V SERDES 0.1uF") (pin "1") (pinfunction "1_1") (pintype "passive"))
      (node (ref "C 0.85V SERDES1") (pin "1") (pinfunction "1_1") (pintype "passive"))
      (node (ref "C 0.85V SERDES2") (pin "1") (pinfunction "1_1") (pintype "passive"))
      (node (ref "C 0.85V SERDES3") (pin "1") (pinfunction "1_1") (pintype "passive"))
      (node (ref "C 0.85V USB") (pin "1") (pinfunction "1_1") (pintype "passive"))
      (node (ref "C 0.85V USB 1uF") (pin "1") (pinfunction "1_1") (pintype "passive"))
      (node (ref "C 1.1V DDR 10uF") (pin "2") (pinfunction "2_2") (pintype "passive"))
      (node (ref "C 1.1V DDR 1uF") (pin "2") (pinfunction "2_2") (pintype "passive"))
      (node (ref "C 1.1V DDR VDD2 10uF") (pin "2") (pinfunction "2_2") (pintype "passive"))
      (node (ref "C 1.1V DDR VDDQ 10uF") (pin "2") (pinfunction "2_2") (pintype "passive"))
      (node (ref "C 1.1V DDR1") (pin "2") (pinfunction "2_2") (pintype "passive"))
      (node (ref "C 1.1V DDR10") (pin "2") (pinfunction "2_2") (pintype "passive"))
      (node (ref "C 1.1V DDR11") (pin "2") (pinfunction "2_2") (pintype "passive"))
      (node (ref "C 1.1V DDR12") (pin "2") (pinfunction "2_2") (pintype "passive"))
      (node (ref "C 1.1V DDR13") (pin "2") (pinfunction "2_2") (pintype "passive"))
      (node (ref "C 1.1V DDR14") (pin "2") (pinfunction "2_2") (pintype "passive"))
      (node (ref "C 1.1V DDR15") (pin "2") (pinfunction "2_2") (pintype "passive"))
      (node (ref "C 1.1V DDR16") (pin "2") (pinfunction "2_2") (pintype "passive"))
      (node (ref "C 1.1V DDR17") (pin "2") (pinfunction "2_2") (pintype "passive"))
      (node (ref "C 1.1V DDR18") (pin "2") (pinfunction "2_2") (pintype "passive"))
      (node (ref "C 1.1V DDR19") (pin "2") (pinfunction "2_2") (pintype "passive"))
      (node (ref "C 1.1V DDR2") (pin "2") (pinfunction "2_2") (pintype "passive"))
      (node (ref "C 1.1V DDR20") (pin "2") (pinfunction "2_2") (pintype "passive"))
      (node (ref "C 1.1V DDR21") (pin "2") (pinfunction "2_2") (pintype "passive"))
      (node (ref "C 1.1V DDR22") (pin "2") (pinfunction "2_2") (pintype "passive"))
      (node (ref "C 1.1V DDR23") (pin "2") (pinfunction "2_2") (pintype "passive"))
      (node (ref "C 1.1V DDR24") (pin "2") (pinfunction "2_2") (pintype "passive"))
      (node (ref "C 1.1V DDR25") (pin "2") (pinfunction "2_2") (pintype "passive"))
      (node (ref "C 1.1V DDR26") (pin "2") (pinfunction "2_2") (pintype "passive"))
      (node (ref "C 1.1V DDR27") (pin "2") (pinfunction "2_2") (pintype "passive"))
      (node (ref "C 1.1V DDR3") (pin "2") (pinfunction "2_2") (pintype "passive"))
      (node (ref "C 1.1V DDR4") (pin "2") (pinfunction "2_2") (pintype "passive"))
      (node (ref "C 1.1V DDR5") (pin "2") (pinfunction "2_2") (pintype "passive"))
      (node (ref "C 1.1V DDR6") (pin "2") (pinfunction "2_2") (pintype "passive"))
      (node (ref "C 1.1V DDR7") (pin "2") (pinfunction "2_2") (pintype "passive"))
      (node (ref "C 1.1V DDR8") (pin "2") (pinfunction "2_2") (pintype "passive"))
      (node (ref "C 1.1V DDR9") (pin "2") (pinfunction "2_2") (pintype "passive"))
      (node (ref "C 1.8V ADC") (pin "1") (pinfunction "1_1") (pintype "passive"))
      (node (ref "C 1.8V ADC 1uF") (pin "1") (pinfunction "1_1") (pintype "passive"))
      (node (ref "C 1.8V ADCREF") (pin "1") (pinfunction "1_1") (pintype "passive"))
      (node (ref "C 1.8V ClockBuffer") (pin "1") (pinfunction "1_1") (pintype "passive"))
      (node (ref "C 1.8V Crystal") (pin "1") (pinfunction "1_1") (pintype "passive"))
      (node (ref "C 1.8V DDR VDD1 10uF") (pin "2") (pinfunction "2_2") (pintype "passive"))
      (node (ref "C 1.8V DDR1") (pin "2") (pinfunction "2_2") (pintype "passive"))
      (node (ref "C 1.8V DDR2") (pin "2") (pinfunction "2_2") (pintype "passive"))
      (node (ref "C 1.8V DDR3") (pin "2") (pinfunction "2_2") (pintype "passive"))
      (node (ref "C 1.8V DDR4") (pin "2") (pinfunction "2_2") (pintype "passive"))
      (node (ref "C 1.8V DDR5") (pin "2") (pinfunction "2_2") (pintype "passive"))
      (node (ref "C 1.8V DDR6") (pin "2") (pinfunction "2_2") (pintype "passive"))
      (node (ref "C 1.8V DDR7") (pin "2") (pinfunction "2_2") (pintype "passive"))
      (node (ref "C 1.8V DDR8") (pin "2") (pinfunction "2_2") (pintype "passive"))
      (node (ref "C 1.8V MCU") (pin "1") (pinfunction "1_1") (pintype "passive"))
      (node (ref "C 1.8V MCU 1uF") (pin "1") (pinfunction "1_1") (pintype "passive"))
      (node (ref "C 1.8V MMC0") (pin "1") (pinfunction "1_1") (pintype "passive"))
      (node (ref "C 1.8V MMC0 1uF") (pin "1") (pinfunction "1_1") (pintype "passive"))
      (node (ref "C 1.8V OSC") (pin "1") (pinfunction "1_1") (pintype "passive"))
      (node (ref "C 1.8V OSC 1uF") (pin "1") (pinfunction "1_1") (pintype "passive"))
      (node (ref "C 1.8V PLL0") (pin "1") (pinfunction "1_1") (pintype "passive"))
      (node (ref "C 1.8V PLL0 1uF") (pin "1") (pinfunction "1_1") (pintype "passive"))
      (node (ref "C 1.8V PLL1") (pin "1") (pinfunction "1_1") (pintype "passive"))
      (node (ref "C 1.8V PLL1 1uF") (pin "1") (pinfunction "1_1") (pintype "passive"))
      (node (ref "C 1.8V PLL2") (pin "1") (pinfunction "1_1") (pintype "passive"))
      (node (ref "C 1.8V PLL2 1uF") (pin "1") (pinfunction "1_1") (pintype "passive"))
      (node (ref "C 1.8V SERDES") (pin "1") (pinfunction "1_1") (pintype "passive"))
      (node (ref "C 1.8V SERDES 1uF") (pin "1") (pinfunction "1_1") (pintype "passive"))
      (node (ref "C 1.8V USB") (pin "1") (pinfunction "1_1") (pintype "passive"))
      (node (ref "C 1.8V USB 1uF") (pin "1") (pinfunction "1_1") (pintype "passive"))
      (node (ref "C 3.3V 1uF") (pin "2") (pinfunction "2_2") (pintype "passive"))
      (node (ref "C 3.3V 4.7uF") (pin "2") (pinfunction "2_2") (pintype "passive"))
      (node (ref "C 3.3V MCU1") (pin "2") (pinfunction "2_2") (pintype "passive"))
      (node (ref "C 3.3V MCU2") (pin "2") (pinfunction "2_2") (pintype "passive"))
      (node (ref "C 3.3V MCU3") (pin "2") (pinfunction "2_2") (pintype "passive"))
      (node (ref "C 3.3V SDIO") (pin "2") (pinfunction "2_2") (pintype "passive"))
      (node (ref "C 3.3V SHV01") (pin "2") (pinfunction "2_2") (pintype "passive"))
      (node (ref "C 3.3V SHV02") (pin "2") (pinfunction "2_2") (pintype "passive"))
      (node (ref "C 3.3V SHV03") (pin "2") (pinfunction "2_2") (pintype "passive"))
      (node (ref "C 3.3V SHV11") (pin "2") (pinfunction "2_2") (pintype "passive"))
      (node (ref "C 3.3V SHV12") (pin "2") (pinfunction "2_2") (pintype "passive"))
      (node (ref "C 3.3V SHV13") (pin "2") (pinfunction "2_2") (pintype "passive"))
      (node (ref "C 3.3V SHV21") (pin "2") (pinfunction "2_2") (pintype "passive"))
      (node (ref "C 3.3V SHV22") (pin "2") (pinfunction "2_2") (pintype "passive"))
      (node (ref "C 3.3V SHV23") (pin "2") (pinfunction "2_2") (pintype "passive"))
      (node (ref "C 3.3V SHV31") (pin "2") (pinfunction "2_2") (pintype "passive"))
      (node (ref "C 3.3V SHV32") (pin "2") (pinfunction "2_2") (pintype "passive"))
      (node (ref "C 3.3V SHV41") (pin "2") (pinfunction "2_2") (pintype "passive"))
      (node (ref "C 3.3V SHV42") (pin "2") (pinfunction "2_2") (pintype "passive"))
      (node (ref "C 3.3V SHV51") (pin "2") (pinfunction "2_2") (pintype "passive"))
      (node (ref "C 3.3V SHV52") (pin "2") (pinfunction "2_2") (pintype "passive"))
      (node (ref "C 3.3V USB") (pin "2") (pinfunction "2_2") (pintype "passive"))
      (node (ref "C AM6442 CAP VDDS0") (pin "2") (pinfunction "2_2") (pintype "passive"))
      (node (ref "C AM6442 CAP VDDS1") (pin "2") (pinfunction "2_2") (pintype "passive"))
      (node (ref "C AM6442 CAP VDDS2") (pin "2") (pinfunction "2_2") (pintype "passive"))
      (node (ref "C AM6442 CAP VDDS3") (pin "2") (pinfunction "2_2") (pintype "passive"))
      (node (ref "C AM6442 CAP VDDS4") (pin "2") (pinfunction "2_2") (pintype "passive"))
      (node (ref "C AM6442 CAP VDDS5") (pin "2") (pinfunction "2_2") (pintype "passive"))
      (node (ref "C AM6442 CAP VDDS_MCU") (pin "2") (pinfunction "2_2") (pintype "passive"))
      (node (ref "C AM6442 CAP VDDS_MMC") (pin "2") (pinfunction "2_2") (pintype "passive"))
      (node (ref "C BuckMain VIN") (pin "1") (pinfunction "1_1") (pintype "passive"))
      (node (ref "C BuckMain VOUT1") (pin "1") (pinfunction "1_1") (pintype "passive"))
      (node (ref "C BuckMain VOUT2") (pin "1") (pinfunction "1_1") (pintype "passive"))
      (node (ref "C BuckMain VOUT3") (pin "1") (pinfunction "1_1") (pintype "passive"))
      (node (ref "C PMIC 0.75V") (pin "1") (pinfunction "1_1") (pintype "passive"))
      (node (ref "C PMIC 0.85V") (pin "1") (pinfunction "1_1") (pintype "passive"))
      (node (ref "C PMIC 1.1V") (pin "1") (pinfunction "1_1") (pintype "passive"))
      (node (ref "C PMIC 1.8V") (pin "1") (pinfunction "1_1") (pintype "passive"))
      (node (ref "C PMIC 1.8V*") (pin "1") (pinfunction "1_1") (pintype "passive"))
      (node (ref "C PMIC 2.5V") (pin "1") (pinfunction "1_1") (pintype "passive"))
      (node (ref "C PMIC InternalBypass") (pin "1") (pinfunction "1_1") (pintype "passive"))
      (node (ref "C PMIC SD_VDD") (pin "1") (pinfunction "1_1") (pintype "passive"))
      (node (ref "C PMIC VIN B1") (pin "1") (pinfunction "1_1") (pintype "passive"))
      (node (ref "C PMIC VIN B2") (pin "1") (pinfunction "1_1") (pintype "passive"))
      (node (ref "C PMIC VIN B3") (pin "1") (pinfunction "1_1") (pintype "passive"))
      (node (ref "C PMIC VIN LDO1") (pin "1") (pinfunction "1_1") (pintype "passive"))
      (node (ref "C PMIC VIN LDO2") (pin "1") (pinfunction "1_1") (pintype "passive"))
      (node (ref "C PMIC VIN LDO34") (pin "1") (pinfunction "1_1") (pintype "passive"))
      (node (ref "C PMIC VSYS") (pin "1") (pinfunction "1_1") (pintype "passive"))
      (node (ref "C Switch3.3V VIN") (pin "1") (pinfunction "1_1") (pintype "passive"))
      (node (ref "C Switch3.3V VOUT") (pin "1") (pinfunction "1_1") (pintype "passive"))
      (node (ref "CONSD") (pin "6") (pinfunction "VSS_6") (pintype "passive"))
      (node (ref "ClockBuffer") (pin "4") (pinfunction "GND_4") (pintype "passive"))
      (node (ref "DP83867IRRGZR") (pin "49") (pinfunction "GND_49") (pintype "passive"))
      (node (ref "LPDDR4") (pin "A10") (pinfunction "VSS_2_A10") (pintype "passive"))
      (node (ref "LPDDR4") (pin "A3") (pinfunction "VSS_1_A3") (pintype "passive"))
      (node (ref "LPDDR4") (pin "AB10") (pinfunction "VSS_58_AB10") (pintype "passive"))
      (node (ref "LPDDR4") (pin "AB3") (pinfunction "VSS_55_AB3") (pintype "passive"))
      (node (ref "LPDDR4") (pin "AB5") (pinfunction "VSS_56_AB5") (pintype "passive"))
      (node (ref "LPDDR4") (pin "AB8") (pinfunction "VSS_57_AB8") (pintype "passive"))
      (node (ref "LPDDR4") (pin "C1") (pinfunction "VSS_3_C1") (pintype "passive"))
      (node (ref "LPDDR4") (pin "C12") (pinfunction "VSS_6_C12") (pintype "passive"))
      (node (ref "LPDDR4") (pin "C5") (pinfunction "VSS_4_C5") (pintype "passive"))
      (node (ref "LPDDR4") (pin "C8") (pinfunction "VSS_5_C8") (pintype "passive"))
      (node (ref "LPDDR4") (pin "D11") (pinfunction "VSS_10_D11") (pintype "passive"))
      (node (ref "LPDDR4") (pin "D2") (pinfunction "VSS_7_D2") (pintype "passive"))
      (node (ref "LPDDR4") (pin "D4") (pinfunction "VSS_8_D4") (pintype "passive"))
      (node (ref "LPDDR4") (pin "D9") (pinfunction "VSS_9_D9") (pintype "passive"))
      (node (ref "LPDDR4") (pin "E1") (pinfunction "VSS_11_E1") (pintype "passive"))
      (node (ref "LPDDR4") (pin "E12") (pinfunction "VSS_14_E12") (pintype "passive"))
      (node (ref "LPDDR4") (pin "E5") (pinfunction "VSS_12_E5") (pintype "passive"))
      (node (ref "LPDDR4") (pin "E8") (pinfunction "VSS_13_E8") (pintype "passive"))
      (node (ref "LPDDR4") (pin "G1") (pinfunction "VSS_15_G1") (pintype "passive"))
      (node (ref "LPDDR4") (pin "G10") (pinfunction "VSS_19_G10") (pintype "passive"))
      (node (ref "LPDDR4") (pin "G12") (pinfunction "VSS_20_G12") (pintype "passive"))
      (node (ref "LPDDR4") (pin "G3") (pinfunction "VSS_16_G3") (pintype "passive"))
      (node (ref "LPDDR4") (pin "G5") (pinfunction "VSS_17_G5") (pintype "passive"))
      (node (ref "LPDDR4") (pin "G8") (pinfunction "VSS_18_G8") (pintype "passive"))
      (node (ref "LPDDR4") (pin "J1") (pinfunction "VSS_21_J1") (pintype "passive"))
      (node (ref "LPDDR4") (pin "J10") (pinfunction "VSS_23_J10") (pintype "passive"))
      (node (ref "LPDDR4") (pin "J12") (pinfunction "VSS_24_J12") (pintype "passive"))
      (node (ref "LPDDR4") (pin "J3") (pinfunction "VSS_22_J3") (pintype "passive"))
      (node (ref "LPDDR4") (pin "K11") (pinfunction "VSS_28_K11") (pintype "passive"))
      (node (ref "LPDDR4") (pin "K2") (pinfunction "VSS_25_K2") (pintype "passive"))
      (node (ref "LPDDR4") (pin "K4") (pinfunction "VSS_26_K4") (pintype "passive"))
      (node (ref "LPDDR4") (pin "K9") (pinfunction "VSS_27_K9") (pintype "passive"))
      (node (ref "LPDDR4") (pin "N11") (pinfunction "VSS_32_N11") (pintype "passive"))
      (node (ref "LPDDR4") (pin "N2") (pinfunction "VSS_29_N2") (pintype "passive"))
      (node (ref "LPDDR4") (pin "N4") (pinfunction "VSS_30_N4") (pintype "passive"))
      (node (ref "LPDDR4") (pin "N9") (pinfunction "VSS_31_N9") (pintype "passive"))
      (node (ref "LPDDR4") (pin "P1") (pinfunction "VSS_33_P1") (pintype "passive"))
      (node (ref "LPDDR4") (pin "P10") (pinfunction "VSS_35_P10") (pintype "passive"))
      (node (ref "LPDDR4") (pin "P12") (pinfunction "VSS_36_P12") (pintype "passive"))
      (node (ref "LPDDR4") (pin "P3") (pinfunction "VSS_34_P3") (pintype "passive"))
      (node (ref "LPDDR4") (pin "T1") (pinfunction "VSS_37_T1") (pintype "passive"))
      (node (ref "LPDDR4") (pin "T10") (pinfunction "VSS_41_T10") (pintype "passive"))
      (node (ref "LPDDR4") (pin "T12") (pinfunction "VSS_42_T12") (pintype "passive"))
      (node (ref "LPDDR4") (pin "T3") (pinfunction "VSS_38_T3") (pintype "passive"))
      (node (ref "LPDDR4") (pin "T5") (pinfunction "VSS_39_T5") (pintype "passive"))
      (node (ref "LPDDR4") (pin "T8") (pinfunction "VSS_40_T8") (pintype "passive"))
      (node (ref "LPDDR4") (pin "V1") (pinfunction "VSS_43_V1") (pintype "passive"))
      (node (ref "LPDDR4") (pin "V12") (pinfunction "VSS_46_V12") (pintype "passive"))
      (node (ref "LPDDR4") (pin "V5") (pinfunction "VSS_44_V5") (pintype "passive"))
      (node (ref "LPDDR4") (pin "V8") (pinfunction "VSS_45_V8") (pintype "passive"))
      (node (ref "LPDDR4") (pin "W11") (pinfunction "VSS_50_W11") (pintype "passive"))
      (node (ref "LPDDR4") (pin "W2") (pinfunction "VSS_47_W2") (pintype "passive"))
      (node (ref "LPDDR4") (pin "W4") (pinfunction "VSS_48_W4") (pintype "passive"))
      (node (ref "LPDDR4") (pin "W9") (pinfunction "VSS_49_W9") (pintype "passive"))
      (node (ref "LPDDR4") (pin "Y1") (pinfunction "VSS_51_Y1") (pintype "passive"))
      (node (ref "LPDDR4") (pin "Y12") (pinfunction "VSS_54_Y12") (pintype "passive"))
      (node (ref "LPDDR4") (pin "Y5") (pinfunction "VSS_52_Y5") (pintype "passive"))
      (node (ref "LPDDR4") (pin "Y8") (pinfunction "VSS_53_Y8") (pintype "passive"))
      (node (ref "PMIC") (pin "15") (pinfunction "AGND_15") (pintype "passive"))
      (node (ref "PMIC") (pin "33") (pinfunction "EPAD_33") (pintype "passive"))
      (node (ref "R 3.3Vb LED") (pin "1") (pinfunction "1_1") (pintype "passive"))
      (node (ref "R BuckMain Divider3") (pin "2") (pinfunction "2_2") (pintype "passive"))
      (node (ref "R DDR CAL") (pin "1") (pinfunction "1_1") (pintype "passive"))
      (node (ref "R DDR RESET") (pin "2") (pinfunction "2_2") (pintype "passive"))
      (node (ref "R VCC LED") (pin "1") (pinfunction "1_1") (pintype "passive"))
      (node (ref "R VMON 2") (pin "1") (pinfunction "1_1") (pintype "passive"))
      (node (ref "Switch3.3V") (pin "5") (pinfunction "GND_5") (pintype "power_in"))
      (node (ref "Switch3.3V") (pin "9") (pinfunction "PAD_9") (pintype "power_in"))
      (node (ref "X") (pin "2") (pinfunction "GND_2") (pintype "passive"))
    )
    (net (code "120") (name "Net-(LED 3.3Vb-Pad2)") (class "Default")
      (node (ref "LED 3.3Vb") (pin "2") (pinfunction "2_2") (pintype "passive"))
      (node (ref "R 3.3Vb LED") (pin "2") (pinfunction "2_2") (pintype "passive"))
    )
    (net (code "121") (name "Net-(LED VCC-Pad2)") (class "Default")
      (node (ref "LED VCC") (pin "2") (pinfunction "2_2") (pintype "passive"))
      (node (ref "R VCC LED") (pin "2") (pinfunction "2_2") (pintype "passive"))
    )
    (net (code "122") (name "SD VDD") (class "Default")
      (node (ref "AM6442") (pin "L13") (pinfunction "CAP_VDDS5_L13") (pintype "passive"))
      (node (ref "AM6442") (pin "L14") (pinfunction "VDDSHV5_1_L14") (pintype "passive"))
      (node (ref "AM6442") (pin "L15") (pinfunction "VDDSHV5_2_L15") (pintype "passive"))
      (node (ref "C 3.3V SHV51") (pin "1") (pinfunction "1_1") (pintype "passive"))
      (node (ref "C 3.3V SHV52") (pin "1") (pinfunction "1_1") (pintype "passive"))
      (node (ref "C AM6442 CAP VDDS5") (pin "1") (pinfunction "1_1") (pintype "passive"))
      (node (ref "C PMIC SD_VDD") (pin "2") (pinfunction "2_2") (pintype "passive"))
      (node (ref "PMIC") (pin "7") (pinfunction "VLDO1_7") (pintype "passive"))
    )
    (net (code "123") (name "VCC") (class "Default")
      (node (ref "BergStrip 5V_1") (pin "1") (pinfunction "Pin_1") (pintype "passive"))
      (node (ref "BergStrip 5V_2") (pin "1") (pinfunction "Pin_1") (pintype "passive"))
      (node (ref "BergStrip 5V_3") (pin "1") (pinfunction "Pin_1") (pintype "passive"))
      (node (ref "BuckMain") (pin "3") (pinfunction "VIN_3") (pintype "passive"))
      (node (ref "BuckMain") (pin "4") (pinfunction "EN_4") (pintype "passive"))
      (node (ref "C BuckMain VIN") (pin "2") (pinfunction "2_2") (pintype "passive"))
      (node (ref "LED VCC") (pin "1") (pinfunction "1_1") (pintype "passive"))
    )
    (net (code "124") (name "unconnected-(AM6442-ADC0_AIN0-PadG20)") (class "Default")
      (node (ref "AM6442") (pin "G20") (pinfunction "ADC0_AIN0_G20") (pintype "passive"))
    )
    (net (code "125") (name "unconnected-(AM6442-ADC0_AIN1-PadF20)") (class "Default")
      (node (ref "AM6442") (pin "F20") (pinfunction "ADC0_AIN1_F20") (pintype "passive"))
    )
    (net (code "126") (name "unconnected-(AM6442-ADC0_AIN2-PadE21)") (class "Default")
      (node (ref "AM6442") (pin "E21") (pinfunction "ADC0_AIN2_E21") (pintype "passive"))
    )
    (net (code "127") (name "unconnected-(AM6442-ADC0_AIN3-PadD20)") (class "Default")
      (node (ref "AM6442") (pin "D20") (pinfunction "ADC0_AIN3_D20") (pintype "passive"))
    )
    (net (code "128") (name "unconnected-(AM6442-ADC0_AIN4-PadG21)") (class "Default")
      (node (ref "AM6442") (pin "G21") (pinfunction "ADC0_AIN4_G21") (pintype "passive"))
    )
    (net (code "129") (name "unconnected-(AM6442-ADC0_AIN5-PadF21)") (class "Default")
      (node (ref "AM6442") (pin "F21") (pinfunction "ADC0_AIN5_F21") (pintype "passive"))
    )
    (net (code "130") (name "unconnected-(AM6442-ADC0_AIN6-PadF19)") (class "Default")
      (node (ref "AM6442") (pin "F19") (pinfunction "ADC0_AIN6_F19") (pintype "passive"))
    )
    (net (code "131") (name "unconnected-(AM6442-ADC0_AIN7-PadE20)") (class "Default")
      (node (ref "AM6442") (pin "E20") (pinfunction "ADC0_AIN7_E20") (pintype "passive"))
    )
    (net (code "132") (name "unconnected-(AM6442-DDR0_A6-PadJ2)") (class "Default")
      (node (ref "AM6442") (pin "J2") (pinfunction "DDR0_A6_J2") (pintype "passive"))
    )
    (net (code "133") (name "unconnected-(AM6442-DDR0_A7-PadL5)") (class "Default")
      (node (ref "AM6442") (pin "L5") (pinfunction "DDR0_A7_L5") (pintype "passive"))
    )
    (net (code "134") (name "unconnected-(AM6442-DDR0_A8-PadJ3)") (class "Default")
      (node (ref "AM6442") (pin "J3") (pinfunction "DDR0_A8_J3") (pintype "passive"))
    )
    (net (code "135") (name "unconnected-(AM6442-DDR0_A9-PadJ4)") (class "Default")
      (node (ref "AM6442") (pin "J4") (pinfunction "DDR0_A9_J4") (pintype "passive"))
    )
    (net (code "136") (name "unconnected-(AM6442-DDR0_A10-PadK3)") (class "Default")
      (node (ref "AM6442") (pin "K3") (pinfunction "DDR0_A10_K3") (pintype "passive"))
    )
    (net (code "137") (name "unconnected-(AM6442-DDR0_A11-PadJ1)") (class "Default")
      (node (ref "AM6442") (pin "J1") (pinfunction "DDR0_A11_J1") (pintype "passive"))
    )
    (net (code "138") (name "unconnected-(AM6442-DDR0_A12-PadM5)") (class "Default")
      (node (ref "AM6442") (pin "M5") (pinfunction "DDR0_A12_M5") (pintype "passive"))
    )
    (net (code "139") (name "unconnected-(AM6442-DDR0_A13-PadK4)") (class "Default")
      (node (ref "AM6442") (pin "K4") (pinfunction "DDR0_A13_K4") (pintype "passive"))
    )
    (net (code "140") (name "unconnected-(AM6442-DDR0_ACT_N-PadH2)") (class "Default")
      (node (ref "AM6442") (pin "H2") (pinfunction "DDR0_ACT_N_H2") (pintype "passive"))
    )
    (net (code "141") (name "unconnected-(AM6442-DDR0_ALERT_N-PadH1)") (class "Default")
      (node (ref "AM6442") (pin "H1") (pinfunction "DDR0_ALERT_N_H1") (pintype "passive"))
    )
    (net (code "142") (name "unconnected-(AM6442-DDR0_BA0-PadG4)") (class "Default")
      (node (ref "AM6442") (pin "G4") (pinfunction "DDR0_BA0_G4") (pintype "passive"))
    )
    (net (code "143") (name "unconnected-(AM6442-DDR0_BA1-PadG5)") (class "Default")
      (node (ref "AM6442") (pin "G5") (pinfunction "DDR0_BA1_G5") (pintype "passive"))
    )
    (net (code "144") (name "unconnected-(AM6442-DDR0_BG0-PadG2)") (class "Default")
      (node (ref "AM6442") (pin "G2") (pinfunction "DDR0_BG0_G2") (pintype "passive"))
    )
    (net (code "145") (name "unconnected-(AM6442-DDR0_BG1-PadH3)") (class "Default")
      (node (ref "AM6442") (pin "H3") (pinfunction "DDR0_BG1_H3") (pintype "passive"))
    )
    (net (code "146") (name "unconnected-(AM6442-DDR0_CAS_N-PadJ5)") (class "Default")
      (node (ref "AM6442") (pin "J5") (pinfunction "DDR0_CAS_N_J5") (pintype "passive"))
    )
    (net (code "147") (name "unconnected-(AM6442-DDR0_CKE1-PadF3)") (class "Default")
      (node (ref "AM6442") (pin "F3") (pinfunction "DDR0_CKE1_F3") (pintype "passive"))
    )
    (net (code "148") (name "unconnected-(AM6442-DDR0_CS1_N-PadE4)") (class "Default")
      (node (ref "AM6442") (pin "E4") (pinfunction "DDR0_CS1_N_E4") (pintype "passive"))
    )
    (net (code "149") (name "unconnected-(AM6442-DDR0_ODT0-PadE5)") (class "Default")
      (node (ref "AM6442") (pin "E5") (pinfunction "DDR0_ODT0_E5") (pintype "passive"))
    )
    (net (code "150") (name "unconnected-(AM6442-DDR0_ODT1-PadF5)") (class "Default")
      (node (ref "AM6442") (pin "F5") (pinfunction "DDR0_ODT1_F5") (pintype "passive"))
    )
    (net (code "151") (name "unconnected-(AM6442-DDR0_PAR-PadK5)") (class "Default")
      (node (ref "AM6442") (pin "K5") (pinfunction "DDR0_PAR_K5") (pintype "passive"))
    )
    (net (code "152") (name "unconnected-(AM6442-DDR0_RAS_N-PadF6)") (class "Default")
      (node (ref "AM6442") (pin "F6") (pinfunction "DDR0_RAS_N_F6") (pintype "passive"))
    )
    (net (code "153") (name "unconnected-(AM6442-DDR0_WE_N-PadH4)") (class "Default")
      (node (ref "AM6442") (pin "H4") (pinfunction "DDR0_WE_N_H4") (pintype "passive"))
    )
    (net (code "154") (name "unconnected-(AM6442-ECAP0_IN_APWM_OUT-PadD18)") (class "Default")
      (node (ref "AM6442") (pin "D18") (pinfunction "ECAP0_IN_APWM_OUT_D18") (pintype "passive"))
    )
    (net (code "155") (name "unconnected-(AM6442-EXTINTN-PadC19)") (class "Default")
      (node (ref "AM6442") (pin "C19") (pinfunction "EXTINTN_C19") (pintype "passive"))
    )
    (net (code "156") (name "unconnected-(AM6442-EXT_REFCLK1-PadA19)") (class "Default")
      (node (ref "AM6442") (pin "A19") (pinfunction "EXT_REFCLK1_A19") (pintype "passive"))
    )
    (net (code "157") (name "unconnected-(AM6442-GPMC0_AD0-PadT20)") (class "Default")
      (node (ref "AM6442") (pin "T20") (pinfunction "GPMC0_AD0_T20") (pintype "passive"))
    )
    (net (code "158") (name "unconnected-(AM6442-GPMC0_AD1-PadU21)") (class "Default")
      (node (ref "AM6442") (pin "U21") (pinfunction "GPMC0_AD1_U21") (pintype "passive"))
    )
    (net (code "159") (name "unconnected-(AM6442-GPMC0_AD2-PadT18)") (class "Default")
      (node (ref "AM6442") (pin "T18") (pinfunction "GPMC0_AD2_T18") (pintype "passive"))
    )
    (net (code "160") (name "unconnected-(AM6442-GPMC0_AD3V-PadU20)") (class "Default")
      (node (ref "AM6442") (pin "U20") (pinfunction "GPMC0_AD3V_U20") (pintype "passive"))
    )
    (net (code "161") (name "unconnected-(AM6442-GPMC0_AD4-PadU18)") (class "Default")
      (node (ref "AM6442") (pin "U18") (pinfunction "GPMC0_AD4_U18") (pintype "passive"))
    )
    (net (code "162") (name "unconnected-(AM6442-GPMC0_AD5-PadU19)") (class "Default")
      (node (ref "AM6442") (pin "U19") (pinfunction "GPMC0_AD5_U19") (pintype "passive"))
    )
    (net (code "163") (name "unconnected-(AM6442-GPMC0_AD6-PadV20)") (class "Default")
      (node (ref "AM6442") (pin "V20") (pinfunction "GPMC0_AD6_V20") (pintype "passive"))
    )
    (net (code "164") (name "unconnected-(AM6442-GPMC0_AD7-PadV21)") (class "Default")
      (node (ref "AM6442") (pin "V21") (pinfunction "GPMC0_AD7_V21") (pintype "passive"))
    )
    (net (code "165") (name "unconnected-(AM6442-GPMC0_AD8-PadV19)") (class "Default")
      (node (ref "AM6442") (pin "V19") (pinfunction "GPMC0_AD8_V19") (pintype "passive"))
    )
    (net (code "166") (name "unconnected-(AM6442-GPMC0_AD9-PadT17)") (class "Default")
      (node (ref "AM6442") (pin "T17") (pinfunction "GPMC0_AD9_T17") (pintype "passive"))
    )
    (net (code "167") (name "unconnected-(AM6442-GPMC0_AD10-PadR16)") (class "Default")
      (node (ref "AM6442") (pin "R16") (pinfunction "GPMC0_AD10_R16") (pintype "passive"))
    )
    (net (code "168") (name "unconnected-(AM6442-GPMC0_AD11-PadW20)") (class "Default")
      (node (ref "AM6442") (pin "W20") (pinfunction "GPMC0_AD11_W20") (pintype "passive"))
    )
    (net (code "169") (name "unconnected-(AM6442-GPMC0_AD12-PadW21)") (class "Default")
      (node (ref "AM6442") (pin "W21") (pinfunction "GPMC0_AD12_W21") (pintype "passive"))
    )
    (net (code "170") (name "unconnected-(AM6442-GPMC0_AD13-PadV18)") (class "Default")
      (node (ref "AM6442") (pin "V18") (pinfunction "GPMC0_AD13_V18") (pintype "passive"))
    )
    (net (code "171") (name "unconnected-(AM6442-GPMC0_AD14-PadY21)") (class "Default")
      (node (ref "AM6442") (pin "Y21") (pinfunction "GPMC0_AD14_Y21") (pintype "passive"))
    )
    (net (code "172") (name "unconnected-(AM6442-GPMC0_AD15-PadY20)") (class "Default")
      (node (ref "AM6442") (pin "Y20") (pinfunction "GPMC0_AD15_Y20") (pintype "passive"))
    )
    (net (code "173") (name "unconnected-(AM6442-GPMC0_ADVN_ALE-PadP16)") (class "Default")
      (node (ref "AM6442") (pin "P16") (pinfunction "GPMC0_ADVN_ALE_P16") (pintype "passive"))
    )
    (net (code "174") (name "unconnected-(AM6442-GPMC0_BE0N_CLE-PadP17)") (class "Default")
      (node (ref "AM6442") (pin "P17") (pinfunction "GPMC0_BE0N_CLE_P17") (pintype "passive"))
    )
    (net (code "175") (name "unconnected-(AM6442-GPMC0_BE1N-PadT19)") (class "Default")
      (node (ref "AM6442") (pin "T19") (pinfunction "GPMC0_BE1N_T19") (pintype "passive"))
    )
    (net (code "176") (name "unconnected-(AM6442-GPMC0_CLK-PadR17)") (class "Default")
      (node (ref "AM6442") (pin "R17") (pinfunction "GPMC0_CLK_R17") (pintype "passive"))
    )
    (net (code "177") (name "unconnected-(AM6442-GPMC0_CSN0-PadR19)") (class "Default")
      (node (ref "AM6442") (pin "R19") (pinfunction "GPMC0_CSN0_R19") (pintype "passive"))
    )
    (net (code "178") (name "unconnected-(AM6442-GPMC0_CSN1-PadR20)") (class "Default")
      (node (ref "AM6442") (pin "R20") (pinfunction "GPMC0_CSN1_R20") (pintype "passive"))
    )
    (net (code "179") (name "unconnected-(AM6442-GPMC0_CSN2-PadP19)") (class "Default")
      (node (ref "AM6442") (pin "P19") (pinfunction "GPMC0_CSN2_P19") (pintype "passive"))
    )
    (net (code "180") (name "unconnected-(AM6442-GPMC0_CSN3-PadR21)") (class "Default")
      (node (ref "AM6442") (pin "R21") (pinfunction "GPMC0_CSN3_R21") (pintype "passive"))
    )
    (net (code "181") (name "unconnected-(AM6442-GPMC0_DIR-PadN17)") (class "Default")
      (node (ref "AM6442") (pin "N17") (pinfunction "GPMC0_DIR_N17") (pintype "passive"))
    )
    (net (code "182") (name "unconnected-(AM6442-GPMC0_OEN_REN-PadR18)") (class "Default")
      (node (ref "AM6442") (pin "R18") (pinfunction "GPMC0_OEN_REN_R18") (pintype "passive"))
    )
    (net (code "183") (name "unconnected-(AM6442-GPMC0_WAIT0-PadW19)") (class "Default")
      (node (ref "AM6442") (pin "W19") (pinfunction "GPMC0_WAIT0_W19") (pintype "passive"))
    )
    (net (code "184") (name "unconnected-(AM6442-GPMC0_WAIT1-PadY18)") (class "Default")
      (node (ref "AM6442") (pin "Y18") (pinfunction "GPMC0_WAIT1_Y18") (pintype "passive"))
    )
    (net (code "185") (name "unconnected-(AM6442-GPMC0_WEN-PadT21)") (class "Default")
      (node (ref "AM6442") (pin "T21") (pinfunction "GPMC0_WEN_T21") (pintype "passive"))
    )
    (net (code "186") (name "unconnected-(AM6442-GPMC0_WPN-PadN16)") (class "Default")
      (node (ref "AM6442") (pin "N16") (pinfunction "GPMC0_WPN_N16") (pintype "passive"))
    )
    (net (code "187") (name "unconnected-(AM6442-I2C0_SCL-PadA18)") (class "Default")
      (node (ref "AM6442") (pin "A18") (pinfunction "I2C0_SCL_A18") (pintype "passive"))
    )
    (net (code "188") (name "unconnected-(AM6442-I2C0_SDA-PadB18)") (class "Default")
      (node (ref "AM6442") (pin "B18") (pinfunction "I2C0_SDA_B18") (pintype "passive"))
    )
    (net (code "189") (name "unconnected-(AM6442-I2C1_SCL-PadC18)") (class "Default")
      (node (ref "AM6442") (pin "C18") (pinfunction "I2C1_SCL_C18") (pintype "passive"))
    )
    (net (code "190") (name "unconnected-(AM6442-I2C1_SDA-PadB19)") (class "Default")
      (node (ref "AM6442") (pin "B19") (pinfunction "I2C1_SDA_B19") (pintype "passive"))
    )
    (net (code "191") (name "unconnected-(AM6442-MCAN0_RX-PadB17)") (class "Default")
      (node (ref "AM6442") (pin "B17") (pinfunction "MCAN0_RX_B17") (pintype "passive"))
    )
    (net (code "192") (name "unconnected-(AM6442-MCAN0_TX-PadA17)") (class "Default")
      (node (ref "AM6442") (pin "A17") (pinfunction "MCAN0_TX_A17") (pintype "passive"))
    )
    (net (code "193") (name "unconnected-(AM6442-MCAN1_RX-PadD17)") (class "Default")
      (node (ref "AM6442") (pin "D17") (pinfunction "MCAN1_RX_D17") (pintype "passive"))
    )
    (net (code "194") (name "unconnected-(AM6442-MCAN1_TX-PadC17)") (class "Default")
      (node (ref "AM6442") (pin "C17") (pinfunction "MCAN1_TX_C17") (pintype "passive"))
    )
    (net (code "195") (name "unconnected-(AM6442-MCU_I2C0__SCL-PadE9)") (class "Default")
      (node (ref "AM6442") (pin "E9") (pinfunction "MCU_I2C0__SCL_E9") (pintype "passive"))
    )
    (net (code "196") (name "unconnected-(AM6442-MCU_I2C0__SDA-PadA10)") (class "Default")
      (node (ref "AM6442") (pin "A10") (pinfunction "MCU_I2C0__SDA_A10") (pintype "passive"))
    )
    (net (code "197") (name "unconnected-(AM6442-MCU_I2C1__SCL-PadA11)") (class "Default")
      (node (ref "AM6442") (pin "A11") (pinfunction "MCU_I2C1__SCL_A11") (pintype "passive"))
    )
    (net (code "198") (name "unconnected-(AM6442-MCU_I2C1__SDA-PadB10)") (class "Default")
      (node (ref "AM6442") (pin "B10") (pinfunction "MCU_I2C1__SDA_B10") (pintype "passive"))
    )
    (net (code "199") (name "unconnected-(AM6442-MCU_RESET_STATZ-PadB13)") (class "Default")
      (node (ref "AM6442") (pin "B13") (pinfunction "MCU_RESET_STATZ_B13") (pintype "passive+no_connect"))
    )
    (net (code "200") (name "unconnected-(AM6442-MCU_SAFETY_ERROR-PadA20)") (class "Default")
      (node (ref "AM6442") (pin "A20") (pinfunction "MCU_SAFETY_ERROR_A20") (pintype "passive+no_connect"))
    )
    (net (code "201") (name "unconnected-(AM6442-MCU_SPI0__CLK-PadE6)") (class "Default")
      (node (ref "AM6442") (pin "E6") (pinfunction "MCU_SPI0__CLK_E6") (pintype "passive"))
    )
    (net (code "202") (name "unconnected-(AM6442-MCU_SPI0__CS0-PadD6)") (class "Default")
      (node (ref "AM6442") (pin "D6") (pinfunction "MCU_SPI0__CS0_D6") (pintype "passive"))
    )
    (net (code "203") (name "unconnected-(AM6442-MCU_SPI0__CS1-PadC6)") (class "Default")
      (node (ref "AM6442") (pin "C6") (pinfunction "MCU_SPI0__CS1_C6") (pintype "passive"))
    )
    (net (code "204") (name "unconnected-(AM6442-MCU_SPI0__D0-PadE7)") (class "Default")
      (node (ref "AM6442") (pin "E7") (pinfunction "MCU_SPI0__D0_E7") (pintype "passive"))
    )
    (net (code "205") (name "unconnected-(AM6442-MCU_SPI0__D1-PadB6)") (class "Default")
      (node (ref "AM6442") (pin "B6") (pinfunction "MCU_SPI0__D1_B6") (pintype "passive"))
    )
    (net (code "206") (name "unconnected-(AM6442-MCU_SPI1__CLK-PadD7)") (class "Default")
      (node (ref "AM6442") (pin "D7") (pinfunction "MCU_SPI1__CLK_D7") (pintype "passive"))
    )
    (net (code "207") (name "unconnected-(AM6442-MCU_SPI1__CS0-PadA7)") (class "Default")
      (node (ref "AM6442") (pin "A7") (pinfunction "MCU_SPI1__CS0_A7") (pintype "passive"))
    )
    (net (code "208") (name "unconnected-(AM6442-MCU_SPI1__D0-PadC7)") (class "Default")
      (node (ref "AM6442") (pin "C7") (pinfunction "MCU_SPI1__D0_C7") (pintype "passive"))
    )
    (net (code "209") (name "unconnected-(AM6442-MCU_SPI1__D1-PadC8)") (class "Default")
      (node (ref "AM6442") (pin "C8") (pinfunction "MCU_SPI1__D1_C8") (pintype "passive"))
    )
    (net (code "210") (name "unconnected-(AM6442-MCU_UART0__CTSN-PadD8)") (class "Default")
      (node (ref "AM6442") (pin "D8") (pinfunction "MCU_UART0__CTSN_D8") (pintype "passive"))
    )
    (net (code "211") (name "unconnected-(AM6442-MCU_UART0__RTSN-PadE8)") (class "Default")
      (node (ref "AM6442") (pin "E8") (pinfunction "MCU_UART0__RTSN_E8") (pintype "passive"))
    )
    (net (code "212") (name "unconnected-(AM6442-MCU_UART0__RXD-PadA9)") (class "Default")
      (node (ref "AM6442") (pin "A9") (pinfunction "MCU_UART0__RXD_A9") (pintype "passive"))
    )
    (net (code "213") (name "unconnected-(AM6442-MCU_UART0__TXD-PadA8)") (class "Default")
      (node (ref "AM6442") (pin "A8") (pinfunction "MCU_UART0__TXD_A8") (pintype "passive"))
    )
    (net (code "214") (name "unconnected-(AM6442-MCU_UART1__CTSN-PadB8)") (class "Default")
      (node (ref "AM6442") (pin "B8") (pinfunction "MCU_UART1__CTSN_B8") (pintype "passive"))
    )
    (net (code "215") (name "unconnected-(AM6442-MCU_UART1__RTSN-PadB9)") (class "Default")
      (node (ref "AM6442") (pin "B9") (pinfunction "MCU_UART1__RTSN_B9") (pintype "passive"))
    )
    (net (code "216") (name "unconnected-(AM6442-MCU_UART1__RXD-PadC9)") (class "Default")
      (node (ref "AM6442") (pin "C9") (pinfunction "MCU_UART1__RXD_C9") (pintype "passive"))
    )
    (net (code "217") (name "unconnected-(AM6442-MCU_UART1__TXD-PadD9)") (class "Default")
      (node (ref "AM6442") (pin "D9") (pinfunction "MCU_UART1__TXD_D9") (pintype "passive"))
    )
    (net (code "218") (name "unconnected-(AM6442-MMC0_CALPAD-PadF18)") (class "Default")
      (node (ref "AM6442") (pin "F18") (pinfunction "MMC0_CALPAD_F18") (pintype "passive"))
    )
    (net (code "219") (name "unconnected-(AM6442-MMC0_DAT4-PadH17)") (class "Default")
      (node (ref "AM6442") (pin "H17") (pinfunction "MMC0_DAT4_H17") (pintype "passive"))
    )
    (net (code "220") (name "unconnected-(AM6442-MMC0_DAT5-PadH19)") (class "Default")
      (node (ref "AM6442") (pin "H19") (pinfunction "MMC0_DAT5_H19") (pintype "passive"))
    )
    (net (code "221") (name "unconnected-(AM6442-MMC0_DAT6-PadH18)") (class "Default")
      (node (ref "AM6442") (pin "H18") (pinfunction "MMC0_DAT6_H18") (pintype "passive"))
    )
    (net (code "222") (name "unconnected-(AM6442-MMC0_DAT7-PadG17)") (class "Default")
      (node (ref "AM6442") (pin "G17") (pinfunction "MMC0_DAT7_G17") (pintype "passive"))
    )
    (net (code "223") (name "unconnected-(AM6442-MMC0_DS-PadG19)") (class "Default")
      (node (ref "AM6442") (pin "G19") (pinfunction "MMC0_DS_G19") (pintype "passive"))
    )
    (net (code "224") (name "unconnected-(AM6442-MMC1_CLK-PadL20)") (class "Default")
      (node (ref "AM6442") (pin "L20") (pinfunction "MMC1_CLK_L20") (pintype "passive"))
    )
    (net (code "225") (name "unconnected-(AM6442-MMC1_CMD-PadJ19)") (class "Default")
      (node (ref "AM6442") (pin "J19") (pinfunction "MMC1_CMD_J19") (pintype "passive"))
    )
    (net (code "226") (name "unconnected-(AM6442-MMC1_DAT0-PadK21)") (class "Default")
      (node (ref "AM6442") (pin "K21") (pinfunction "MMC1_DAT0_K21") (pintype "passive"))
    )
    (net (code "227") (name "unconnected-(AM6442-MMC1_DAT1-PadL21)") (class "Default")
      (node (ref "AM6442") (pin "L21") (pinfunction "MMC1_DAT1_L21") (pintype "passive"))
    )
    (net (code "228") (name "unconnected-(AM6442-MMC1_DAT2-PadK19)") (class "Default")
      (node (ref "AM6442") (pin "K19") (pinfunction "MMC1_DAT2_K19") (pintype "passive"))
    )
    (net (code "229") (name "unconnected-(AM6442-MMC1_DAT3-PadK18)") (class "Default")
      (node (ref "AM6442") (pin "K18") (pinfunction "MMC1_DAT3_K18") (pintype "passive"))
    )
    (net (code "230") (name "unconnected-(AM6442-MMC1_SDCD-PadD19)") (class "Default")
      (node (ref "AM6442") (pin "D19") (pinfunction "MMC1_SDCD_D19") (pintype "passive"))
    )
    (net (code "231") (name "unconnected-(AM6442-MMC1_SDWP-PadC20)") (class "Default")
      (node (ref "AM6442") (pin "C20") (pinfunction "MMC1_SDWP_C20") (pintype "passive"))
    )
    (net (code "232") (name "unconnected-(AM6442-OSPI0_CLK-PadN20)") (class "Default")
      (node (ref "AM6442") (pin "N20") (pinfunction "OSPI0_CLK_N20") (pintype "passive"))
    )
    (net (code "233") (name "unconnected-(AM6442-OSPI0_CSN0-PadL19)") (class "Default")
      (node (ref "AM6442") (pin "L19") (pinfunction "OSPI0_CSN0_L19") (pintype "passive"))
    )
    (net (code "234") (name "unconnected-(AM6442-OSPI0_CSN1-PadL18)") (class "Default")
      (node (ref "AM6442") (pin "L18") (pinfunction "OSPI0_CSN1_L18") (pintype "passive"))
    )
    (net (code "235") (name "unconnected-(AM6442-OSPI0_CSN2-PadK17)") (class "Default")
      (node (ref "AM6442") (pin "K17") (pinfunction "OSPI0_CSN2_K17") (pintype "passive"))
    )
    (net (code "236") (name "unconnected-(AM6442-OSPI0_CSN3-PadL17)") (class "Default")
      (node (ref "AM6442") (pin "L17") (pinfunction "OSPI0_CSN3_L17") (pintype "passive"))
    )
    (net (code "237") (name "unconnected-(AM6442-OSPI0_D0-PadM19)") (class "Default")
      (node (ref "AM6442") (pin "M19") (pinfunction "OSPI0_D0_M19") (pintype "passive"))
    )
    (net (code "238") (name "unconnected-(AM6442-OSPI0_D1-PadM18)") (class "Default")
      (node (ref "AM6442") (pin "M18") (pinfunction "OSPI0_D1_M18") (pintype "passive"))
    )
    (net (code "239") (name "unconnected-(AM6442-OSPI0_D2-PadM20)") (class "Default")
      (node (ref "AM6442") (pin "M20") (pinfunction "OSPI0_D2_M20") (pintype "passive"))
    )
    (net (code "240") (name "unconnected-(AM6442-OSPI0_D3-PadM21)") (class "Default")
      (node (ref "AM6442") (pin "M21") (pinfunction "OSPI0_D3_M21") (pintype "passive"))
    )
    (net (code "241") (name "unconnected-(AM6442-OSPI0_D4-PadP21)") (class "Default")
      (node (ref "AM6442") (pin "P21") (pinfunction "OSPI0_D4_P21") (pintype "passive"))
    )
    (net (code "242") (name "unconnected-(AM6442-OSPI0_D5-PadP20)") (class "Default")
      (node (ref "AM6442") (pin "P20") (pinfunction "OSPI0_D5_P20") (pintype "passive"))
    )
    (net (code "243") (name "unconnected-(AM6442-OSPI0_D6-PadN18)") (class "Default")
      (node (ref "AM6442") (pin "N18") (pinfunction "OSPI0_D6_N18") (pintype "passive"))
    )
    (net (code "244") (name "unconnected-(AM6442-OSPI0_D7-PadM17)") (class "Default")
      (node (ref "AM6442") (pin "M17") (pinfunction "OSPI0_D7_M17") (pintype "passive"))
    )
    (net (code "245") (name "unconnected-(AM6442-OSPI0_DQS-PadN19)") (class "Default")
      (node (ref "AM6442") (pin "N19") (pinfunction "OSPI0_DQS_N19") (pintype "passive"))
    )
    (net (code "246") (name "unconnected-(AM6442-OSPI0_LBCLKO-PadN21)") (class "Default")
      (node (ref "AM6442") (pin "N21") (pinfunction "OSPI0_LBCLKO_N21") (pintype "passive"))
    )
    (net (code "247") (name "unconnected-(AM6442-PORZ_OUT-PadE17)") (class "Default")
      (node (ref "AM6442") (pin "E17") (pinfunction "PORZ_OUT_E17") (pintype "passive+no_connect"))
    )
    (net (code "248") (name "unconnected-(AM6442-PRG0_PRU0__GPO0-PadY1)") (class "Default")
      (node (ref "AM6442") (pin "Y1") (pinfunction "PRG0_PRU0__GPO0_Y1") (pintype "passive"))
    )
    (net (code "249") (name "unconnected-(AM6442-PRG0_PRU0__GPO1-PadR4)") (class "Default")
      (node (ref "AM6442") (pin "R4") (pinfunction "PRG0_PRU0__GPO1_R4") (pintype "passive"))
    )
    (net (code "250") (name "unconnected-(AM6442-PRG0_PRU0__GPO2-PadU2)") (class "Default")
      (node (ref "AM6442") (pin "U2") (pinfunction "PRG0_PRU0__GPO2_U2") (pintype "passive"))
    )
    (net (code "251") (name "unconnected-(AM6442-PRG0_PRU0__GPO3-PadV2)") (class "Default")
      (node (ref "AM6442") (pin "V2") (pinfunction "PRG0_PRU0__GPO3_V2") (pintype "passive"))
    )
    (net (code "252") (name "unconnected-(AM6442-PRG0_PRU0__GPO4-PadAA2)") (class "Default")
      (node (ref "AM6442") (pin "AA2") (pinfunction "PRG0_PRU0__GPO4_AA2") (pintype "passive"))
    )
    (net (code "253") (name "unconnected-(AM6442-PRG0_PRU0__GPO5-PadR3)") (class "Default")
      (node (ref "AM6442") (pin "R3") (pinfunction "PRG0_PRU0__GPO5_R3") (pintype "passive"))
    )
    (net (code "254") (name "unconnected-(AM6442-PRG0_PRU0__GPO6-PadT3)") (class "Default")
      (node (ref "AM6442") (pin "T3") (pinfunction "PRG0_PRU0__GPO6_T3") (pintype "passive"))
    )
    (net (code "255") (name "unconnected-(AM6442-PRG0_PRU0__GPO7-PadT1)") (class "Default")
      (node (ref "AM6442") (pin "T1") (pinfunction "PRG0_PRU0__GPO7_T1") (pintype "passive"))
    )
    (net (code "256") (name "unconnected-(AM6442-PRG0_PRU0__GPO8-PadT2)") (class "Default")
      (node (ref "AM6442") (pin "T2") (pinfunction "PRG0_PRU0__GPO8_T2") (pintype "passive"))
    )
    (net (code "257") (name "unconnected-(AM6442-PRG0_PRU0__GPO9-PadW6)") (class "Default")
      (node (ref "AM6442") (pin "W6") (pinfunction "PRG0_PRU0__GPO9_W6") (pintype "passive"))
    )
    (net (code "258") (name "unconnected-(AM6442-PRG0_PRU0__GPO10-PadAA5)") (class "Default")
      (node (ref "AM6442") (pin "AA5") (pinfunction "PRG0_PRU0__GPO10_AA5") (pintype "passive"))
    )
    (net (code "259") (name "unconnected-(AM6442-PRG0_PRU0__GPO11-PadY3)") (class "Default")
      (node (ref "AM6442") (pin "Y3") (pinfunction "PRG0_PRU0__GPO11_Y3") (pintype "passive"))
    )
    (net (code "260") (name "unconnected-(AM6442-PRG0_PRU0__GPO12-PadAA3)") (class "Default")
      (node (ref "AM6442") (pin "AA3") (pinfunction "PRG0_PRU0__GPO12_AA3") (pintype "passive"))
    )
    (net (code "261") (name "unconnected-(AM6442-PRG0_PRU0__GPO13-PadR6)") (class "Default")
      (node (ref "AM6442") (pin "R6") (pinfunction "PRG0_PRU0__GPO13_R6") (pintype "passive"))
    )
    (net (code "262") (name "unconnected-(AM6442-PRG0_PRU0__GPO14-PadV4)") (class "Default")
      (node (ref "AM6442") (pin "V4") (pinfunction "PRG0_PRU0__GPO14_V4") (pintype "passive"))
    )
    (net (code "263") (name "unconnected-(AM6442-PRG0_PRU0__GPO15-PadT5)") (class "Default")
      (node (ref "AM6442") (pin "T5") (pinfunction "PRG0_PRU0__GPO15_T5") (pintype "passive"))
    )
    (net (code "264") (name "unconnected-(AM6442-PRG0_PRU0__GPO16-PadU4)") (class "Default")
      (node (ref "AM6442") (pin "U4") (pinfunction "PRG0_PRU0__GPO16_U4") (pintype "passive"))
    )
    (net (code "265") (name "unconnected-(AM6442-PRG0_PRU0__GPO17-PadU1)") (class "Default")
      (node (ref "AM6442") (pin "U1") (pinfunction "PRG0_PRU0__GPO17_U1") (pintype "passive"))
    )
    (net (code "266") (name "unconnected-(AM6442-PRG0_PRU0__GPO18-PadV1)") (class "Default")
      (node (ref "AM6442") (pin "V1") (pinfunction "PRG0_PRU0__GPO18_V1") (pintype "passive"))
    )
    (net (code "267") (name "unconnected-(AM6442-PRG0_PRU0__GPO19-PadW1)") (class "Default")
      (node (ref "AM6442") (pin "W1") (pinfunction "PRG0_PRU0__GPO19_W1") (pintype "passive"))
    )
    (net (code "268") (name "unconnected-(AM6442-PRG0_PRU1__GPO0-PadY2)") (class "Default")
      (node (ref "AM6442") (pin "Y2") (pinfunction "PRG0_PRU1__GPO0_Y2") (pintype "passive"))
    )
    (net (code "269") (name "unconnected-(AM6442-PRG0_PRU1__GPO1-PadW2)") (class "Default")
      (node (ref "AM6442") (pin "W2") (pinfunction "PRG0_PRU1__GPO1_W2") (pintype "passive"))
    )
    (net (code "270") (name "unconnected-(AM6442-PRG0_PRU1__GPO2-PadV3)") (class "Default")
      (node (ref "AM6442") (pin "V3") (pinfunction "PRG0_PRU1__GPO2_V3") (pintype "passive"))
    )
    (net (code "271") (name "unconnected-(AM6442-PRG0_PRU1__GPO3-PadT4)") (class "Default")
      (node (ref "AM6442") (pin "T4") (pinfunction "PRG0_PRU1__GPO3_T4") (pintype "passive"))
    )
    (net (code "272") (name "unconnected-(AM6442-PRG0_PRU1__GPO4-PadW3)") (class "Default")
      (node (ref "AM6442") (pin "W3") (pinfunction "PRG0_PRU1__GPO4_W3") (pintype "passive"))
    )
    (net (code "273") (name "unconnected-(AM6442-PRG0_PRU1__GPO5-PadP4)") (class "Default")
      (node (ref "AM6442") (pin "P4") (pinfunction "PRG0_PRU1__GPO5_P4") (pintype "passive"))
    )
    (net (code "274") (name "unconnected-(AM6442-PRG0_PRU1__GPO6-PadR5)") (class "Default")
      (node (ref "AM6442") (pin "R5") (pinfunction "PRG0_PRU1__GPO6_R5") (pintype "passive"))
    )
    (net (code "275") (name "unconnected-(AM6442-PRG0_PRU1__GPO7-PadW5)") (class "Default")
      (node (ref "AM6442") (pin "W5") (pinfunction "PRG0_PRU1__GPO7_W5") (pintype "passive"))
    )
    (net (code "276") (name "unconnected-(AM6442-PRG0_PRU1__GPO8-PadR1)") (class "Default")
      (node (ref "AM6442") (pin "R1") (pinfunction "PRG0_PRU1__GPO8_R1") (pintype "passive"))
    )
    (net (code "277") (name "unconnected-(AM6442-PRG0_PRU1__GPO9-PadY5)") (class "Default")
      (node (ref "AM6442") (pin "Y5") (pinfunction "PRG0_PRU1__GPO9_Y5") (pintype "passive"))
    )
    (net (code "278") (name "unconnected-(AM6442-PRG0_PRU1__GPO10-PadV6)") (class "Default")
      (node (ref "AM6442") (pin "V6") (pinfunction "PRG0_PRU1__GPO10_V6") (pintype "passive"))
    )
    (net (code "279") (name "unconnected-(AM6442-PRG0_PRU1__GPO11-PadW4)") (class "Default")
      (node (ref "AM6442") (pin "W4") (pinfunction "PRG0_PRU1__GPO11_W4") (pintype "passive"))
    )
    (net (code "280") (name "unconnected-(AM6442-PRG0_PRU1__GPO12-PadY4)") (class "Default")
      (node (ref "AM6442") (pin "Y4") (pinfunction "PRG0_PRU1__GPO12_Y4") (pintype "passive"))
    )
    (net (code "281") (name "unconnected-(AM6442-PRG0_PRU1__GPO13-PadT6)") (class "Default")
      (node (ref "AM6442") (pin "T6") (pinfunction "PRG0_PRU1__GPO13_T6") (pintype "passive"))
    )
    (net (code "282") (name "unconnected-(AM6442-PRG0_PRU1__GPO14-PadU6)") (class "Default")
      (node (ref "AM6442") (pin "U6") (pinfunction "PRG0_PRU1__GPO14_U6") (pintype "passive"))
    )
    (net (code "283") (name "unconnected-(AM6442-PRG0_PRU1__GPO15-PadU5)") (class "Default")
      (node (ref "AM6442") (pin "U5") (pinfunction "PRG0_PRU1__GPO15_U5") (pintype "passive"))
    )
    (net (code "284") (name "unconnected-(AM6442-PRG0_PRU1__GPO16-PadAA4)") (class "Default")
      (node (ref "AM6442") (pin "AA4") (pinfunction "PRG0_PRU1__GPO16_AA4") (pintype "passive"))
    )
    (net (code "285") (name "unconnected-(AM6442-PRG0_PRU1__GPO17-PadV5)") (class "Default")
      (node (ref "AM6442") (pin "V5") (pinfunction "PRG0_PRU1__GPO17_V5") (pintype "passive"))
    )
    (net (code "286") (name "unconnected-(AM6442-PRG0_PRU1__GPO18-PadP5)") (class "Default")
      (node (ref "AM6442") (pin "P5") (pinfunction "PRG0_PRU1__GPO18_P5") (pintype "passive"))
    )
    (net (code "287") (name "unconnected-(AM6442-PRG0_PRU1__GPO19-PadR2)") (class "Default")
      (node (ref "AM6442") (pin "R2") (pinfunction "PRG0_PRU1__GPO19_R2") (pintype "passive"))
    )
    (net (code "288") (name "unconnected-(AM6442-PRG0__MDIO__MDC-PadP3)") (class "Default")
      (node (ref "AM6442") (pin "P3") (pinfunction "PRG0__MDIO__MDC_P3") (pintype "passive"))
    )
    (net (code "289") (name "unconnected-(AM6442-PRG0__MDIO__MDI-PadP2)") (class "Default")
      (node (ref "AM6442") (pin "P2") (pinfunction "PRG0__MDIO__MDI_P2") (pintype "passive"))
    )
    (net (code "290") (name "unconnected-(AM6442-PRG1_PRU0__GPO0-PadY7)") (class "Default")
      (node (ref "AM6442") (pin "Y7") (pinfunction "PRG1_PRU0__GPO0_Y7") (pintype "passive"))
    )
    (net (code "291") (name "unconnected-(AM6442-PRG1_PRU0__GPO1-PadU8)") (class "Default")
      (node (ref "AM6442") (pin "U8") (pinfunction "PRG1_PRU0__GPO1_U8") (pintype "passive"))
    )
    (net (code "292") (name "unconnected-(AM6442-PRG1_PRU0__GPO2-PadW8)") (class "Default")
      (node (ref "AM6442") (pin "W8") (pinfunction "PRG1_PRU0__GPO2_W8") (pintype "passive"))
    )
    (net (code "293") (name "unconnected-(AM6442-PRG1_PRU0__GPO3-PadV8)") (class "Default")
      (node (ref "AM6442") (pin "V8") (pinfunction "PRG1_PRU0__GPO3_V8") (pintype "passive"))
    )
    (net (code "294") (name "unconnected-(AM6442-PRG1_PRU0__GPO4-PadY8)") (class "Default")
      (node (ref "AM6442") (pin "Y8") (pinfunction "PRG1_PRU0__GPO4_Y8") (pintype "passive"))
    )
    (net (code "295") (name "unconnected-(AM6442-PRG1_PRU0__GPO6-PadAA7)") (class "Default")
      (node (ref "AM6442") (pin "AA7") (pinfunction "PRG1_PRU0__GPO6_AA7") (pintype "passive"))
    )
    (net (code "296") (name "unconnected-(AM6442-PRG1_PRU0__GPO7-PadU13)") (class "Default")
      (node (ref "AM6442") (pin "U13") (pinfunction "PRG1_PRU0__GPO7_U13") (pintype "passive"))
    )
    (net (code "297") (name "unconnected-(AM6442-PRG1_PRU0__GPO11-PadAA8)") (class "Default")
      (node (ref "AM6442") (pin "AA8") (pinfunction "PRG1_PRU0__GPO11_AA8") (pintype "passive"))
    )
    (net (code "298") (name "unconnected-(AM6442-PRG1_PRU0__GPO12-PadU9)") (class "Default")
      (node (ref "AM6442") (pin "U9") (pinfunction "PRG1_PRU0__GPO12_U9") (pintype "passive"))
    )
    (net (code "299") (name "unconnected-(AM6442-PRG1_PRU0__GPO13-PadW9)") (class "Default")
      (node (ref "AM6442") (pin "W9") (pinfunction "PRG1_PRU0__GPO13_W9") (pintype "passive"))
    )
    (net (code "300") (name "unconnected-(AM6442-PRG1_PRU0__GPO14-PadAA9)") (class "Default")
      (node (ref "AM6442") (pin "AA9") (pinfunction "PRG1_PRU0__GPO14_AA9") (pintype "passive"))
    )
    (net (code "301") (name "unconnected-(AM6442-PRG1_PRU0__GPO15-PadY9)") (class "Default")
      (node (ref "AM6442") (pin "Y9") (pinfunction "PRG1_PRU0__GPO15_Y9") (pintype "passive"))
    )
    (net (code "302") (name "unconnected-(AM6442-PRG1_PRU0__GPO16-PadV9)") (class "Default")
      (node (ref "AM6442") (pin "V9") (pinfunction "PRG1_PRU0__GPO16_V9") (pintype "passive"))
    )
    (net (code "303") (name "unconnected-(AM6442-PRG1_PRU0__GPO17-PadU7)") (class "Default")
      (node (ref "AM6442") (pin "U7") (pinfunction "PRG1_PRU0__GPO17_U7") (pintype "passive"))
    )
    (net (code "304") (name "unconnected-(AM6442-PRG1_PRU0__GPO18-PadV7)") (class "Default")
      (node (ref "AM6442") (pin "V7") (pinfunction "PRG1_PRU0__GPO18_V7") (pintype "passive"))
    )
    (net (code "305") (name "unconnected-(AM6442-PRG1_PRU0__GPO19-PadW7)") (class "Default")
      (node (ref "AM6442") (pin "W7") (pinfunction "PRG1_PRU0__GPO19_W7") (pintype "passive"))
    )
    (net (code "306") (name "unconnected-(AM6442-PRG1_PRU1__GPO0-PadW11)") (class "Default")
      (node (ref "AM6442") (pin "W11") (pinfunction "PRG1_PRU1__GPO0_W11") (pintype "passive"))
    )
    (net (code "307") (name "unconnected-(AM6442-PRG1_PRU1__GPO1-PadV11)") (class "Default")
      (node (ref "AM6442") (pin "V11") (pinfunction "PRG1_PRU1__GPO1_V11") (pintype "passive"))
    )
    (net (code "308") (name "unconnected-(AM6442-PRG1_PRU1__GPO2-PadAA12)") (class "Default")
      (node (ref "AM6442") (pin "AA12") (pinfunction "PRG1_PRU1__GPO2_AA12") (pintype "passive"))
    )
    (net (code "309") (name "unconnected-(AM6442-PRG1_PRU1__GPO3-PadY12)") (class "Default")
      (node (ref "AM6442") (pin "Y12") (pinfunction "PRG1_PRU1__GPO3_Y12") (pintype "passive"))
    )
    (net (code "310") (name "unconnected-(AM6442-PRG1_PRU1__GPO4-PadW12)") (class "Default")
      (node (ref "AM6442") (pin "W12") (pinfunction "PRG1_PRU1__GPO4_W12") (pintype "passive"))
    )
    (net (code "311") (name "unconnected-(AM6442-PRG1_PRU1__GPO6-PadU11)") (class "Default")
      (node (ref "AM6442") (pin "U11") (pinfunction "PRG1_PRU1__GPO6_U11") (pintype "passive"))
    )
    (net (code "312") (name "unconnected-(AM6442-PRG1_PRU1__GPO11-PadAA10)") (class "Default")
      (node (ref "AM6442") (pin "AA10") (pinfunction "PRG1_PRU1__GPO11_AA10") (pintype "passive"))
    )
    (net (code "313") (name "unconnected-(AM6442-PRG1_PRU1__GPO12-PadV10)") (class "Default")
      (node (ref "AM6442") (pin "V10") (pinfunction "PRG1_PRU1__GPO12_V10") (pintype "passive"))
    )
    (net (code "314") (name "unconnected-(AM6442-PRG1_PRU1__GPO13-PadU10)") (class "Default")
      (node (ref "AM6442") (pin "U10") (pinfunction "PRG1_PRU1__GPO13_U10") (pintype "passive"))
    )
    (net (code "315") (name "unconnected-(AM6442-PRG1_PRU1__GPO14-PadAA11)") (class "Default")
      (node (ref "AM6442") (pin "AA11") (pinfunction "PRG1_PRU1__GPO14_AA11") (pintype "passive"))
    )
    (net (code "316") (name "unconnected-(AM6442-PRG1_PRU1__GPO15-PadY11)") (class "Default")
      (node (ref "AM6442") (pin "Y11") (pinfunction "PRG1_PRU1__GPO15_Y11") (pintype "passive"))
    )
    (net (code "317") (name "unconnected-(AM6442-PRG1_PRU1__GPO16-PadY10)") (class "Default")
      (node (ref "AM6442") (pin "Y10") (pinfunction "PRG1_PRU1__GPO16_Y10") (pintype "passive"))
    )
    (net (code "318") (name "unconnected-(AM6442-RESETSTA_TZ-PadF16)") (class "Default")
      (node (ref "AM6442") (pin "F16") (pinfunction "RESETSTA_TZ_F16") (pintype "passive+no_connect"))
    )
    (net (code "319") (name "unconnected-(AM6442-RSVD0-PadH16)") (class "Default")
      (node (ref "AM6442") (pin "H16") (pinfunction "RSVD0_H16") (pintype "passive+no_connect"))
    )
    (net (code "320") (name "unconnected-(AM6442-RSVD1-PadD21)") (class "Default")
      (node (ref "AM6442") (pin "D21") (pinfunction "RSVD1_D21") (pintype "passive+no_connect"))
    )
    (net (code "321") (name "unconnected-(AM6442-RSVD2-PadG13)") (class "Default")
      (node (ref "AM6442") (pin "G13") (pinfunction "RSVD2_G13") (pintype "passive+no_connect"))
    )
    (net (code "322") (name "unconnected-(AM6442-RSVD3-PadF17)") (class "Default")
      (node (ref "AM6442") (pin "F17") (pinfunction "RSVD3_F17") (pintype "passive+no_connect"))
    )
    (net (code "323") (name "unconnected-(AM6442-RSVD4-PadW15)") (class "Default")
      (node (ref "AM6442") (pin "W15") (pinfunction "RSVD4_W15") (pintype "passive+no_connect"))
    )
    (net (code "324") (name "unconnected-(AM6442-RSVD5-PadV16)") (class "Default")
      (node (ref "AM6442") (pin "V16") (pinfunction "RSVD5_V16") (pintype "passive+no_connect"))
    )
    (net (code "325") (name "unconnected-(AM6442-RSVD6-PadK2)") (class "Default")
      (node (ref "AM6442") (pin "K2") (pinfunction "RSVD6_K2") (pintype "passive+no_connect"))
    )
    (net (code "326") (name "unconnected-(AM6442-RSVD7-PadK1)") (class "Default")
      (node (ref "AM6442") (pin "K1") (pinfunction "RSVD7_K1") (pintype "passive+no_connect"))
    )
    (net (code "327") (name "unconnected-(AM6442-RSVD8-PadF12)") (class "Default")
      (node (ref "AM6442") (pin "F12") (pinfunction "RSVD8_F12") (pintype "passive+no_connect"))
    )
    (net (code "328") (name "unconnected-(AM6442-SERDES0_REFCLK0N-PadW16)") (class "Default")
      (node (ref "AM6442") (pin "W16") (pinfunction "SERDES0_REFCLK0N_W16") (pintype "passive"))
    )
    (net (code "329") (name "unconnected-(AM6442-SERDES0_REFCLKOP-PadW17)") (class "Default")
      (node (ref "AM6442") (pin "W17") (pinfunction "SERDES0_REFCLKOP_W17") (pintype "passive"))
    )
    (net (code "330") (name "unconnected-(AM6442-SERDES0__REXT-PadT13)") (class "Default")
      (node (ref "AM6442") (pin "T13") (pinfunction "SERDES0__REXT_T13") (pintype "passive"))
    )
    (net (code "331") (name "unconnected-(AM6442-SERDES0__RX0_N-PadY15)") (class "Default")
      (node (ref "AM6442") (pin "Y15") (pinfunction "SERDES0__RX0_N_Y15") (pintype "passive"))
    )
    (net (code "332") (name "unconnected-(AM6442-SERDES0__RX0_P-PadY16)") (class "Default")
      (node (ref "AM6442") (pin "Y16") (pinfunction "SERDES0__RX0_P_Y16") (pintype "passive"))
    )
    (net (code "333") (name "unconnected-(AM6442-SERDES0__TX0_N-PadAA16)") (class "Default")
      (node (ref "AM6442") (pin "AA16") (pinfunction "SERDES0__TX0_N_AA16") (pintype "passive"))
    )
    (net (code "334") (name "unconnected-(AM6442-SERDES0__TX0_P-PadAA17)") (class "Default")
      (node (ref "AM6442") (pin "AA17") (pinfunction "SERDES0__TX0_P_AA17") (pintype "passive"))
    )
    (net (code "335") (name "unconnected-(AM6442-SPI0_CLK-PadD13)") (class "Default")
      (node (ref "AM6442") (pin "D13") (pinfunction "SPI0_CLK_D13") (pintype "passive"))
    )
    (net (code "336") (name "unconnected-(AM6442-SPI0_CS0-PadD12)") (class "Default")
      (node (ref "AM6442") (pin "D12") (pinfunction "SPI0_CS0_D12") (pintype "passive"))
    )
    (net (code "337") (name "unconnected-(AM6442-SPI0_CS1-PadC13)") (class "Default")
      (node (ref "AM6442") (pin "C13") (pinfunction "SPI0_CS1_C13") (pintype "passive"))
    )
    (net (code "338") (name "unconnected-(AM6442-SPI0_D0-PadA13)") (class "Default")
      (node (ref "AM6442") (pin "A13") (pinfunction "SPI0_D0_A13") (pintype "passive"))
    )
    (net (code "339") (name "unconnected-(AM6442-SPI0_D1-PadA14)") (class "Default")
      (node (ref "AM6442") (pin "A14") (pinfunction "SPI0_D1_A14") (pintype "passive"))
    )
    (net (code "340") (name "unconnected-(AM6442-SPI1_CLK-PadC14)") (class "Default")
      (node (ref "AM6442") (pin "C14") (pinfunction "SPI1_CLK_C14") (pintype "passive"))
    )
    (net (code "341") (name "unconnected-(AM6442-SPI1_CS0-PadB14)") (class "Default")
      (node (ref "AM6442") (pin "B14") (pinfunction "SPI1_CS0_B14") (pintype "passive"))
    )
    (net (code "342") (name "unconnected-(AM6442-SPI1_CS1-PadD14)") (class "Default")
      (node (ref "AM6442") (pin "D14") (pinfunction "SPI1_CS1_D14") (pintype "passive"))
    )
    (net (code "343") (name "unconnected-(AM6442-SPI1_D0-PadB15)") (class "Default")
      (node (ref "AM6442") (pin "B15") (pinfunction "SPI1_D0_B15") (pintype "passive"))
    )
    (net (code "344") (name "unconnected-(AM6442-SPI1_D1-PadA15)") (class "Default")
      (node (ref "AM6442") (pin "A15") (pinfunction "SPI1_D1_A15") (pintype "passive"))
    )
    (net (code "345") (name "unconnected-(AM6442-UART0_RXD-PadD15)") (class "Default")
      (node (ref "AM6442") (pin "D15") (pinfunction "UART0_RXD_D15") (pintype "passive"))
    )
    (net (code "346") (name "unconnected-(AM6442-UART0_TXD-PadC16)") (class "Default")
      (node (ref "AM6442") (pin "C16") (pinfunction "UART0_TXD_C16") (pintype "passive"))
    )
    (net (code "347") (name "unconnected-(AM6442-UART0__CTSN-PadB16)") (class "Default")
      (node (ref "AM6442") (pin "B16") (pinfunction "UART0__CTSN_B16") (pintype "passive"))
    )
    (net (code "348") (name "unconnected-(AM6442-UART0__RTS-PadA16)") (class "Default")
      (node (ref "AM6442") (pin "A16") (pinfunction "UART0__RTS_A16") (pintype "passive"))
    )
    (net (code "349") (name "unconnected-(AM6442-UART1_RXD-PadE15)") (class "Default")
      (node (ref "AM6442") (pin "E15") (pinfunction "UART1_RXD_E15") (pintype "passive"))
    )
    (net (code "350") (name "unconnected-(AM6442-UART1_TXD-PadE14)") (class "Default")
      (node (ref "AM6442") (pin "E14") (pinfunction "UART1_TXD_E14") (pintype "passive"))
    )
    (net (code "351") (name "unconnected-(AM6442-UART1__CTSN-PadD16)") (class "Default")
      (node (ref "AM6442") (pin "D16") (pinfunction "UART1__CTSN_D16") (pintype "passive"))
    )
    (net (code "352") (name "unconnected-(AM6442-UART1__RTS-PadE16)") (class "Default")
      (node (ref "AM6442") (pin "E16") (pinfunction "UART1__RTS_E16") (pintype "passive"))
    )
    (net (code "353") (name "unconnected-(AM6442-USB0_DM-PadAA20)") (class "Default")
      (node (ref "AM6442") (pin "AA20") (pinfunction "USB0_DM_AA20") (pintype "passive"))
    )
    (net (code "354") (name "unconnected-(AM6442-USB0_DP-PadAA19)") (class "Default")
      (node (ref "AM6442") (pin "AA19") (pinfunction "USB0_DP_AA19") (pintype "passive"))
    )
    (net (code "355") (name "unconnected-(AM6442-USB0_DRVVBUS-PadE19)") (class "Default")
      (node (ref "AM6442") (pin "E19") (pinfunction "USB0_DRVVBUS_E19") (pintype "passive"))
    )
    (net (code "356") (name "unconnected-(AM6442-USB0_ID-PadU16)") (class "Default")
      (node (ref "AM6442") (pin "U16") (pinfunction "USB0_ID_U16") (pintype "passive"))
    )
    (net (code "357") (name "unconnected-(AM6442-USB0_RCALIB-PadU17)") (class "Default")
      (node (ref "AM6442") (pin "U17") (pinfunction "USB0_RCALIB_U17") (pintype "passive"))
    )
    (net (code "358") (name "unconnected-(AM6442-USB0_VBUS-PadT14)") (class "Default")
      (node (ref "AM6442") (pin "T14") (pinfunction "USB0_VBUS_T14") (pintype "passive"))
    )
    (net (code "359") (name "unconnected-(AM6442-VMON_1P8_MCU-PadK16)") (class "Default")
      (node (ref "AM6442") (pin "K16") (pinfunction "VMON_1P8_MCU_K16") (pintype "passive+no_connect"))
    )
    (net (code "360") (name "unconnected-(AM6442-VMON_1P8_SOC-PadE12)") (class "Default")
      (node (ref "AM6442") (pin "E12") (pinfunction "VMON_1P8_SOC_E12") (pintype "passive+no_connect"))
    )
    (net (code "361") (name "unconnected-(AM6442-VMON_3P3_MCU-PadF13)") (class "Default")
      (node (ref "AM6442") (pin "F13") (pinfunction "VMON_3P3_MCU_F13") (pintype "passive+no_connect"))
    )
    (net (code "362") (name "unconnected-(AM6442-VMON_3P3_SOC-PadF14)") (class "Default")
      (node (ref "AM6442") (pin "F14") (pinfunction "VMON_3P3_SOC_F14") (pintype "passive+no_connect"))
    )
    (net (code "363") (name "unconnected-(AM6442-VMON_VSYS-PadK10)") (class "Default")
      (node (ref "AM6442") (pin "K10") (pinfunction "VMON_VSYS_K10") (pintype "passive+no_connect"))
    )
    (net (code "364") (name "unconnected-(AM6442-VPP-PadG15)") (class "Default")
      (node (ref "AM6442") (pin "G15") (pinfunction "VPP_G15") (pintype "passive+no_connect"))
    )
    (net (code "365") (name "unconnected-(BergStrip 1-Pin-Pad1)") (class "Default")
      (node (ref "BergStrip 1") (pin "1") (pinfunction "Pin_1") (pintype "passive"))
    )
    (net (code "366") (name "unconnected-(BergStrip 2-Pin-Pad1)") (class "Default")
      (node (ref "BergStrip 2") (pin "1") (pinfunction "Pin_1") (pintype "passive"))
    )
    (net (code "367") (name "unconnected-(BergStrip 3-Pin-Pad1)") (class "Default")
      (node (ref "BergStrip 3") (pin "1") (pinfunction "Pin_1") (pintype "passive"))
    )
    (net (code "368") (name "unconnected-(BergStrip 4-Pin-Pad1)") (class "Default")
      (node (ref "BergStrip 4") (pin "1") (pinfunction "Pin_1") (pintype "passive"))
    )
    (net (code "369") (name "unconnected-(BergStrip 5-Pin-Pad1)") (class "Default")
      (node (ref "BergStrip 5") (pin "1") (pinfunction "Pin_1") (pintype "passive"))
    )
    (net (code "370") (name "unconnected-(BergStrip 6-Pin-Pad1)") (class "Default")
      (node (ref "BergStrip 6") (pin "1") (pinfunction "Pin_1") (pintype "passive"))
    )
    (net (code "371") (name "unconnected-(BergStrip 7-Pin-Pad1)") (class "Default")
      (node (ref "BergStrip 7") (pin "1") (pinfunction "Pin_1") (pintype "passive"))
    )
    (net (code "372") (name "unconnected-(BergStrip 8-Pin-Pad1)") (class "Default")
      (node (ref "BergStrip 8") (pin "1") (pinfunction "Pin_1") (pintype "passive"))
    )
    (net (code "373") (name "unconnected-(BergStrip 9-Pin-Pad1)") (class "Default")
      (node (ref "BergStrip 9") (pin "1") (pinfunction "Pin_1") (pintype "passive"))
    )
    (net (code "374") (name "unconnected-(BergStrip 10-Pin-Pad1)") (class "Default")
      (node (ref "BergStrip 10") (pin "1") (pinfunction "Pin_1") (pintype "passive"))
    )
    (net (code "375") (name "unconnected-(BergStrip 11-Pin-Pad1)") (class "Default")
      (node (ref "BergStrip 11") (pin "1") (pinfunction "Pin_1") (pintype "passive"))
    )
    (net (code "376") (name "unconnected-(BergStrip 12-Pin-Pad1)") (class "Default")
      (node (ref "BergStrip 12") (pin "1") (pinfunction "Pin_1") (pintype "passive"))
    )
    (net (code "377") (name "unconnected-(BergStrip 13-Pin-Pad1)") (class "Default")
      (node (ref "BergStrip 13") (pin "1") (pinfunction "Pin_1") (pintype "passive"))
    )
    (net (code "378") (name "unconnected-(BergStrip 14-Pin-Pad1)") (class "Default")
      (node (ref "BergStrip 14") (pin "1") (pinfunction "Pin_1") (pintype "passive"))
    )
    (net (code "379") (name "unconnected-(BergStrip 15-Pin-Pad1)") (class "Default")
      (node (ref "BergStrip 15") (pin "1") (pinfunction "Pin_1") (pintype "passive"))
    )
    (net (code "380") (name "unconnected-(BergStrip 16-Pin-Pad1)") (class "Default")
      (node (ref "BergStrip 16") (pin "1") (pinfunction "Pin_1") (pintype "passive"))
    )
    (net (code "381") (name "unconnected-(BergStrip 17-Pin-Pad1)") (class "Default")
      (node (ref "BergStrip 17") (pin "1") (pinfunction "Pin_1") (pintype "passive"))
    )
    (net (code "382") (name "unconnected-(BergStrip 18-Pin-Pad1)") (class "Default")
      (node (ref "BergStrip 18") (pin "1") (pinfunction "Pin_1") (pintype "passive"))
    )
    (net (code "383") (name "unconnected-(BergStrip 19-Pin-Pad1)") (class "Default")
      (node (ref "BergStrip 19") (pin "1") (pinfunction "Pin_1") (pintype "passive"))
    )
    (net (code "384") (name "unconnected-(BergStrip 20-Pin-Pad1)") (class "Default")
      (node (ref "BergStrip 20") (pin "1") (pinfunction "Pin_1") (pintype "passive"))
    )
    (net (code "385") (name "unconnected-(BergStrip 21-Pin-Pad1)") (class "Default")
      (node (ref "BergStrip 21") (pin "1") (pinfunction "Pin_1") (pintype "passive"))
    )
    (net (code "386") (name "unconnected-(BergStrip 22-Pin-Pad1)") (class "Default")
      (node (ref "BergStrip 22") (pin "1") (pinfunction "Pin_1") (pintype "passive"))
    )
    (net (code "387") (name "unconnected-(BergStrip 23-Pin-Pad1)") (class "Default")
      (node (ref "BergStrip 23") (pin "1") (pinfunction "Pin_1") (pintype "passive"))
    )
    (net (code "388") (name "unconnected-(BergStrip 24-Pin-Pad1)") (class "Default")
      (node (ref "BergStrip 24") (pin "1") (pinfunction "Pin_1") (pintype "passive"))
    )
    (net (code "389") (name "unconnected-(BergStrip 25-Pin-Pad1)") (class "Default")
      (node (ref "BergStrip 25") (pin "1") (pinfunction "Pin_1") (pintype "passive"))
    )
    (net (code "390") (name "unconnected-(BergStrip 26-Pin-Pad1)") (class "Default")
      (node (ref "BergStrip 26") (pin "1") (pinfunction "Pin_1") (pintype "passive"))
    )
    (net (code "391") (name "unconnected-(BergStrip 27-Pin-Pad1)") (class "Default")
      (node (ref "BergStrip 27") (pin "1") (pinfunction "Pin_1") (pintype "passive"))
    )
    (net (code "392") (name "unconnected-(BergStrip 28-Pin-Pad1)") (class "Default")
      (node (ref "BergStrip 28") (pin "1") (pinfunction "Pin_1") (pintype "passive"))
    )
    (net (code "393") (name "unconnected-(BergStrip 29-Pin-Pad1)") (class "Default")
      (node (ref "BergStrip 29") (pin "1") (pinfunction "Pin_1") (pintype "passive"))
    )
    (net (code "394") (name "unconnected-(BergStrip 30-Pin-Pad1)") (class "Default")
      (node (ref "BergStrip 30") (pin "1") (pinfunction "Pin_1") (pintype "passive"))
    )
    (net (code "395") (name "unconnected-(BergStrip 31-Pin-Pad1)") (class "Default")
      (node (ref "BergStrip 31") (pin "1") (pinfunction "Pin_1") (pintype "passive"))
    )
    (net (code "396") (name "unconnected-(BergStrip 32-Pin-Pad1)") (class "Default")
      (node (ref "BergStrip 32") (pin "1") (pinfunction "Pin_1") (pintype "passive"))
    )
    (net (code "397") (name "unconnected-(BergStrip 33-Pin-Pad1)") (class "Default")
      (node (ref "BergStrip 33") (pin "1") (pinfunction "Pin_1") (pintype "passive"))
    )
    (net (code "398") (name "unconnected-(BergStrip 34-Pin-Pad1)") (class "Default")
      (node (ref "BergStrip 34") (pin "1") (pinfunction "Pin_1") (pintype "passive"))
    )
    (net (code "399") (name "unconnected-(BergStrip 35-Pin-Pad1)") (class "Default")
      (node (ref "BergStrip 35") (pin "1") (pinfunction "Pin_1") (pintype "passive"))
    )
    (net (code "400") (name "unconnected-(BergStrip 36-Pin-Pad1)") (class "Default")
      (node (ref "BergStrip 36") (pin "1") (pinfunction "Pin_1") (pintype "passive"))
    )
    (net (code "401") (name "unconnected-(BergStrip 37-Pin-Pad1)") (class "Default")
      (node (ref "BergStrip 37") (pin "1") (pinfunction "Pin_1") (pintype "passive"))
    )
    (net (code "402") (name "unconnected-(BergStrip 38-Pin-Pad1)") (class "Default")
      (node (ref "BergStrip 38") (pin "1") (pinfunction "Pin_1") (pintype "passive"))
    )
    (net (code "403") (name "unconnected-(BergStrip 39-Pin-Pad1)") (class "Default")
      (node (ref "BergStrip 39") (pin "1") (pinfunction "Pin_1") (pintype "passive"))
    )
    (net (code "404") (name "unconnected-(BergStrip 40-Pin-Pad1)") (class "Default")
      (node (ref "BergStrip 40") (pin "1") (pinfunction "Pin_1") (pintype "passive"))
    )
    (net (code "405") (name "unconnected-(BergStrip 41-Pin-Pad1)") (class "Default")
      (node (ref "BergStrip 41") (pin "1") (pinfunction "Pin_1") (pintype "passive"))
    )
    (net (code "406") (name "unconnected-(BergStrip 42-Pin-Pad1)") (class "Default")
      (node (ref "BergStrip 42") (pin "1") (pinfunction "Pin_1") (pintype "passive"))
    )
    (net (code "407") (name "unconnected-(BergStrip 43-Pin-Pad1)") (class "Default")
      (node (ref "BergStrip 43") (pin "1") (pinfunction "Pin_1") (pintype "passive"))
    )
    (net (code "408") (name "unconnected-(BergStrip 44-Pin-Pad1)") (class "Default")
      (node (ref "BergStrip 44") (pin "1") (pinfunction "Pin_1") (pintype "passive"))
    )
    (net (code "409") (name "unconnected-(BergStrip 45-Pin-Pad1)") (class "Default")
      (node (ref "BergStrip 45") (pin "1") (pinfunction "Pin_1") (pintype "passive"))
    )
    (net (code "410") (name "unconnected-(BergStrip 46-Pin-Pad1)") (class "Default")
      (node (ref "BergStrip 46") (pin "1") (pinfunction "Pin_1") (pintype "passive"))
    )
    (net (code "411") (name "unconnected-(BergStrip 47-Pin-Pad1)") (class "Default")
      (node (ref "BergStrip 47") (pin "1") (pinfunction "Pin_1") (pintype "passive"))
    )
    (net (code "412") (name "unconnected-(BergStrip 48-Pin-Pad1)") (class "Default")
      (node (ref "BergStrip 48") (pin "1") (pinfunction "Pin_1") (pintype "passive"))
    )
    (net (code "413") (name "unconnected-(BergStrip 49-Pin-Pad1)") (class "Default")
      (node (ref "BergStrip 49") (pin "1") (pinfunction "Pin_1") (pintype "passive"))
    )
    (net (code "414") (name "unconnected-(BergStrip 50-Pin-Pad1)") (class "Default")
      (node (ref "BergStrip 50") (pin "1") (pinfunction "Pin_1") (pintype "passive"))
    )
    (net (code "415") (name "unconnected-(BergStrip 51-Pin-Pad1)") (class "Default")
      (node (ref "BergStrip 51") (pin "1") (pinfunction "Pin_1") (pintype "passive"))
    )
    (net (code "416") (name "unconnected-(BergStrip 52-Pin-Pad1)") (class "Default")
      (node (ref "BergStrip 52") (pin "1") (pinfunction "Pin_1") (pintype "passive"))
    )
    (net (code "417") (name "unconnected-(BergStrip 53-Pin-Pad1)") (class "Default")
      (node (ref "BergStrip 53") (pin "1") (pinfunction "Pin_1") (pintype "passive"))
    )
    (net (code "418") (name "unconnected-(BergStrip 54-Pin-Pad1)") (class "Default")
      (node (ref "BergStrip 54") (pin "1") (pinfunction "Pin_1") (pintype "passive"))
    )
    (net (code "419") (name "unconnected-(BergStrip 55-Pin-Pad1)") (class "Default")
      (node (ref "BergStrip 55") (pin "1") (pinfunction "Pin_1") (pintype "passive"))
    )
    (net (code "420") (name "unconnected-(BergStrip 56-Pin-Pad1)") (class "Default")
      (node (ref "BergStrip 56") (pin "1") (pinfunction "Pin_1") (pintype "passive"))
    )
    (net (code "421") (name "unconnected-(BergStrip 57-Pin-Pad1)") (class "Default")
      (node (ref "BergStrip 57") (pin "1") (pinfunction "Pin_1") (pintype "passive"))
    )
    (net (code "422") (name "unconnected-(BergStrip 58-Pin-Pad1)") (class "Default")
      (node (ref "BergStrip 58") (pin "1") (pinfunction "Pin_1") (pintype "passive"))
    )
    (net (code "423") (name "unconnected-(BergStrip 59-Pin-Pad1)") (class "Default")
      (node (ref "BergStrip 59") (pin "1") (pinfunction "Pin_1") (pintype "passive"))
    )
    (net (code "424") (name "unconnected-(BergStrip 60-Pin-Pad1)") (class "Default")
      (node (ref "BergStrip 60") (pin "1") (pinfunction "Pin_1") (pintype "passive"))
    )
    (net (code "425") (name "unconnected-(BergStrip 61-Pin-Pad1)") (class "Default")
      (node (ref "BergStrip 61") (pin "1") (pinfunction "Pin_1") (pintype "passive"))
    )
    (net (code "426") (name "unconnected-(BergStrip 62-Pin-Pad1)") (class "Default")
      (node (ref "BergStrip 62") (pin "1") (pinfunction "Pin_1") (pintype "passive"))
    )
    (net (code "427") (name "unconnected-(BergStrip 63-Pin-Pad1)") (class "Default")
      (node (ref "BergStrip 63") (pin "1") (pinfunction "Pin_1") (pintype "passive"))
    )
    (net (code "428") (name "unconnected-(BergStrip 64-Pin-Pad1)") (class "Default")
      (node (ref "BergStrip 64") (pin "1") (pinfunction "Pin_1") (pintype "passive"))
    )
    (net (code "429") (name "unconnected-(BergStrip 65-Pin-Pad1)") (class "Default")
      (node (ref "BergStrip 65") (pin "1") (pinfunction "Pin_1") (pintype "passive"))
    )
    (net (code "430") (name "unconnected-(BergStrip 66-Pin-Pad1)") (class "Default")
      (node (ref "BergStrip 66") (pin "1") (pinfunction "Pin_1") (pintype "passive"))
    )
    (net (code "431") (name "unconnected-(BergStrip 67-Pin-Pad1)") (class "Default")
      (node (ref "BergStrip 67") (pin "1") (pinfunction "Pin_1") (pintype "passive"))
    )
    (net (code "432") (name "unconnected-(BergStrip 68-Pin-Pad1)") (class "Default")
      (node (ref "BergStrip 68") (pin "1") (pinfunction "Pin_1") (pintype "passive"))
    )
    (net (code "433") (name "unconnected-(BergStrip 69-Pin-Pad1)") (class "Default")
      (node (ref "BergStrip 69") (pin "1") (pinfunction "Pin_1") (pintype "passive"))
    )
    (net (code "434") (name "unconnected-(BergStrip 70-Pin-Pad1)") (class "Default")
      (node (ref "BergStrip 70") (pin "1") (pinfunction "Pin_1") (pintype "passive"))
    )
    (net (code "435") (name "unconnected-(BergStrip 71-Pin-Pad1)") (class "Default")
      (node (ref "BergStrip 71") (pin "1") (pinfunction "Pin_1") (pintype "passive"))
    )
    (net (code "436") (name "unconnected-(BergStrip 72-Pin-Pad1)") (class "Default")
      (node (ref "BergStrip 72") (pin "1") (pinfunction "Pin_1") (pintype "passive"))
    )
    (net (code "437") (name "unconnected-(BergStrip 73-Pin-Pad1)") (class "Default")
      (node (ref "BergStrip 73") (pin "1") (pinfunction "Pin_1") (pintype "passive"))
    )
    (net (code "438") (name "unconnected-(BergStrip 74-Pin-Pad1)") (class "Default")
      (node (ref "BergStrip 74") (pin "1") (pinfunction "Pin_1") (pintype "passive"))
    )
    (net (code "439") (name "unconnected-(BergStrip 75-Pin-Pad1)") (class "Default")
      (node (ref "BergStrip 75") (pin "1") (pinfunction "Pin_1") (pintype "passive"))
    )
    (net (code "440") (name "unconnected-(BergStrip 76-Pin-Pad1)") (class "Default")
      (node (ref "BergStrip 76") (pin "1") (pinfunction "Pin_1") (pintype "passive"))
    )
    (net (code "441") (name "unconnected-(BergStrip 77-Pin-Pad1)") (class "Default")
      (node (ref "BergStrip 77") (pin "1") (pinfunction "Pin_1") (pintype "passive"))
    )
    (net (code "442") (name "unconnected-(BergStrip 78-Pin-Pad1)") (class "Default")
      (node (ref "BergStrip 78") (pin "1") (pinfunction "Pin_1") (pintype "passive"))
    )
    (net (code "443") (name "unconnected-(BergStrip 79-Pin-Pad1)") (class "Default")
      (node (ref "BergStrip 79") (pin "1") (pinfunction "Pin_1") (pintype "passive"))
    )
    (net (code "444") (name "unconnected-(BergStrip 80-Pin-Pad1)") (class "Default")
      (node (ref "BergStrip 80") (pin "1") (pinfunction "Pin_1") (pintype "passive"))
    )
    (net (code "445") (name "unconnected-(BergStrip 81-Pin-Pad1)") (class "Default")
      (node (ref "BergStrip 81") (pin "1") (pinfunction "Pin_1") (pintype "passive"))
    )
    (net (code "446") (name "unconnected-(BergStrip 82-Pin-Pad1)") (class "Default")
      (node (ref "BergStrip 82") (pin "1") (pinfunction "Pin_1") (pintype "passive"))
    )
    (net (code "447") (name "unconnected-(BergStrip 83-Pin-Pad1)") (class "Default")
      (node (ref "BergStrip 83") (pin "1") (pinfunction "Pin_1") (pintype "passive"))
    )
    (net (code "448") (name "unconnected-(BergStrip 84-Pin-Pad1)") (class "Default")
      (node (ref "BergStrip 84") (pin "1") (pinfunction "Pin_1") (pintype "passive"))
    )
    (net (code "449") (name "unconnected-(BergStrip 85-Pin-Pad1)") (class "Default")
      (node (ref "BergStrip 85") (pin "1") (pinfunction "Pin_1") (pintype "passive"))
    )
    (net (code "450") (name "unconnected-(BergStrip 86-Pin-Pad1)") (class "Default")
      (node (ref "BergStrip 86") (pin "1") (pinfunction "Pin_1") (pintype "passive"))
    )
    (net (code "451") (name "unconnected-(BergStrip 87-Pin-Pad1)") (class "Default")
      (node (ref "BergStrip 87") (pin "1") (pinfunction "Pin_1") (pintype "passive"))
    )
    (net (code "452") (name "unconnected-(BergStrip 88-Pin-Pad1)") (class "Default")
      (node (ref "BergStrip 88") (pin "1") (pinfunction "Pin_1") (pintype "passive"))
    )
    (net (code "453") (name "unconnected-(BergStrip 89-Pin-Pad1)") (class "Default")
      (node (ref "BergStrip 89") (pin "1") (pinfunction "Pin_1") (pintype "passive"))
    )
    (net (code "454") (name "unconnected-(BergStrip 90-Pin-Pad1)") (class "Default")
      (node (ref "BergStrip 90") (pin "1") (pinfunction "Pin_1") (pintype "passive"))
    )
    (net (code "455") (name "unconnected-(BergStrip 91-Pin-Pad1)") (class "Default")
      (node (ref "BergStrip 91") (pin "1") (pinfunction "Pin_1") (pintype "passive"))
    )
    (net (code "456") (name "unconnected-(BergStrip 92-Pin-Pad1)") (class "Default")
      (node (ref "BergStrip 92") (pin "1") (pinfunction "Pin_1") (pintype "passive"))
    )
    (net (code "457") (name "unconnected-(BergStrip 93-Pin-Pad1)") (class "Default")
      (node (ref "BergStrip 93") (pin "1") (pinfunction "Pin_1") (pintype "passive"))
    )
    (net (code "458") (name "unconnected-(BergStrip 94-Pin-Pad1)") (class "Default")
      (node (ref "BergStrip 94") (pin "1") (pinfunction "Pin_1") (pintype "passive"))
    )
    (net (code "459") (name "unconnected-(BergStrip 95-Pin-Pad1)") (class "Default")
      (node (ref "BergStrip 95") (pin "1") (pinfunction "Pin_1") (pintype "passive"))
    )
    (net (code "460") (name "unconnected-(BergStrip 96-Pin-Pad1)") (class "Default")
      (node (ref "BergStrip 96") (pin "1") (pinfunction "Pin_1") (pintype "passive"))
    )
    (net (code "461") (name "unconnected-(BergStrip 97-Pin-Pad1)") (class "Default")
      (node (ref "BergStrip 97") (pin "1") (pinfunction "Pin_1") (pintype "passive"))
    )
    (net (code "462") (name "unconnected-(BergStrip 98-Pin-Pad1)") (class "Default")
      (node (ref "BergStrip 98") (pin "1") (pinfunction "Pin_1") (pintype "passive"))
    )
    (net (code "463") (name "unconnected-(BergStrip 99-Pin-Pad1)") (class "Default")
      (node (ref "BergStrip 99") (pin "1") (pinfunction "Pin_1") (pintype "passive"))
    )
    (net (code "464") (name "unconnected-(BergStrip 100-Pin-Pad1)") (class "Default")
      (node (ref "BergStrip 100") (pin "1") (pinfunction "Pin_1") (pintype "passive"))
    )
    (net (code "465") (name "unconnected-(BergStrip 101-Pin-Pad1)") (class "Default")
      (node (ref "BergStrip 101") (pin "1") (pinfunction "Pin_1") (pintype "passive"))
    )
    (net (code "466") (name "unconnected-(BergStrip 102-Pin-Pad1)") (class "Default")
      (node (ref "BergStrip 102") (pin "1") (pinfunction "Pin_1") (pintype "passive"))
    )
    (net (code "467") (name "unconnected-(BergStrip 103-Pin-Pad1)") (class "Default")
      (node (ref "BergStrip 103") (pin "1") (pinfunction "Pin_1") (pintype "passive"))
    )
    (net (code "468") (name "unconnected-(BergStrip 104-Pin-Pad1)") (class "Default")
      (node (ref "BergStrip 104") (pin "1") (pinfunction "Pin_1") (pintype "passive"))
    )
    (net (code "469") (name "unconnected-(BergStrip 105-Pin-Pad1)") (class "Default")
      (node (ref "BergStrip 105") (pin "1") (pinfunction "Pin_1") (pintype "passive"))
    )
    (net (code "470") (name "unconnected-(BergStrip 106-Pin-Pad1)") (class "Default")
      (node (ref "BergStrip 106") (pin "1") (pinfunction "Pin_1") (pintype "passive"))
    )
    (net (code "471") (name "unconnected-(BergStrip 107-Pin-Pad1)") (class "Default")
      (node (ref "BergStrip 107") (pin "1") (pinfunction "Pin_1") (pintype "passive"))
    )
    (net (code "472") (name "unconnected-(BergStrip 108-Pin-Pad1)") (class "Default")
      (node (ref "BergStrip 108") (pin "1") (pinfunction "Pin_1") (pintype "passive"))
    )
    (net (code "473") (name "unconnected-(BergStrip 109-Pin-Pad1)") (class "Default")
      (node (ref "BergStrip 109") (pin "1") (pinfunction "Pin_1") (pintype "passive"))
    )
    (net (code "474") (name "unconnected-(BergStrip 110-Pin-Pad1)") (class "Default")
      (node (ref "BergStrip 110") (pin "1") (pinfunction "Pin_1") (pintype "passive"))
    )
    (net (code "475") (name "unconnected-(BergStrip 111-Pin-Pad1)") (class "Default")
      (node (ref "BergStrip 111") (pin "1") (pinfunction "Pin_1") (pintype "passive"))
    )
    (net (code "476") (name "unconnected-(BergStrip 112-Pin-Pad1)") (class "Default")
      (node (ref "BergStrip 112") (pin "1") (pinfunction "Pin_1") (pintype "passive"))
    )
    (net (code "477") (name "unconnected-(BergStrip 113-Pin-Pad1)") (class "Default")
      (node (ref "BergStrip 113") (pin "1") (pinfunction "Pin_1") (pintype "passive"))
    )
    (net (code "478") (name "unconnected-(BergStrip 114-Pin-Pad1)") (class "Default")
      (node (ref "BergStrip 114") (pin "1") (pinfunction "Pin_1") (pintype "passive"))
    )
    (net (code "479") (name "unconnected-(BergStrip 115-Pin-Pad1)") (class "Default")
      (node (ref "BergStrip 115") (pin "1") (pinfunction "Pin_1") (pintype "passive"))
    )
    (net (code "480") (name "unconnected-(BergStrip 116-Pin-Pad1)") (class "Default")
      (node (ref "BergStrip 116") (pin "1") (pinfunction "Pin_1") (pintype "passive"))
    )
    (net (code "481") (name "unconnected-(BergStrip 117-Pin-Pad1)") (class "Default")
      (node (ref "BergStrip 117") (pin "1") (pinfunction "Pin_1") (pintype "passive"))
    )
    (net (code "482") (name "unconnected-(BergStrip 118-Pin-Pad1)") (class "Default")
      (node (ref "BergStrip 118") (pin "1") (pinfunction "Pin_1") (pintype "passive"))
    )
    (net (code "483") (name "unconnected-(BergStrip 119-Pin-Pad1)") (class "Default")
      (node (ref "BergStrip 119") (pin "1") (pinfunction "Pin_1") (pintype "passive"))
    )
    (net (code "484") (name "unconnected-(BergStrip 120-Pin-Pad1)") (class "Default")
      (node (ref "BergStrip 120") (pin "1") (pinfunction "Pin_1") (pintype "passive"))
    )
    (net (code "485") (name "unconnected-(BergStrip 121-Pin-Pad1)") (class "Default")
      (node (ref "BergStrip 121") (pin "1") (pinfunction "Pin_1") (pintype "passive"))
    )
    (net (code "486") (name "unconnected-(BergStrip 122-Pin-Pad1)") (class "Default")
      (node (ref "BergStrip 122") (pin "1") (pinfunction "Pin_1") (pintype "passive"))
    )
    (net (code "487") (name "unconnected-(BergStrip 123-Pin-Pad1)") (class "Default")
      (node (ref "BergStrip 123") (pin "1") (pinfunction "Pin_1") (pintype "passive"))
    )
    (net (code "488") (name "unconnected-(BergStrip 124-Pin-Pad1)") (class "Default")
      (node (ref "BergStrip 124") (pin "1") (pinfunction "Pin_1") (pintype "passive"))
    )
    (net (code "489") (name "unconnected-(BergStrip 125-Pin-Pad1)") (class "Default")
      (node (ref "BergStrip 125") (pin "1") (pinfunction "Pin_1") (pintype "passive"))
    )
    (net (code "490") (name "unconnected-(BergStrip 126-Pin-Pad1)") (class "Default")
      (node (ref "BergStrip 126") (pin "1") (pinfunction "Pin_1") (pintype "passive"))
    )
    (net (code "491") (name "unconnected-(BergStrip 127-Pin-Pad1)") (class "Default")
      (node (ref "BergStrip 127") (pin "1") (pinfunction "Pin_1") (pintype "passive"))
    )
    (net (code "492") (name "unconnected-(BergStrip 128-Pin-Pad1)") (class "Default")
      (node (ref "BergStrip 128") (pin "1") (pinfunction "Pin_1") (pintype "passive"))
    )
    (net (code "493") (name "unconnected-(BergStrip 129-Pin-Pad1)") (class "Default")
      (node (ref "BergStrip 129") (pin "1") (pinfunction "Pin_1") (pintype "passive"))
    )
    (net (code "494") (name "unconnected-(BergStrip 130-Pin-Pad1)") (class "Default")
      (node (ref "BergStrip 130") (pin "1") (pinfunction "Pin_1") (pintype "passive"))
    )
    (net (code "495") (name "unconnected-(BergStrip 131-Pin-Pad1)") (class "Default")
      (node (ref "BergStrip 131") (pin "1") (pinfunction "Pin_1") (pintype "passive"))
    )
    (net (code "496") (name "unconnected-(BergStrip 132-Pin-Pad1)") (class "Default")
      (node (ref "BergStrip 132") (pin "1") (pinfunction "Pin_1") (pintype "passive"))
    )
    (net (code "497") (name "unconnected-(BergStrip 133-Pin-Pad1)") (class "Default")
      (node (ref "BergStrip 133") (pin "1") (pinfunction "Pin_1") (pintype "passive"))
    )
    (net (code "498") (name "unconnected-(BergStrip 134-Pin-Pad1)") (class "Default")
      (node (ref "BergStrip 134") (pin "1") (pinfunction "Pin_1") (pintype "passive"))
    )
    (net (code "499") (name "unconnected-(BergStrip 135-Pin-Pad1)") (class "Default")
      (node (ref "BergStrip 135") (pin "1") (pinfunction "Pin_1") (pintype "passive"))
    )
    (net (code "500") (name "unconnected-(BergStrip 136-Pin-Pad1)") (class "Default")
      (node (ref "BergStrip 136") (pin "1") (pinfunction "Pin_1") (pintype "passive"))
    )
    (net (code "501") (name "unconnected-(BergStrip 137-Pin-Pad1)") (class "Default")
      (node (ref "BergStrip 137") (pin "1") (pinfunction "Pin_1") (pintype "passive"))
    )
    (net (code "502") (name "unconnected-(BergStrip 138-Pin-Pad1)") (class "Default")
      (node (ref "BergStrip 138") (pin "1") (pinfunction "Pin_1") (pintype "passive"))
    )
    (net (code "503") (name "unconnected-(BergStrip 139-Pin-Pad1)") (class "Default")
      (node (ref "BergStrip 139") (pin "1") (pinfunction "Pin_1") (pintype "passive"))
    )
    (net (code "504") (name "unconnected-(BergStrip 140-Pin-Pad1)") (class "Default")
      (node (ref "BergStrip 140") (pin "1") (pinfunction "Pin_1") (pintype "passive"))
    )
    (net (code "505") (name "unconnected-(BergStrip 141-Pin-Pad1)") (class "Default")
      (node (ref "BergStrip 141") (pin "1") (pinfunction "Pin_1") (pintype "passive"))
    )
    (net (code "506") (name "unconnected-(BergStrip 142-Pin-Pad1)") (class "Default")
      (node (ref "BergStrip 142") (pin "1") (pinfunction "Pin_1") (pintype "passive"))
    )
    (net (code "507") (name "unconnected-(BergStrip 143-Pin-Pad1)") (class "Default")
      (node (ref "BergStrip 143") (pin "1") (pinfunction "Pin_1") (pintype "passive"))
    )
    (net (code "508") (name "unconnected-(BergStrip 144-Pin-Pad1)") (class "Default")
      (node (ref "BergStrip 144") (pin "1") (pinfunction "Pin_1") (pintype "passive"))
    )
    (net (code "509") (name "unconnected-(BergStrip 145-Pin-Pad1)") (class "Default")
      (node (ref "BergStrip 145") (pin "1") (pinfunction "Pin_1") (pintype "passive"))
    )
    (net (code "510") (name "unconnected-(BergStrip 146-Pin-Pad1)") (class "Default")
      (node (ref "BergStrip 146") (pin "1") (pinfunction "Pin_1") (pintype "passive"))
    )
    (net (code "511") (name "unconnected-(BergStrip 147-Pin-Pad1)") (class "Default")
      (node (ref "BergStrip 147") (pin "1") (pinfunction "Pin_1") (pintype "passive"))
    )
    (net (code "512") (name "unconnected-(BergStrip 148-Pin-Pad1)") (class "Default")
      (node (ref "BergStrip 148") (pin "1") (pinfunction "Pin_1") (pintype "passive"))
    )
    (net (code "513") (name "unconnected-(BergStrip 149-Pin-Pad1)") (class "Default")
      (node (ref "BergStrip 149") (pin "1") (pinfunction "Pin_1") (pintype "passive"))
    )
    (net (code "514") (name "unconnected-(BergStrip 150-Pin-Pad1)") (class "Default")
      (node (ref "BergStrip 150") (pin "1") (pinfunction "Pin_1") (pintype "passive"))
    )
    (net (code "515") (name "unconnected-(BergStrip 151-Pin-Pad1)") (class "Default")
      (node (ref "BergStrip 151") (pin "1") (pinfunction "Pin_1") (pintype "passive"))
    )
    (net (code "516") (name "unconnected-(BergStrip 152-Pin-Pad1)") (class "Default")
      (node (ref "BergStrip 152") (pin "1") (pinfunction "Pin_1") (pintype "passive"))
    )
    (net (code "517") (name "unconnected-(BergStrip 153-Pin-Pad1)") (class "Default")
      (node (ref "BergStrip 153") (pin "1") (pinfunction "Pin_1") (pintype "passive"))
    )
    (net (code "518") (name "unconnected-(BergStrip 154-Pin-Pad1)") (class "Default")
      (node (ref "BergStrip 154") (pin "1") (pinfunction "Pin_1") (pintype "passive"))
    )
    (net (code "519") (name "unconnected-(BergStrip 155-Pin-Pad1)") (class "Default")
      (node (ref "BergStrip 155") (pin "1") (pinfunction "Pin_1") (pintype "passive"))
    )
    (net (code "520") (name "unconnected-(BergStrip 156-Pin-Pad1)") (class "Default")
      (node (ref "BergStrip 156") (pin "1") (pinfunction "Pin_1") (pintype "passive"))
    )
    (net (code "521") (name "unconnected-(BergStrip 157-Pin-Pad1)") (class "Default")
      (node (ref "BergStrip 157") (pin "1") (pinfunction "Pin_1") (pintype "passive"))
    )
    (net (code "522") (name "unconnected-(BergStrip 158-Pin-Pad1)") (class "Default")
      (node (ref "BergStrip 158") (pin "1") (pinfunction "Pin_1") (pintype "passive"))
    )
    (net (code "523") (name "unconnected-(BergStrip 159-Pin-Pad1)") (class "Default")
      (node (ref "BergStrip 159") (pin "1") (pinfunction "Pin_1") (pintype "passive"))
    )
    (net (code "524") (name "unconnected-(BergStrip 160-Pin-Pad1)") (class "Default")
      (node (ref "BergStrip 160") (pin "1") (pinfunction "Pin_1") (pintype "passive"))
    )
    (net (code "525") (name "unconnected-(BergStrip 161-Pin-Pad1)") (class "Default")
      (node (ref "BergStrip 161") (pin "1") (pinfunction "Pin_1") (pintype "passive"))
    )
    (net (code "526") (name "unconnected-(BergStrip 162-Pin-Pad1)") (class "Default")
      (node (ref "BergStrip 162") (pin "1") (pinfunction "Pin_1") (pintype "passive"))
    )
    (net (code "527") (name "unconnected-(BergStrip 163-Pin-Pad1)") (class "Default")
      (node (ref "BergStrip 163") (pin "1") (pinfunction "Pin_1") (pintype "passive"))
    )
    (net (code "528") (name "unconnected-(BergStrip 164-Pin-Pad1)") (class "Default")
      (node (ref "BergStrip 164") (pin "1") (pinfunction "Pin_1") (pintype "passive"))
    )
    (net (code "529") (name "unconnected-(BergStrip 165-Pin-Pad1)") (class "Default")
      (node (ref "BergStrip 165") (pin "1") (pinfunction "Pin_1") (pintype "passive"))
    )
    (net (code "530") (name "unconnected-(BergStrip 166-Pin-Pad1)") (class "Default")
      (node (ref "BergStrip 166") (pin "1") (pinfunction "Pin_1") (pintype "passive"))
    )
    (net (code "531") (name "unconnected-(BergStrip 167-Pin-Pad1)") (class "Default")
      (node (ref "BergStrip 167") (pin "1") (pinfunction "Pin_1") (pintype "passive"))
    )
    (net (code "532") (name "unconnected-(BergStrip 168-Pin-Pad1)") (class "Default")
      (node (ref "BergStrip 168") (pin "1") (pinfunction "Pin_1") (pintype "passive"))
    )
    (net (code "533") (name "unconnected-(BergStrip 169-Pin-Pad1)") (class "Default")
      (node (ref "BergStrip 169") (pin "1") (pinfunction "Pin_1") (pintype "passive"))
    )
    (net (code "534") (name "unconnected-(BergStrip 170-Pin-Pad1)") (class "Default")
      (node (ref "BergStrip 170") (pin "1") (pinfunction "Pin_1") (pintype "passive"))
    )
    (net (code "535") (name "unconnected-(BergStrip 171-Pin-Pad1)") (class "Default")
      (node (ref "BergStrip 171") (pin "1") (pinfunction "Pin_1") (pintype "passive"))
    )
    (net (code "536") (name "unconnected-(BergStrip 172-Pin-Pad1)") (class "Default")
      (node (ref "BergStrip 172") (pin "1") (pinfunction "Pin_1") (pintype "passive"))
    )
    (net (code "537") (name "unconnected-(BergStrip 173-Pin-Pad1)") (class "Default")
      (node (ref "BergStrip 173") (pin "1") (pinfunction "Pin_1") (pintype "passive"))
    )
    (net (code "538") (name "unconnected-(BergStrip 174-Pin-Pad1)") (class "Default")
      (node (ref "BergStrip 174") (pin "1") (pinfunction "Pin_1") (pintype "passive"))
    )
    (net (code "539") (name "unconnected-(BergStrip 175-Pin-Pad1)") (class "Default")
      (node (ref "BergStrip 175") (pin "1") (pinfunction "Pin_1") (pintype "passive"))
    )
    (net (code "540") (name "unconnected-(BergStrip 176-Pin-Pad1)") (class "Default")
      (node (ref "BergStrip 176") (pin "1") (pinfunction "Pin_1") (pintype "passive"))
    )
    (net (code "541") (name "unconnected-(BergStrip 177-Pin-Pad1)") (class "Default")
      (node (ref "BergStrip 177") (pin "1") (pinfunction "Pin_1") (pintype "passive"))
    )
    (net (code "542") (name "unconnected-(BergStrip 178-Pin-Pad1)") (class "Default")
      (node (ref "BergStrip 178") (pin "1") (pinfunction "Pin_1") (pintype "passive"))
    )
    (net (code "543") (name "unconnected-(BergStrip 179-Pin-Pad1)") (class "Default")
      (node (ref "BergStrip 179") (pin "1") (pinfunction "Pin_1") (pintype "passive"))
    )
    (net (code "544") (name "unconnected-(BergStrip 180-Pin-Pad1)") (class "Default")
      (node (ref "BergStrip 180") (pin "1") (pinfunction "Pin_1") (pintype "passive"))
    )
    (net (code "545") (name "unconnected-(BergStrip 181-Pin-Pad1)") (class "Default")
      (node (ref "BergStrip 181") (pin "1") (pinfunction "Pin_1") (pintype "passive"))
    )
    (net (code "546") (name "unconnected-(BergStrip 182-Pin-Pad1)") (class "Default")
      (node (ref "BergStrip 182") (pin "1") (pinfunction "Pin_1") (pintype "passive"))
    )
    (net (code "547") (name "unconnected-(BergStrip 183-Pin-Pad1)") (class "Default")
      (node (ref "BergStrip 183") (pin "1") (pinfunction "Pin_1") (pintype "passive"))
    )
    (net (code "548") (name "unconnected-(BergStrip 184-Pin-Pad1)") (class "Default")
      (node (ref "BergStrip 184") (pin "1") (pinfunction "Pin_1") (pintype "passive"))
    )
    (net (code "549") (name "unconnected-(BergStrip 185-Pin-Pad1)") (class "Default")
      (node (ref "BergStrip 185") (pin "1") (pinfunction "Pin_1") (pintype "passive"))
    )
    (net (code "550") (name "unconnected-(BergStrip 186-Pin-Pad1)") (class "Default")
      (node (ref "BergStrip 186") (pin "1") (pinfunction "Pin_1") (pintype "passive"))
    )
    (net (code "551") (name "unconnected-(BergStrip 187-Pin-Pad1)") (class "Default")
      (node (ref "BergStrip 187") (pin "1") (pinfunction "Pin_1") (pintype "passive"))
    )
    (net (code "552") (name "unconnected-(BergStrip 188-Pin-Pad1)") (class "Default")
      (node (ref "BergStrip 188") (pin "1") (pinfunction "Pin_1") (pintype "passive"))
    )
    (net (code "553") (name "unconnected-(BergStrip 189-Pin-Pad1)") (class "Default")
      (node (ref "BergStrip 189") (pin "1") (pinfunction "Pin_1") (pintype "passive"))
    )
    (net (code "554") (name "unconnected-(BergStrip 190-Pin-Pad1)") (class "Default")
      (node (ref "BergStrip 190") (pin "1") (pinfunction "Pin_1") (pintype "passive"))
    )
    (net (code "555") (name "unconnected-(BergStrip 191-Pin-Pad1)") (class "Default")
      (node (ref "BergStrip 191") (pin "1") (pinfunction "Pin_1") (pintype "passive"))
    )
    (net (code "556") (name "unconnected-(BergStrip 192-Pin-Pad1)") (class "Default")
      (node (ref "BergStrip 192") (pin "1") (pinfunction "Pin_1") (pintype "passive"))
    )
    (net (code "557") (name "unconnected-(BergStrip 193-Pin-Pad1)") (class "Default")
      (node (ref "BergStrip 193") (pin "1") (pinfunction "Pin_1") (pintype "passive"))
    )
    (net (code "558") (name "unconnected-(BergStrip 194-Pin-Pad1)") (class "Default")
      (node (ref "BergStrip 194") (pin "1") (pinfunction "Pin_1") (pintype "passive"))
    )
    (net (code "559") (name "unconnected-(BergStrip 195-Pin-Pad1)") (class "Default")
      (node (ref "BergStrip 195") (pin "1") (pinfunction "Pin_1") (pintype "passive"))
    )
    (net (code "560") (name "unconnected-(BergStrip 196-Pin-Pad1)") (class "Default")
      (node (ref "BergStrip 196") (pin "1") (pinfunction "Pin_1") (pintype "passive"))
    )
    (net (code "561") (name "unconnected-(BergStrip 197-Pin-Pad1)") (class "Default")
      (node (ref "BergStrip 197") (pin "1") (pinfunction "Pin_1") (pintype "passive"))
    )
    (net (code "562") (name "unconnected-(BergStrip 198-Pin-Pad1)") (class "Default")
      (node (ref "BergStrip 198") (pin "1") (pinfunction "Pin_1") (pintype "passive"))
    )
    (net (code "563") (name "unconnected-(BergStrip 199-Pin-Pad1)") (class "Default")
      (node (ref "BergStrip 199") (pin "1") (pinfunction "Pin_1") (pintype "passive"))
    )
    (net (code "564") (name "unconnected-(BergStrip 200-Pin-Pad1)") (class "Default")
      (node (ref "BergStrip 200") (pin "1") (pinfunction "Pin_1") (pintype "passive"))
    )
    (net (code "565") (name "unconnected-(BuckMain-PG-Pad6)") (class "Default")
      (node (ref "BuckMain") (pin "6") (pinfunction "PG_6") (pintype "passive+no_connect"))
    )
    (net (code "566") (name "unconnected-(CONSD-DETECT-PadCD)") (class "Default")
      (node (ref "CONSD") (pin "CD") (pinfunction "DETECT_CD") (pintype "passive"))
    )
    (net (code "567") (name "unconnected-(DP83867IRRGZR-CLK_OUT-Pad18)") (class "Default")
      (node (ref "DP83867IRRGZR") (pin "18") (pinfunction "CLK_OUT_18") (pintype "passive"))
    )
    (net (code "568") (name "unconnected-(DP83867IRRGZR-GPIO_0-Pad39)") (class "Default")
      (node (ref "DP83867IRRGZR") (pin "39") (pinfunction "GPIO_0_39") (pintype "passive"))
    )
    (net (code "569") (name "unconnected-(DP83867IRRGZR-GPIO_1-Pad40)") (class "Default")
      (node (ref "DP83867IRRGZR") (pin "40") (pinfunction "GPIO_1_40") (pintype "passive"))
    )
    (net (code "570") (name "unconnected-(DP83867IRRGZR-INT_PWDN-Pad44)") (class "Default")
      (node (ref "DP83867IRRGZR") (pin "44") (pinfunction "INT_PWDN_44") (pintype "passive"))
    )
    (net (code "571") (name "unconnected-(DP83867IRRGZR-JTAG_CLK-Pad20)") (class "Default")
      (node (ref "DP83867IRRGZR") (pin "20") (pinfunction "JTAG_CLK_20") (pintype "passive"))
    )
    (net (code "572") (name "unconnected-(DP83867IRRGZR-JTAG_TDI-Pad23)") (class "Default")
      (node (ref "DP83867IRRGZR") (pin "23") (pinfunction "JTAG_TDI_23") (pintype "passive"))
    )
    (net (code "573") (name "unconnected-(DP83867IRRGZR-JTAG_TDO-Pad21)") (class "Default")
      (node (ref "DP83867IRRGZR") (pin "21") (pinfunction "JTAG_TDO_21") (pintype "passive"))
    )
    (net (code "574") (name "unconnected-(DP83867IRRGZR-JTAG_TMS-Pad22)") (class "Default")
      (node (ref "DP83867IRRGZR") (pin "22") (pinfunction "JTAG_TMS_22") (pintype "passive"))
    )
    (net (code "575") (name "unconnected-(DP83867IRRGZR-LED_0-Pad47)") (class "Default")
      (node (ref "DP83867IRRGZR") (pin "47") (pinfunction "LED_0_47") (pintype "passive"))
    )
    (net (code "576") (name "unconnected-(DP83867IRRGZR-LED_1-Pad46)") (class "Default")
      (node (ref "DP83867IRRGZR") (pin "46") (pinfunction "LED_1_46") (pintype "passive"))
    )
    (net (code "577") (name "unconnected-(DP83867IRRGZR-LED_2-Pad45)") (class "Default")
      (node (ref "DP83867IRRGZR") (pin "45") (pinfunction "LED_2_45") (pintype "passive"))
    )
    (net (code "578") (name "unconnected-(DP83867IRRGZR-RBIAS-Pad12)") (class "Default")
      (node (ref "DP83867IRRGZR") (pin "12") (pinfunction "RBIAS_12") (pintype "passive"))
    )
    (net (code "579") (name "unconnected-(DP83867IRRGZR-RESET_N-Pad43)") (class "Default")
      (node (ref "DP83867IRRGZR") (pin "43") (pinfunction "RESET_N_43") (pintype "passive"))
    )
    (net (code "580") (name "unconnected-(DP83867IRRGZR-VDDA1P8-Pad13)") (class "Default")
      (node (ref "DP83867IRRGZR") (pin "13") (pinfunction "VDDA1P8_13") (pintype "passive+no_connect"))
    )
    (net (code "581") (name "unconnected-(DP83867IRRGZR-VDDA1P8-Pad48)") (class "Default")
      (node (ref "DP83867IRRGZR") (pin "48") (pinfunction "VDDA1P8_48") (pintype "passive+no_connect"))
    )
    (net (code "582") (name "unconnected-(DP83867IRRGZR-X_O-Pad14)") (class "Default")
      (node (ref "DP83867IRRGZR") (pin "14") (pinfunction "X_O_14") (pintype "passive"))
    )
    (net (code "583") (name "unconnected-(LPDDR4-CA0_B-PadR2)") (class "Default")
      (node (ref "LPDDR4") (pin "R2") (pinfunction "CA0_B_R2") (pintype "passive"))
    )
    (net (code "584") (name "unconnected-(LPDDR4-CA1_B-PadP2)") (class "Default")
      (node (ref "LPDDR4") (pin "P2") (pinfunction "CA1_B_P2") (pintype "passive"))
    )
    (net (code "585") (name "unconnected-(LPDDR4-CA2_B-PadR9)") (class "Default")
      (node (ref "LPDDR4") (pin "R9") (pinfunction "CA2_B_R9") (pintype "passive"))
    )
    (net (code "586") (name "unconnected-(LPDDR4-CA3_B-PadR10)") (class "Default")
      (node (ref "LPDDR4") (pin "R10") (pinfunction "CA3_B_R10") (pintype "passive"))
    )
    (net (code "587") (name "unconnected-(LPDDR4-CA4_B-PadR11)") (class "Default")
      (node (ref "LPDDR4") (pin "R11") (pinfunction "CA4_B_R11") (pintype "passive"))
    )
    (net (code "588") (name "unconnected-(LPDDR4-CA5_B-PadP11)") (class "Default")
      (node (ref "LPDDR4") (pin "P11") (pinfunction "CA5_B_P11") (pintype "passive"))
    )
    (net (code "589") (name "unconnected-(LPDDR4-CKE0_B-PadP4)") (class "Default")
      (node (ref "LPDDR4") (pin "P4") (pinfunction "CKE0_B_P4") (pintype "passive"))
    )
    (net (code "590") (name "unconnected-(LPDDR4-CKE1_A-PadJ5)") (class "Default")
      (node (ref "LPDDR4") (pin "J5") (pinfunction "CKE1_A_J5") (pintype "passive"))
    )
    (net (code "591") (name "unconnected-(LPDDR4-CKE1_B-PadP5)") (class "Default")
      (node (ref "LPDDR4") (pin "P5") (pinfunction "CKE1_B_P5") (pintype "passive"))
    )
    (net (code "592") (name "unconnected-(LPDDR4-CKE2_A-PadK8)") (class "Default")
      (node (ref "LPDDR4") (pin "K8") (pinfunction "CKE2_A_K8") (pintype "passive"))
    )
    (net (code "593") (name "unconnected-(LPDDR4-CKE2_B-PadN8)") (class "Default")
      (node (ref "LPDDR4") (pin "N8") (pinfunction "CKE2_B_N8") (pintype "passive"))
    )
    (net (code "594") (name "unconnected-(LPDDR4-CK_C_B-PadP9)") (class "Default")
      (node (ref "LPDDR4") (pin "P9") (pinfunction "CK_C_B_P9") (pintype "passive"))
    )
    (net (code "595") (name "unconnected-(LPDDR4-CK_T_B-PadP8)") (class "Default")
      (node (ref "LPDDR4") (pin "P8") (pinfunction "CK_T_B_P8") (pintype "passive"))
    )
    (net (code "596") (name "unconnected-(LPDDR4-CS0_B-PadR4)") (class "Default")
      (node (ref "LPDDR4") (pin "R4") (pinfunction "CS0_B_R4") (pintype "passive"))
    )
    (net (code "597") (name "unconnected-(LPDDR4-CS1_A-PadH3)") (class "Default")
      (node (ref "LPDDR4") (pin "H3") (pinfunction "CS1_A_H3") (pintype "passive"))
    )
    (net (code "598") (name "unconnected-(LPDDR4-CS1_B-PadR3)") (class "Default")
      (node (ref "LPDDR4") (pin "R3") (pinfunction "CS1_B_R3") (pintype "passive"))
    )
    (net (code "599") (name "unconnected-(LPDDR4-CS2_A-PadK5)") (class "Default")
      (node (ref "LPDDR4") (pin "K5") (pinfunction "CS2_A_K5") (pintype "passive"))
    )
    (net (code "600") (name "unconnected-(LPDDR4-CS2_B-PadN5)") (class "Default")
      (node (ref "LPDDR4") (pin "N5") (pinfunction "CS2_B_N5") (pintype "passive"))
    )
    (net (code "601") (name "unconnected-(LPDDR4-DMI0_B-PadY3)") (class "Default")
      (node (ref "LPDDR4") (pin "Y3") (pinfunction "DMI0_B_Y3") (pintype "passive"))
    )
    (net (code "602") (name "unconnected-(LPDDR4-DMI1_B-PadY10)") (class "Default")
      (node (ref "LPDDR4") (pin "Y10") (pinfunction "DMI1_B_Y10") (pintype "passive"))
    )
    (net (code "603") (name "unconnected-(LPDDR4-DNU_1-PadA1)") (class "Default")
      (node (ref "LPDDR4") (pin "A1") (pinfunction "DNU_1_A1") (pintype "passive"))
    )
    (net (code "604") (name "unconnected-(LPDDR4-DNU_2-PadA2)") (class "Default")
      (node (ref "LPDDR4") (pin "A2") (pinfunction "DNU_2_A2") (pintype "passive"))
    )
    (net (code "605") (name "unconnected-(LPDDR4-DNU_3-PadA11)") (class "Default")
      (node (ref "LPDDR4") (pin "A11") (pinfunction "DNU_3_A11") (pintype "passive"))
    )
    (net (code "606") (name "unconnected-(LPDDR4-DNU_4-PadA12)") (class "Default")
      (node (ref "LPDDR4") (pin "A12") (pinfunction "DNU_4_A12") (pintype "passive"))
    )
    (net (code "607") (name "unconnected-(LPDDR4-DNU_5-PadB1)") (class "Default")
      (node (ref "LPDDR4") (pin "B1") (pinfunction "DNU_5_B1") (pintype "passive"))
    )
    (net (code "608") (name "unconnected-(LPDDR4-DNU_6-PadB12)") (class "Default")
      (node (ref "LPDDR4") (pin "B12") (pinfunction "DNU_6_B12") (pintype "passive"))
    )
    (net (code "609") (name "unconnected-(LPDDR4-DNU_7-PadAA1)") (class "Default")
      (node (ref "LPDDR4") (pin "AA1") (pinfunction "DNU_7_AA1") (pintype "passive"))
    )
    (net (code "610") (name "unconnected-(LPDDR4-DNU_8-PadAA12)") (class "Default")
      (node (ref "LPDDR4") (pin "AA12") (pinfunction "DNU_8_AA12") (pintype "passive"))
    )
    (net (code "611") (name "unconnected-(LPDDR4-DNU_9-PadAB1)") (class "Default")
      (node (ref "LPDDR4") (pin "AB1") (pinfunction "DNU_9_AB1") (pintype "passive"))
    )
    (net (code "612") (name "unconnected-(LPDDR4-DNU_10-PadAB2)") (class "Default")
      (node (ref "LPDDR4") (pin "AB2") (pinfunction "DNU_10_AB2") (pintype "passive"))
    )
    (net (code "613") (name "unconnected-(LPDDR4-DNU_11-PadAB11)") (class "Default")
      (node (ref "LPDDR4") (pin "AB11") (pinfunction "DNU_11_AB11") (pintype "passive"))
    )
    (net (code "614") (name "unconnected-(LPDDR4-DNU_12-PadAB12)") (class "Default")
      (node (ref "LPDDR4") (pin "AB12") (pinfunction "DNU_12_AB12") (pintype "passive"))
    )
    (net (code "615") (name "unconnected-(LPDDR4-DQ0_B-PadAA2)") (class "Default")
      (node (ref "LPDDR4") (pin "AA2") (pinfunction "DQ0_B_AA2") (pintype "passive"))
    )
    (net (code "616") (name "unconnected-(LPDDR4-DQ1_B-PadY2)") (class "Default")
      (node (ref "LPDDR4") (pin "Y2") (pinfunction "DQ1_B_Y2") (pintype "passive"))
    )
    (net (code "617") (name "unconnected-(LPDDR4-DQ2_B-PadV2)") (class "Default")
      (node (ref "LPDDR4") (pin "V2") (pinfunction "DQ2_B_V2") (pintype "passive"))
    )
    (net (code "618") (name "unconnected-(LPDDR4-DQ3_B-PadU2)") (class "Default")
      (node (ref "LPDDR4") (pin "U2") (pinfunction "DQ3_B_U2") (pintype "passive"))
    )
    (net (code "619") (name "unconnected-(LPDDR4-DQ4_B-PadU4)") (class "Default")
      (node (ref "LPDDR4") (pin "U4") (pinfunction "DQ4_B_U4") (pintype "passive"))
    )
    (net (code "620") (name "unconnected-(LPDDR4-DQ5_B-PadV4)") (class "Default")
      (node (ref "LPDDR4") (pin "V4") (pinfunction "DQ5_B_V4") (pintype "passive"))
    )
    (net (code "621") (name "unconnected-(LPDDR4-DQ6_B-PadY4)") (class "Default")
      (node (ref "LPDDR4") (pin "Y4") (pinfunction "DQ6_B_Y4") (pintype "passive"))
    )
    (net (code "622") (name "unconnected-(LPDDR4-DQ7_B-PadAA4)") (class "Default")
      (node (ref "LPDDR4") (pin "AA4") (pinfunction "DQ7_B_AA4") (pintype "passive"))
    )
    (net (code "623") (name "unconnected-(LPDDR4-DQ8_B-PadAA11)") (class "Default")
      (node (ref "LPDDR4") (pin "AA11") (pinfunction "DQ8_B_AA11") (pintype "passive"))
    )
    (net (code "624") (name "unconnected-(LPDDR4-DQ9_B-PadY11)") (class "Default")
      (node (ref "LPDDR4") (pin "Y11") (pinfunction "DQ9_B_Y11") (pintype "passive"))
    )
    (net (code "625") (name "unconnected-(LPDDR4-DQ10_B-PadV11)") (class "Default")
      (node (ref "LPDDR4") (pin "V11") (pinfunction "DQ10_B_V11") (pintype "passive"))
    )
    (net (code "626") (name "unconnected-(LPDDR4-DQ11_B-PadU11)") (class "Default")
      (node (ref "LPDDR4") (pin "U11") (pinfunction "DQ11_B_U11") (pintype "passive"))
    )
    (net (code "627") (name "unconnected-(LPDDR4-DQ12_B-PadU9)") (class "Default")
      (node (ref "LPDDR4") (pin "U9") (pinfunction "DQ12_B_U9") (pintype "passive"))
    )
    (net (code "628") (name "unconnected-(LPDDR4-DQ13_B-PadV9)") (class "Default")
      (node (ref "LPDDR4") (pin "V9") (pinfunction "DQ13_B_V9") (pintype "passive"))
    )
    (net (code "629") (name "unconnected-(LPDDR4-DQ14_B-PadY9)") (class "Default")
      (node (ref "LPDDR4") (pin "Y9") (pinfunction "DQ14_B_Y9") (pintype "passive"))
    )
    (net (code "630") (name "unconnected-(LPDDR4-DQ15_B-PadAA9)") (class "Default")
      (node (ref "LPDDR4") (pin "AA9") (pinfunction "DQ15_B_AA9") (pintype "passive"))
    )
    (net (code "631") (name "unconnected-(LPDDR4-DQS0_C_B-PadV3)") (class "Default")
      (node (ref "LPDDR4") (pin "V3") (pinfunction "DQS0_C_B_V3") (pintype "passive"))
    )
    (net (code "632") (name "unconnected-(LPDDR4-DQS0_T_B-PadW3)") (class "Default")
      (node (ref "LPDDR4") (pin "W3") (pinfunction "DQS0_T_B_W3") (pintype "passive"))
    )
    (net (code "633") (name "unconnected-(LPDDR4-DQS1_C_B-PadV10)") (class "Default")
      (node (ref "LPDDR4") (pin "V10") (pinfunction "DQS1_C_B_V10") (pintype "passive"))
    )
    (net (code "634") (name "unconnected-(LPDDR4-DQS1_T_B-PadW10)") (class "Default")
      (node (ref "LPDDR4") (pin "W10") (pinfunction "DQS1_T_B_W10") (pintype "passive"))
    )
    (net (code "635") (name "unconnected-(LPDDR4-ODT(CA)_B-PadT2)") (class "Default")
      (node (ref "LPDDR4") (pin "T2") (pinfunction "ODT(CA)_B_T2") (pintype "passive"))
    )
    (net (code "636") (name "unconnected-(LPDDR4-ZQ1-PadA8)") (class "Default")
      (node (ref "LPDDR4") (pin "A8") (pinfunction "ZQ1_A8") (pintype "passive"))
    )
    (net (code "637") (name "unconnected-(LPDDR4-ZQ2-PadG11)") (class "Default")
      (node (ref "LPDDR4") (pin "G11") (pinfunction "ZQ2_G11") (pintype "passive"))
    )
    (net (code "638") (name "unconnected-(MagJack0-Pad11)") (class "Default")
      (node (ref "MagJack0") (pin "11") (pinfunction "11_11") (pintype "passive"))
    )
    (net (code "639") (name "unconnected-(MagJack0-Pad12)") (class "Default")
      (node (ref "MagJack0") (pin "12") (pinfunction "12_12") (pintype "passive"))
    )
    (net (code "640") (name "unconnected-(MagJack0-Pad13)") (class "Default")
      (node (ref "MagJack0") (pin "13") (pinfunction "13_13") (pintype "passive"))
    )
    (net (code "641") (name "unconnected-(MagJack0-Pad14)") (class "Default")
      (node (ref "MagJack0") (pin "14") (pinfunction "14_14") (pintype "passive"))
    )
    (net (code "642") (name "unconnected-(MagJack0-PadP5)") (class "Default")
      (node (ref "MagJack0") (pin "P5") (pinfunction "P5_P5") (pintype "passive"))
    )
    (net (code "643") (name "unconnected-(MagJack0-PadP6)") (class "Default")
      (node (ref "MagJack0") (pin "P6") (pinfunction "P6_P6") (pintype "passive"))
    )
    (net (code "644") (name "unconnected-(MagJack0-SHIELD-PadS1)") (class "Default")
      (node (ref "MagJack0") (pin "S1") (pinfunction "SHIELD_S1") (pintype "passive"))
    )
    (net (code "645") (name "unconnected-(MagJack0-SHIELD-PadS2)") (class "Default")
      (node (ref "MagJack0") (pin "S2") (pinfunction "SHIELD_S2") (pintype "passive"))
    )
    (net (code "646") (name "unconnected-(PMIC-*INT-Pad11)") (class "Default")
      (node (ref "PMIC") (pin "11") (pinfunction "*INT_11") (pintype "passive"))
    )
    (net (code "647") (name "unconnected-(PMIC-*RSTOUT-Pad18)") (class "Default")
      (node (ref "PMIC") (pin "18") (pinfunction "*RSTOUT_18") (pintype "passive"))
    )
    (net (code "648") (name "unconnected-(PMIC-GPIO-Pad16)") (class "Default")
      (node (ref "PMIC") (pin "16") (pinfunction "GPIO_16") (pintype "passive"))
    )
    (net (code "649") (name "unconnected-(PMIC-GPO1-Pad8)") (class "Default")
      (node (ref "PMIC") (pin "8") (pinfunction "GPO1_8") (pintype "passive"))
    )
    (net (code "650") (name "unconnected-(PMIC-MODE{slash}RESET-Pad28)") (class "Default")
      (node (ref "PMIC") (pin "28") (pinfunction "MODE/RESET_28") (pintype "passive"))
    )
    (net (code "651") (name "unconnected-(PMIC-MODE{slash}STBY-Pad31)") (class "Default")
      (node (ref "PMIC") (pin "31") (pinfunction "MODE/STBY_31") (pintype "passive"))
    )
    (net (code "652") (name "unconnected-(PMIC-SCL-Pad10)") (class "Default")
      (node (ref "PMIC") (pin "10") (pinfunction "SCL_10") (pintype "passive"))
    )
    (net (code "653") (name "unconnected-(PMIC-SDA-Pad9)") (class "Default")
      (node (ref "PMIC") (pin "9") (pinfunction "SDA_9") (pintype "passive"))
    )
    (net (code "654") (name "unconnected-(X-TRI-STATE-Pad1)") (class "Default")
      (node (ref "X") (pin "1") (pinfunction "TRI-STATE_1") (pintype "passive+no_connect"))
    )
  )
)
